# RAMBo.net
KiCad netlist of a schematic drawn in Altium Designer
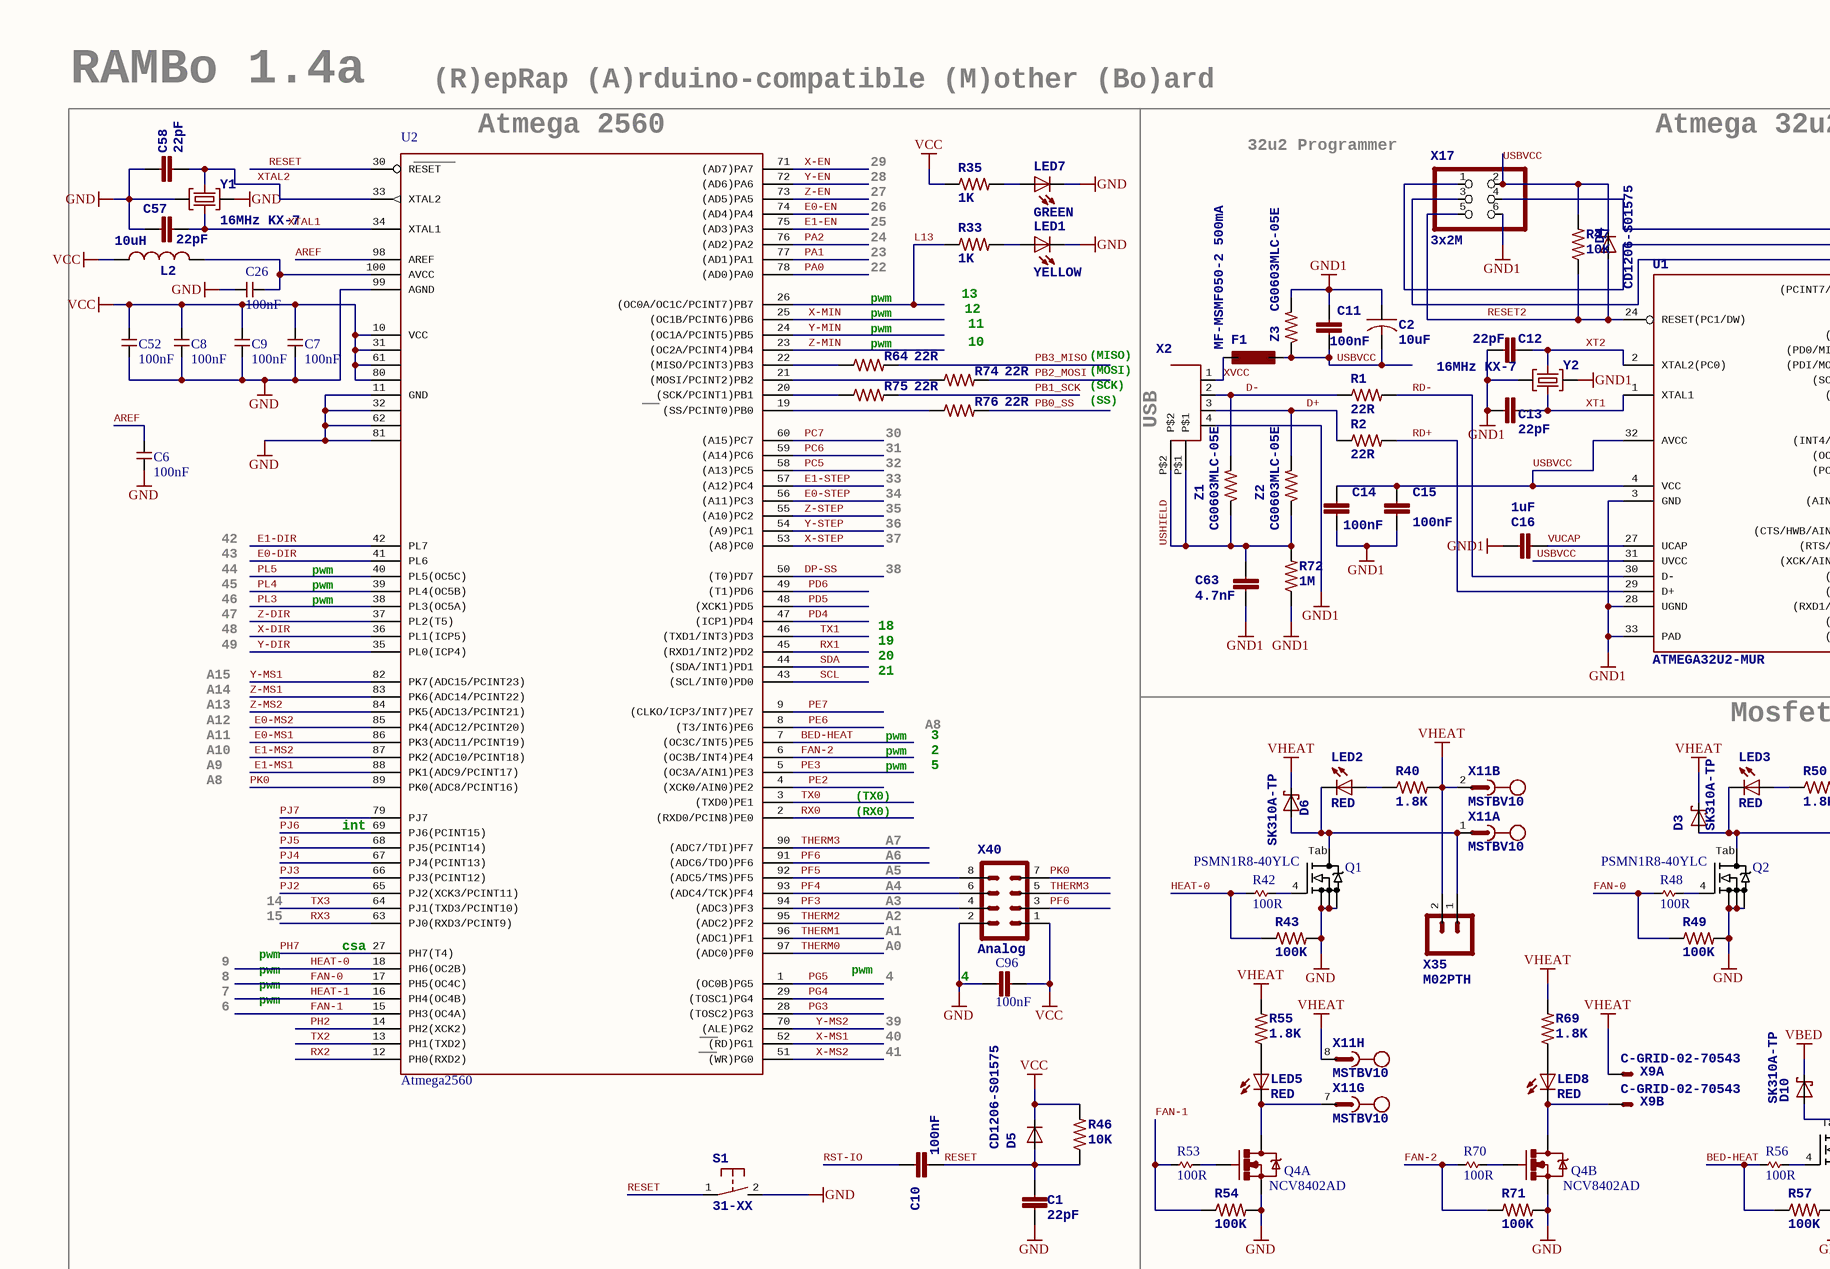
[diagram p0: RAMBo.SchDoc, top left]
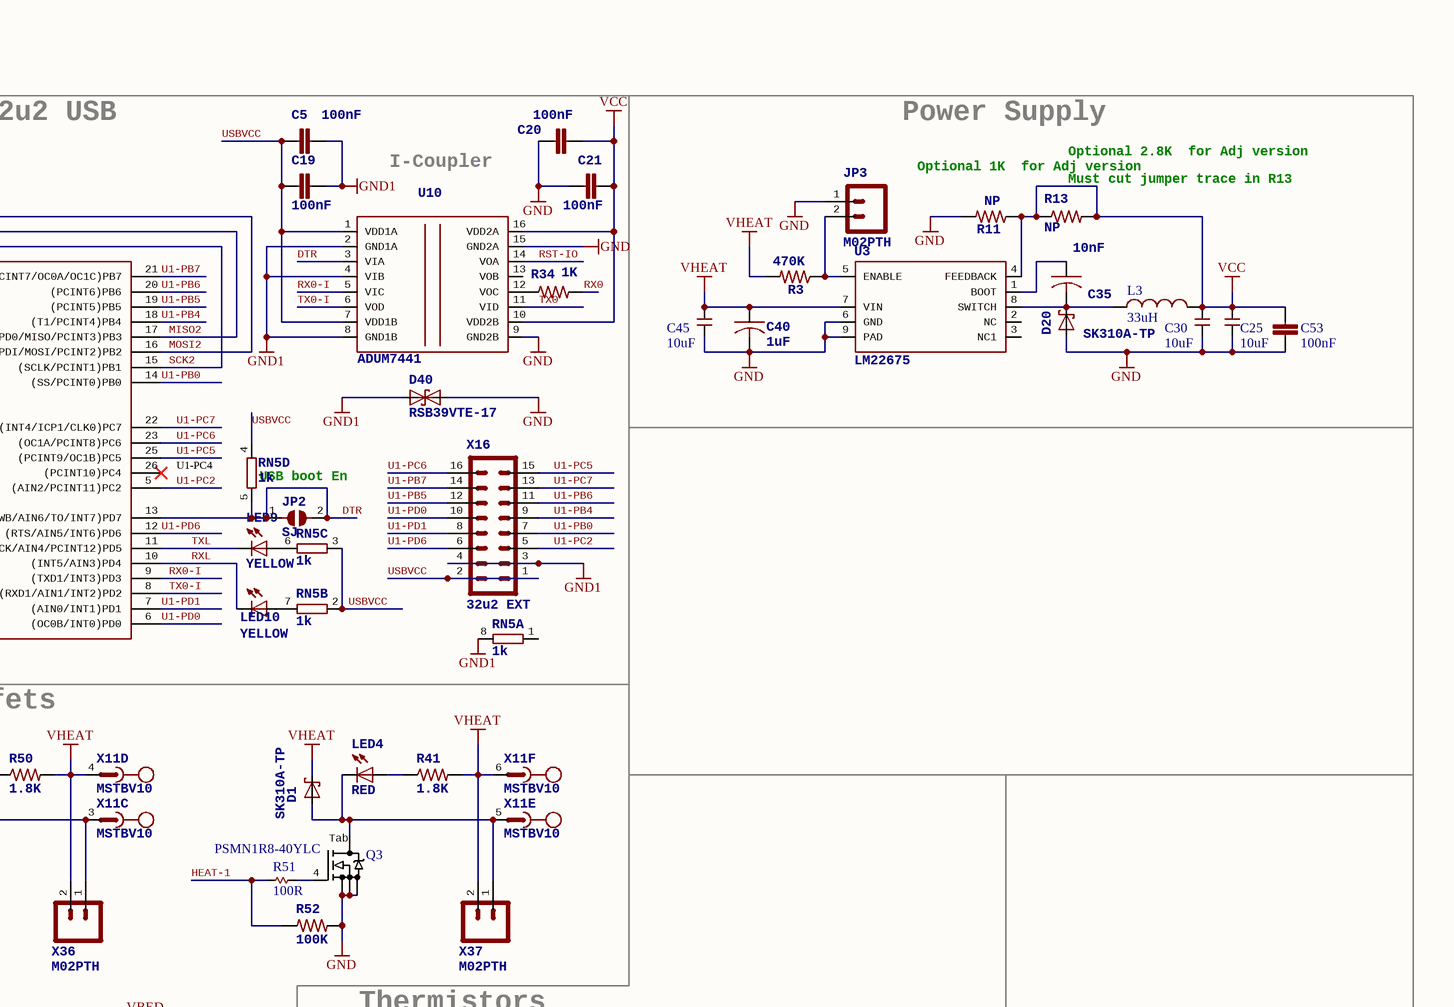
[diagram p1: RAMBo.SchDoc, top right]
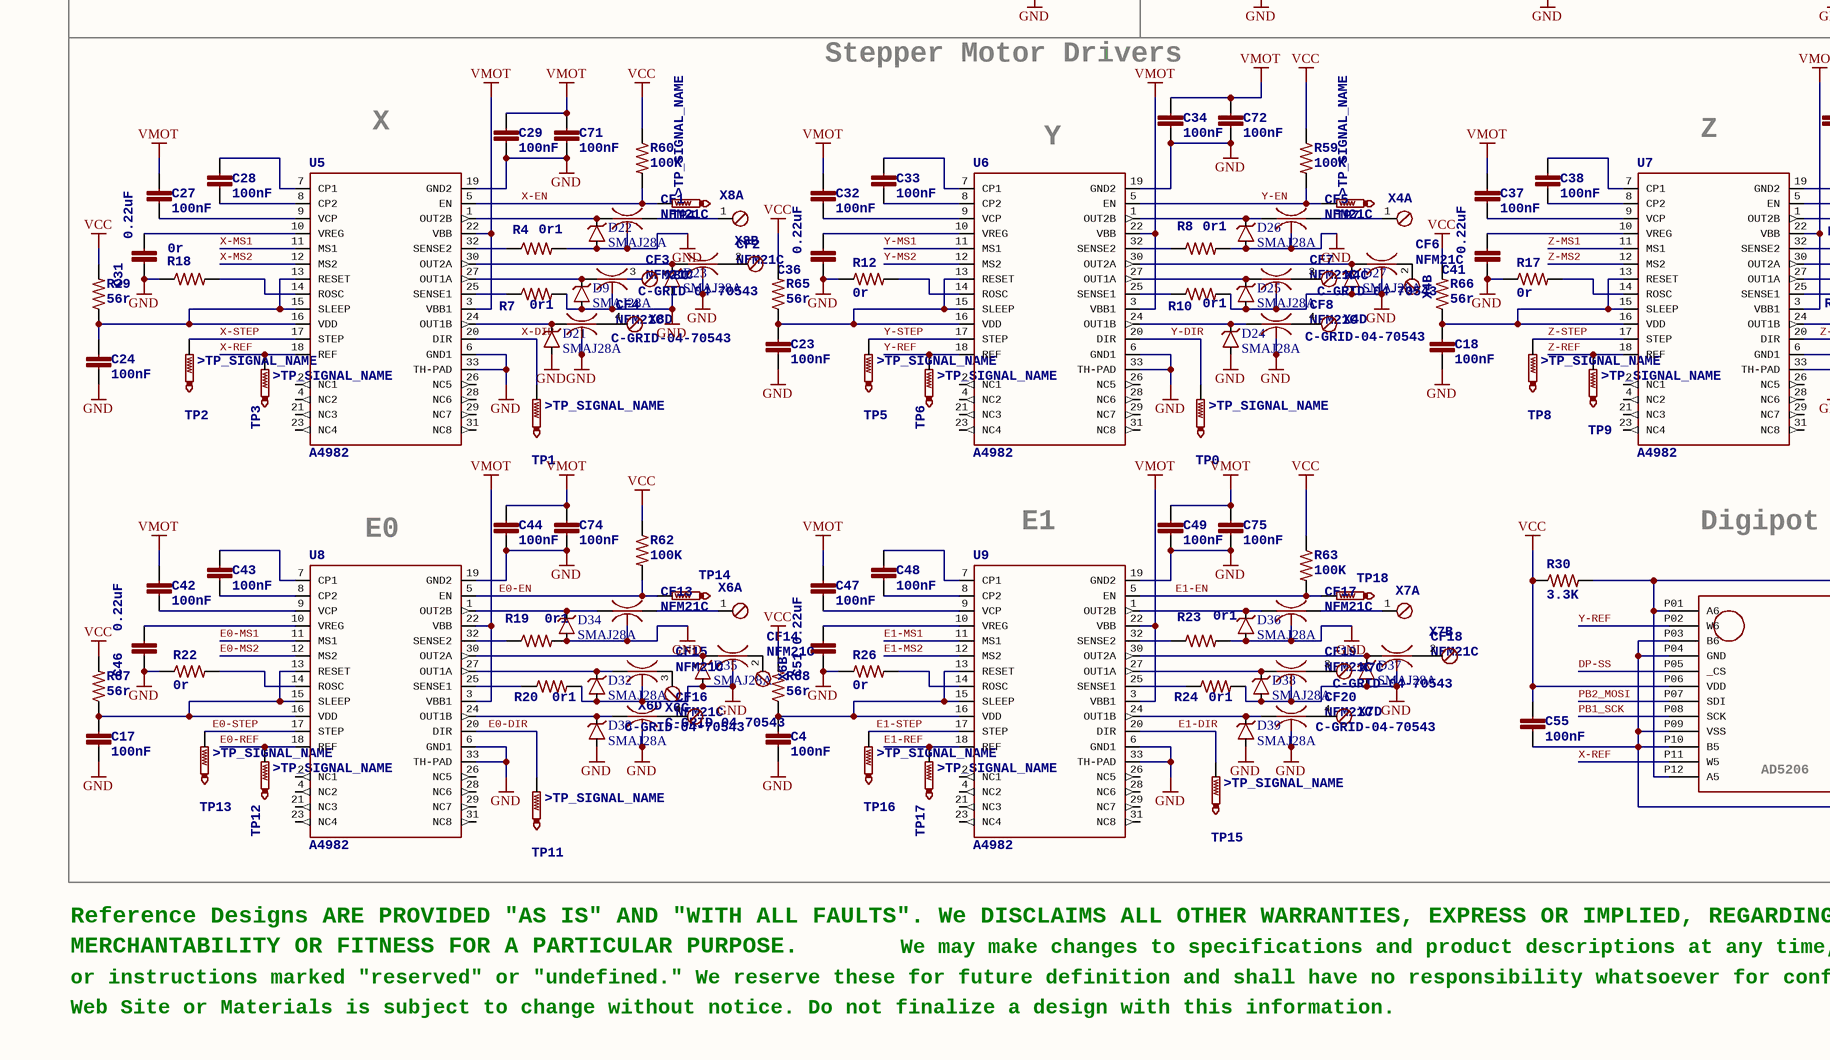
[diagram p2: RAMBo.SchDoc, bottom left]
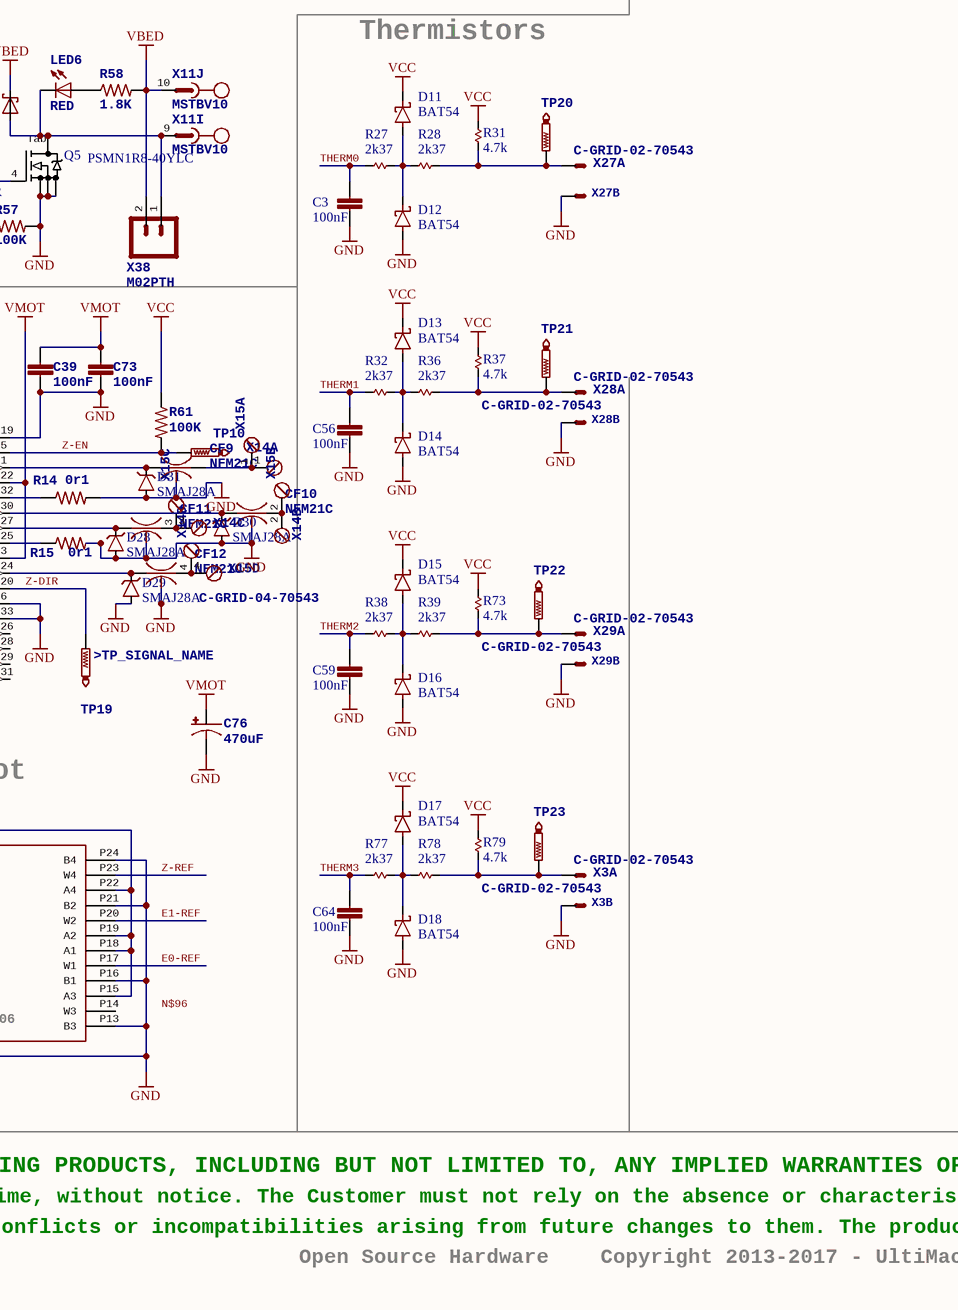
[diagram p3: RAMBo.SchDoc, bottom right]

(export (version "E")
  (design (tool "Eeschema 10.0.6"))
  (components
    (comp (ref "C1")
      (value "22pF")
      (footprint "C0603")
      (description "CAPACITOR, European symbol")
      (fields (field (name "MANUFACTURER") "TDK"))
      (libsource (lib "") (part "C-EUC0603_2"))
    )
    (comp (ref "C2")
      (value "10uF")
      (footprint "C0805")
      (description "CAPACITOR, American symbol")
      (fields (field (name "MANUFACTURER") "Kemet"))
      (libsource (lib "rcl") (part "C-USC0805"))
    )
    (comp (ref "C3")
      (value "100nF")
      (footprint "C0402")
      (description "CAP CER 0402 100nF 16V 10% X7R")
      (fields (field (name "MANUFACTURER") "Murata") (field (name "TOLERANCE") "+/- 10%"))
      (libsource (lib "") (part "GRM155R71C104KA88D_1"))
    )
    (comp (ref "C4")
      (value "100nF")
      (footprint "C0603")
      (description "CAPACITOR, European symbol")
      (fields (field (name "MANUFACTURER") "Kemet"))
      (libsource (lib "resistor") (part "C-EUC0603"))
    )
    (comp (ref "C5")
      (value "100nF")
      (footprint "C0402")
      (description "CAPACITOR, European symbol")
      (fields (field (name "MANUFACTURER") "Murata"))
      (libsource (lib "") (part "C-EUC0402_1"))
    )
    (comp (ref "C6")
      (value "100nF")
      (footprint "C0402")
      (description "CAP CER 0402 100nF 16V 10% X7R")
      (fields (field (name "MANUFACTURER") "Murata") (field (name "PART") "0.1uF 16V X7R 0402"))
      (libsource (lib "Capacitors") (part "100nF 0402 16V X7R"))
    )
    (comp (ref "C7")
      (value "100nF")
      (footprint "C0402")
      (description "CAP CER 0402 100nF 16V 10% X7R")
      (fields (field (name "MANUFACTURER") "Murata") (field (name "PART") "0.1uF 16V X7R 0402"))
      (libsource (lib "Capacitors") (part "100nF 0402 16V X7R"))
    )
    (comp (ref "C8")
      (value "100nF")
      (footprint "C0402")
      (description "CAP CER 0402 100nF 16V 10% X7R")
      (fields (field (name "MANUFACTURER") "Murata") (field (name "PART") "0.1uF 16V X7R 0402"))
      (libsource (lib "Capacitors") (part "100nF 0402 16V X7R"))
    )
    (comp (ref "C9")
      (value "100nF")
      (footprint "C0402")
      (description "CAP CER 0402 100nF 16V 10% X7R")
      (fields (field (name "MANUFACTURER") "Murata") (field (name "PART") "0.1uF 16V X7R 0402"))
      (libsource (lib "Capacitors") (part "100nF 0402 16V X7R"))
    )
    (comp (ref "C10")
      (value "100nF")
      (footprint "C0603")
      (description "CAPACITOR, European symbol")
      (fields (field (name "MANUFACTURER") "Kemet"))
      (libsource (lib "") (part "C-EUC0603_1"))
    )
    (comp (ref "C11")
      (value "100nF")
      (footprint "C0603")
      (description "CAPACITOR, European symbol")
      (fields (field (name "MANUFACTURER") "Kemet"))
      (libsource (lib "") (part "C-EUC0603_1"))
    )
    (comp (ref "C12")
      (value "22pF")
      (footprint "C0603")
      (description "CAPACITOR, European symbol")
      (fields (field (name "MANUFACTURER") "TDK"))
      (libsource (lib "resistor") (part "C-EUC0603"))
    )
    (comp (ref "C13")
      (value "22pF")
      (footprint "C0603")
      (description "CAPACITOR, European symbol")
      (fields (field (name "MANUFACTURER") "TDK"))
      (libsource (lib "resistor") (part "C-EUC0603"))
    )
    (comp (ref "C14")
      (value "100nF")
      (footprint "C0603")
      (description "CAPACITOR, European symbol")
      (fields (field (name "MANUFACTURER") "Kemet"))
      (libsource (lib "resistor") (part "C-EUC0603"))
    )
    (comp (ref "C15")
      (value "100nF")
      (footprint "C0603")
      (description "CAPACITOR, European symbol")
      (fields (field (name "MANUFACTURER") "Kemet"))
      (libsource (lib "resistor") (part "C-EUC0603"))
    )
    (comp (ref "C16")
      (value "1uF")
      (footprint "C0603")
      (description "CAPACITOR, European symbol")
      (fields (field (name "MANUFACTURER") "yageo"))
      (libsource (lib "resistor") (part "C-EUC0603"))
    )
    (comp (ref "C17")
      (value "100nF")
      (footprint "C0603")
      (description "CAPACITOR, European symbol")
      (fields (field (name "MANUFACTURER") "Kemet"))
      (libsource (lib "resistor") (part "C-EUC0603"))
    )
    (comp (ref "C18")
      (value "100nF")
      (footprint "C0603")
      (description "CAPACITOR, European symbol")
      (fields (field (name "MANUFACTURER") "Kemet"))
      (libsource (lib "resistor") (part "C-EUC0603"))
    )
    (comp (ref "C19")
      (value "100nF")
      (footprint "C0402")
      (description "CAPACITOR, European symbol")
      (fields (field (name "MANUFACTURER") "Murata"))
      (libsource (lib "") (part "C-EUC0402_1"))
    )
    (comp (ref "C20")
      (value "100nF")
      (footprint "C0402")
      (description "CAPACITOR, European symbol")
      (fields (field (name "MANUFACTURER") "Murata"))
      (libsource (lib "") (part "C-EUC0402_2"))
    )
    (comp (ref "C21")
      (value "100nF")
      (footprint "C0402")
      (description "CAPACITOR, European symbol")
      (fields (field (name "MANUFACTURER") "Murata"))
      (libsource (lib "") (part "C-EUC0402_1"))
    )
    (comp (ref "C23")
      (value "100nF")
      (footprint "C0603")
      (description "CAPACITOR, European symbol")
      (fields (field (name "MANUFACTURER") "Kemet"))
      (libsource (lib "resistor") (part "C-EUC0603"))
    )
    (comp (ref "C24")
      (value "100nF")
      (footprint "C0603")
      (description "CAPACITOR, European symbol")
      (fields (field (name "MANUFACTURER") "Kemet"))
      (libsource (lib "resistor") (part "C-EUC0603"))
    )
    (comp (ref "C25")
      (value "10uF")
      (footprint "C1206")
      (description "CAP CER 10UF 35V 10% X5R 1206")
      (fields (field (name "MANUFACTURER") "Murata") (field (name "PART") "10uF 35V X5R 1206"))
      (libsource (lib "Capacitors") (part "10uF 1206 35V X5R"))
    )
    (comp (ref "C26")
      (value "100nF")
      (footprint "C0402")
      (description "CAP CER 0402 100nF 16V 10% X7R")
      (fields (field (name "MANUFACTURER") "Murata") (field (name "PART") "0.1uF 16V X7R 0402"))
      (libsource (lib "Capacitors") (part "100nF 0402 16V X7R"))
    )
    (comp (ref "C27")
      (value "100nF")
      (footprint "C0603")
      (description "CAPACITOR, European symbol")
      (fields (field (name "MANUFACTURER") "Kemet"))
      (libsource (lib "resistor") (part "C-EUC0603"))
    )
    (comp (ref "C28")
      (value "100nF")
      (footprint "C0603")
      (description "CAPACITOR, European symbol")
      (fields (field (name "MANUFACTURER") "Kemet"))
      (libsource (lib "resistor") (part "C-EUC0603"))
    )
    (comp (ref "C29")
      (value "100nF")
      (footprint "C0603")
      (description "CAPACITOR, European symbol")
      (fields (field (name "MANUFACTURER") "Kemet"))
      (libsource (lib "resistor") (part "C-EUC0603"))
    )
    (comp (ref "C30")
      (value "10uF")
      (footprint "C1206")
      (description "CAP CER 10UF 35V 10% X5R 1206")
      (fields (field (name "MANUFACTURER") "Murata") (field (name "PART") "10uF 35V X5R 1206"))
      (libsource (lib "Capacitors") (part "10uF 1206 35V X5R"))
    )
    (comp (ref "C31")
      (value "0.22uF")
      (footprint "C0603")
      (description "CAPACITOR, European symbol")
      (fields (field (name "MANUFACTURER") "Yageo"))
      (libsource (lib "") (part "C-EUC0603_1"))
    )
    (comp (ref "C32")
      (value "100nF")
      (footprint "C0603")
      (description "CAPACITOR, European symbol")
      (fields (field (name "MANUFACTURER") "Kemet"))
      (libsource (lib "resistor") (part "C-EUC0603"))
    )
    (comp (ref "C33")
      (value "100nF")
      (footprint "C0603")
      (description "CAPACITOR, European symbol")
      (fields (field (name "MANUFACTURER") "Kemet"))
      (libsource (lib "resistor") (part "C-EUC0603"))
    )
    (comp (ref "C34")
      (value "100nF")
      (footprint "C0603")
      (description "CAPACITOR, European symbol")
      (fields (field (name "MANUFACTURER") "Kemet"))
      (libsource (lib "resistor") (part "C-EUC0603"))
    )
    (comp (ref "C35")
      (value "10nF")
      (footprint "C0603")
      (description "CAPACITOR, American symbol")
      (fields (field (name "MANUFACTURER") "TDK"))
      (libsource (lib "rcl") (part "C-USC0603"))
    )
    (comp (ref "C36")
      (value "0.22uF")
      (footprint "C0603")
      (description "CAPACITOR, European symbol")
      (fields (field (name "MANUFACTURER") "Yageo"))
      (libsource (lib "") (part "C-EUC0603_1"))
    )
    (comp (ref "C37")
      (value "100nF")
      (footprint "C0603")
      (description "CAPACITOR, European symbol")
      (fields (field (name "MANUFACTURER") "Kemet"))
      (libsource (lib "resistor") (part "C-EUC0603"))
    )
    (comp (ref "C38")
      (value "100nF")
      (footprint "C0603")
      (description "CAPACITOR, European symbol")
      (fields (field (name "MANUFACTURER") "Kemet"))
      (libsource (lib "resistor") (part "C-EUC0603"))
    )
    (comp (ref "C39")
      (value "100nF")
      (footprint "C0603")
      (description "CAPACITOR, European symbol")
      (fields (field (name "MANUFACTURER") "Kemet"))
      (libsource (lib "resistor") (part "C-EUC0603"))
    )
    (comp (ref "C40")
      (value "1uF")
      (footprint "C0805")
      (description "CAPACITOR, American symbol")
      (fields (field (name "MANUFACTURER") "Murata"))
      (libsource (lib "rcl") (part "C-USC0805"))
    )
    (comp (ref "C41")
      (value "0.22uF")
      (footprint "C0603")
      (description "CAPACITOR, European symbol")
      (fields (field (name "MANUFACTURER") "Yageo"))
      (libsource (lib "") (part "C-EUC0603_1"))
    )
    (comp (ref "C42")
      (value "100nF")
      (footprint "C0603")
      (description "CAPACITOR, European symbol")
      (fields (field (name "MANUFACTURER") "Kemet"))
      (libsource (lib "resistor") (part "C-EUC0603"))
    )
    (comp (ref "C43")
      (value "100nF")
      (footprint "C0603")
      (description "CAPACITOR, European symbol")
      (fields (field (name "MANUFACTURER") "Kemet"))
      (libsource (lib "resistor") (part "C-EUC0603"))
    )
    (comp (ref "C44")
      (value "100nF")
      (footprint "C0603")
      (description "CAPACITOR, European symbol")
      (fields (field (name "MANUFACTURER") "Kemet"))
      (libsource (lib "resistor") (part "C-EUC0603"))
    )
    (comp (ref "C45")
      (value "10uF")
      (footprint "C1206")
      (description "CAP CER 10UF 35V 10% X5R 1206")
      (fields (field (name "MANUFACTURER") "Murata") (field (name "PART") "10uF 35V X5R 1206"))
      (libsource (lib "Capacitors") (part "10uF 1206 35V X5R"))
    )
    (comp (ref "C46")
      (value "0.22uF")
      (footprint "C0603")
      (description "CAPACITOR, European symbol")
      (fields (field (name "MANUFACTURER") "Yageo"))
      (libsource (lib "") (part "C-EUC0603_1"))
    )
    (comp (ref "C47")
      (value "100nF")
      (footprint "C0603")
      (description "CAPACITOR, European symbol")
      (fields (field (name "MANUFACTURER") "Kemet"))
      (libsource (lib "resistor") (part "C-EUC0603"))
    )
    (comp (ref "C48")
      (value "100nF")
      (footprint "C0603")
      (description "CAPACITOR, European symbol")
      (fields (field (name "MANUFACTURER") "Kemet"))
      (libsource (lib "resistor") (part "C-EUC0603"))
    )
    (comp (ref "C49")
      (value "100nF")
      (footprint "C0603")
      (description "CAPACITOR, European symbol")
      (fields (field (name "MANUFACTURER") "Kemet"))
      (libsource (lib "resistor") (part "C-EUC0603"))
    )
    (comp (ref "C51")
      (value "0.22uF")
      (footprint "C0603")
      (description "CAPACITOR, European symbol")
      (fields (field (name "MANUFACTURER") "Yageo"))
      (libsource (lib "") (part "C-EUC0603_1"))
    )
    (comp (ref "C52")
      (value "100nF")
      (footprint "C0402")
      (description "CAP CER 0402 100nF 16V 10% X7R")
      (fields (field (name "MANUFACTURER") "Murata") (field (name "PART") "0.1uF 16V X7R 0402"))
      (libsource (lib "Capacitors") (part "100nF 0402 16V X7R"))
    )
    (comp (ref "C53")
      (value "100nF")
      (footprint "C0402")
      (description "CAP CER 0402 100nF 16V 10% X7R")
      (fields (field (name "MANUFACTURER") "Murata") (field (name "TOLERANCE") "+/- 10%"))
      (libsource (lib "") (part "GRM155R71C104KA88D_1"))
    )
    (comp (ref "C55")
      (value "100nF")
      (footprint "C0603")
      (description "CAPACITOR, European symbol")
      (fields (field (name "MANUFACTURER") "Kemet"))
      (libsource (lib "resistor") (part "C-EUC0603"))
    )
    (comp (ref "C56")
      (value "100nF")
      (footprint "C0402")
      (description "CAP CER 0402 100nF 16V 10% X7R")
      (fields (field (name "MANUFACTURER") "Murata") (field (name "TOLERANCE") "+/- 10%"))
      (libsource (lib "") (part "GRM155R71C104KA88D_1"))
    )
    (comp (ref "C57")
      (value "22pF")
      (footprint "C0603")
      (description "CAPACITOR, European symbol")
      (fields (field (name "MANUFACTURER") "TDK"))
      (libsource (lib "resistor") (part "C-EUC0603"))
    )
    (comp (ref "C58")
      (value "22pF")
      (footprint "C0603")
      (description "CAPACITOR, European symbol")
      (fields (field (name "MANUFACTURER") "TDK"))
      (libsource (lib "resistor") (part "C-EUC0603"))
    )
    (comp (ref "C59")
      (value "100nF")
      (footprint "C0402")
      (description "CAP CER 0402 100nF 16V 10% X7R")
      (fields (field (name "MANUFACTURER") "Murata") (field (name "TOLERANCE") "+/- 10%"))
      (libsource (lib "") (part "GRM155R71C104KA88D_1"))
    )
    (comp (ref "C63")
      (value "4.7nF")
      (footprint "C0402")
      (description "CAPACITOR, European symbol")
      (libsource (lib "rcl") (part "C-EUC0402"))
    )
    (comp (ref "C64")
      (value "100nF")
      (footprint "C0402")
      (description "CAP CER 0402 100nF 16V 10% X7R")
      (fields (field (name "MANUFACTURER") "Murata") (field (name "TOLERANCE") "+/- 10%"))
      (libsource (lib "") (part "GRM155R71C104KA88D_1"))
    )
    (comp (ref "C71")
      (value "100nF")
      (footprint "C0603")
      (description "CAPACITOR, European symbol")
      (fields (field (name "MANUFACTURER") "Kemet"))
      (libsource (lib "resistor") (part "C-EUC0603"))
    )
    (comp (ref "C72")
      (value "100nF")
      (footprint "C0603")
      (description "CAPACITOR, European symbol")
      (fields (field (name "MANUFACTURER") "Kemet"))
      (libsource (lib "resistor") (part "C-EUC0603"))
    )
    (comp (ref "C73")
      (value "100nF")
      (footprint "C0603")
      (description "CAPACITOR, European symbol")
      (fields (field (name "MANUFACTURER") "Kemet"))
      (libsource (lib "resistor") (part "C-EUC0603"))
    )
    (comp (ref "C74")
      (value "100nF")
      (footprint "C0603")
      (description "CAPACITOR, European symbol")
      (fields (field (name "MANUFACTURER") "Kemet"))
      (libsource (lib "resistor") (part "C-EUC0603"))
    )
    (comp (ref "C75")
      (value "100nF")
      (footprint "C0603")
      (description "CAPACITOR, European symbol")
      (fields (field (name "MANUFACTURER") "Kemet"))
      (libsource (lib "resistor") (part "C-EUC0603"))
    )
    (comp (ref "C76")
      (value "470uF")
      (footprint "C12,5-5")
      (description "POLARIZED CAPACITOR, American symbol")
      (fields (field (name "MANUFACTURER") "nichicon"))
      (libsource (lib "resistor") (part "CPOL-USC12,5-5"))
    )
    (comp (ref "C96")
      (value "100nF")
      (footprint "C0402")
      (description "CAP CER 0402 100nF 16V 10% X7R")
      (fields (field (name "MANUFACTURER") "Murata") (field (name "TOLERANCE") "+/- 10%"))
      (libsource (lib "3Delight") (part "GRM155R71C104KA88D"))
    )
    (comp (ref "CF1")
      (value "NFM21C")
      (footprint "NFM21C")
      (fields (field (name "MPN") "NFM21CC102R1H3D"))
      (libsource (lib "murata-filter") (part "NFM21C"))
    )
    (comp (ref "CF2")
      (value "NFM21C")
      (footprint "NFM21C")
      (fields (field (name "MPN") "NFM21CC102R1H3D"))
      (libsource (lib "murata-filter") (part "NFM21C"))
    )
    (comp (ref "CF3")
      (value "NFM21C")
      (footprint "NFM21C")
      (fields (field (name "MPN") "NFM21CC102R1H3D"))
      (libsource (lib "murata-filter") (part "NFM21C"))
    )
    (comp (ref "CF4")
      (value "NFM21C")
      (footprint "NFM21C")
      (fields (field (name "MPN") "NFM21CC102R1H3D"))
      (libsource (lib "murata-filter") (part "NFM21C"))
    )
    (comp (ref "CF5")
      (value "NFM21C")
      (footprint "NFM21C")
      (fields (field (name "MPN") "NFM21CC102R1H3D"))
      (libsource (lib "murata-filter") (part "NFM21C"))
    )
    (comp (ref "CF6")
      (value "NFM21C")
      (footprint "NFM21C")
      (fields (field (name "MPN") "NFM21CC102R1H3D"))
      (libsource (lib "murata-filter") (part "NFM21C"))
    )
    (comp (ref "CF7")
      (value "NFM21C")
      (footprint "NFM21C")
      (fields (field (name "MPN") "NFM21CC102R1H3D"))
      (libsource (lib "murata-filter") (part "NFM21C"))
    )
    (comp (ref "CF8")
      (value "NFM21C")
      (footprint "NFM21C")
      (fields (field (name "MPN") "NFM21CC102R1H3D"))
      (libsource (lib "murata-filter") (part "NFM21C"))
    )
    (comp (ref "CF9")
      (value "NFM21C")
      (footprint "NFM21C")
      (fields (field (name "MPN") "NFM21CC102R1H3D"))
      (libsource (lib "murata-filter") (part "NFM21C"))
    )
    (comp (ref "CF10")
      (value "NFM21C")
      (footprint "NFM21C")
      (fields (field (name "MPN") "NFM21CC102R1H3D"))
      (libsource (lib "murata-filter") (part "NFM21C"))
    )
    (comp (ref "CF11")
      (value "NFM21C")
      (footprint "NFM21C")
      (fields (field (name "MPN") "NFM21CC102R1H3D"))
      (libsource (lib "murata-filter") (part "NFM21C"))
    )
    (comp (ref "CF12")
      (value "NFM21C")
      (footprint "NFM21C")
      (fields (field (name "MPN") "NFM21CC102R1H3D"))
      (libsource (lib "murata-filter") (part "NFM21C"))
    )
    (comp (ref "CF13")
      (value "NFM21C")
      (footprint "NFM21C")
      (fields (field (name "MPN") "NFM21CC102R1H3D"))
      (libsource (lib "murata-filter") (part "NFM21C"))
    )
    (comp (ref "CF14")
      (value "NFM21C")
      (footprint "NFM21C")
      (fields (field (name "MPN") "NFM21CC102R1H3D"))
      (libsource (lib "murata-filter") (part "NFM21C"))
    )
    (comp (ref "CF15")
      (value "NFM21C")
      (footprint "NFM21C")
      (fields (field (name "MPN") "NFM21CC102R1H3D"))
      (libsource (lib "murata-filter") (part "NFM21C"))
    )
    (comp (ref "CF16")
      (value "NFM21C")
      (footprint "NFM21C")
      (fields (field (name "MPN") "NFM21CC102R1H3D"))
      (libsource (lib "murata-filter") (part "NFM21C"))
    )
    (comp (ref "CF17")
      (value "NFM21C")
      (footprint "NFM21C")
      (fields (field (name "MPN") "NFM21CC102R1H3D"))
      (libsource (lib "murata-filter") (part "NFM21C"))
    )
    (comp (ref "CF18")
      (value "NFM21C")
      (footprint "NFM21C")
      (fields (field (name "MPN") "NFM21CC102R1H3D"))
      (libsource (lib "murata-filter") (part "NFM21C"))
    )
    (comp (ref "CF19")
      (value "NFM21C")
      (footprint "NFM21C")
      (fields (field (name "MPN") "NFM21CC102R1H3D"))
      (libsource (lib "murata-filter") (part "NFM21C"))
    )
    (comp (ref "CF20")
      (value "NFM21C")
      (footprint "NFM21C")
      (fields (field (name "MPN") "NFM21CC102R1H3D"))
      (libsource (lib "murata-filter") (part "NFM21C"))
    )
    (comp (ref "D1")
      (value "SK310A-TP")
      (footprint "SMA-SM")
      (description "Schottky Diode")
      (fields (field (name "MANUFACTURER") "Diodes Inc."))
      (libsource (lib "ultimachine1") (part "SCHOTTKY-DIODE"))
    )
    (comp (ref "D3")
      (value "SK310A-TP")
      (footprint "SMA-SM")
      (description "Schottky Diode")
      (fields (field (name "MANUFACTURER") "Diodes Inc."))
      (libsource (lib "ultimachine1") (part "SCHOTTKY-DIODE"))
    )
    (comp (ref "D4")
      (value "CD1206-S01575")
      (footprint "MINIMELF")
      (description "DIODE")
      (fields (field (name "MANUFACTURER") "Bourns"))
      (libsource (lib "diode") (part "DIODE-MINIMELF"))
    )
    (comp (ref "D5")
      (value "CD1206-S01575")
      (footprint "MINIMELF")
      (description "DIODE")
      (fields (field (name "MANUFACTURER") "Bourns"))
      (libsource (lib "diode") (part "DIODE-MINIMELF"))
    )
    (comp (ref "D6")
      (value "SK310A-TP")
      (footprint "SMA-SM")
      (description "Schottky Diode")
      (fields (field (name "MANUFACTURER") "Diodes Inc."))
      (libsource (lib "ultimachine1") (part "SCHOTTKY-DIODE"))
    )
    (comp (ref "D9")
      (value "SMAJ28A")
      (footprint "Passives:SMA-SM")
      (description "TVS DIODE 28VWM 45.4VC SMA")
      (fields (field (name "MANUFACTURER") "Diodes Inc") (field (name "TOLERANCE") "NA"))
      (libsource (lib "Diodes") (part "SMAJ28A"))
    )
    (comp (ref "D10")
      (value "SK310A-TP")
      (footprint "SMA-SM")
      (description "Schottky Diode")
      (fields (field (name "MANUFACTURER") "Diodes Inc."))
      (libsource (lib "ultimachine1") (part "SCHOTTKY-DIODE"))
    )
    (comp (ref "D11")
      (value "BAT54")
      (footprint "SOD523_IPC")
      (description "Diode Schottky 30V 100mA Surface Mount SOD-523")
      (fields (field (name "MANUFACTURER") "Diodes Incorporated") (field (name "TOLERANCE") "NA"))
      (libsource (lib "3Delight") (part "BAT54WT-7"))
    )
    (comp (ref "D12")
      (value "BAT54")
      (footprint "SOD523_IPC")
      (description "Diode Schottky 30V 100mA Surface Mount SOD-523")
      (fields (field (name "MANUFACTURER") "Diodes Incorporated") (field (name "TOLERANCE") "NA"))
      (libsource (lib "3Delight") (part "BAT54WT-7"))
    )
    (comp (ref "D13")
      (value "BAT54")
      (footprint "SOD523_IPC")
      (description "Diode Schottky 30V 100mA Surface Mount SOD-523")
      (fields (field (name "MANUFACTURER") "Diodes Incorporated") (field (name "TOLERANCE") "NA"))
      (libsource (lib "3Delight") (part "BAT54WT-7"))
    )
    (comp (ref "D14")
      (value "BAT54")
      (footprint "SOD523_IPC")
      (description "Diode Schottky 30V 100mA Surface Mount SOD-523")
      (fields (field (name "MANUFACTURER") "Diodes Incorporated") (field (name "TOLERANCE") "NA"))
      (libsource (lib "3Delight") (part "BAT54WT-7"))
    )
    (comp (ref "D15")
      (value "BAT54")
      (footprint "SOD523_IPC")
      (description "Diode Schottky 30V 100mA Surface Mount SOD-523")
      (fields (field (name "MANUFACTURER") "Diodes Incorporated") (field (name "TOLERANCE") "NA"))
      (libsource (lib "3Delight") (part "BAT54WT-7"))
    )
    (comp (ref "D16")
      (value "BAT54")
      (footprint "SOD523_IPC")
      (description "Diode Schottky 30V 100mA Surface Mount SOD-523")
      (fields (field (name "MANUFACTURER") "Diodes Incorporated") (field (name "TOLERANCE") "NA"))
      (libsource (lib "3Delight") (part "BAT54WT-7"))
    )
    (comp (ref "D17")
      (value "BAT54")
      (footprint "SOD523_IPC")
      (description "Diode Schottky 30V 100mA Surface Mount SOD-523")
      (fields (field (name "MANUFACTURER") "Diodes Incorporated") (field (name "TOLERANCE") "NA"))
      (libsource (lib "3Delight") (part "BAT54WT-7"))
    )
    (comp (ref "D18")
      (value "BAT54")
      (footprint "SOD523_IPC")
      (description "Diode Schottky 30V 100mA Surface Mount SOD-523")
      (fields (field (name "MANUFACTURER") "Diodes Incorporated") (field (name "TOLERANCE") "NA"))
      (libsource (lib "3Delight") (part "BAT54WT-7"))
    )
    (comp (ref "D20")
      (value "SK310A-TP")
      (footprint "SMA-SM")
      (description "Schottky Diode")
      (fields (field (name "MANUFACTURER") "Diodes Inc."))
      (libsource (lib "ultimachine1") (part "SCHOTTKY-DIODE"))
    )
    (comp (ref "D21")
      (value "SMAJ28A")
      (footprint "Passives:SMA-SM")
      (description "TVS DIODE 28VWM 45.4VC SMA")
      (fields (field (name "MANUFACTURER") "Diodes Inc") (field (name "TOLERANCE") "NA"))
      (libsource (lib "Diodes") (part "SMAJ28A"))
    )
    (comp (ref "D22")
      (value "SMAJ28A")
      (footprint "Passives:SMA-SM")
      (description "TVS DIODE 28VWM 45.4VC SMA")
      (fields (field (name "MANUFACTURER") "Diodes Inc") (field (name "TOLERANCE") "NA"))
      (libsource (lib "Diodes") (part "SMAJ28A"))
    )
    (comp (ref "D23")
      (value "SMAJ28A")
      (footprint "Passives:SMA-SM")
      (description "TVS DIODE 28VWM 45.4VC SMA")
      (fields (field (name "MANUFACTURER") "Diodes Inc") (field (name "TOLERANCE") "NA"))
      (libsource (lib "Diodes") (part "SMAJ28A"))
    )
    (comp (ref "D24")
      (value "SMAJ28A")
      (footprint "Passives:SMA-SM")
      (description "TVS DIODE 28VWM 45.4VC SMA")
      (fields (field (name "MANUFACTURER") "Diodes Inc") (field (name "TOLERANCE") "NA"))
      (libsource (lib "Diodes") (part "SMAJ28A"))
    )
    (comp (ref "D25")
      (value "SMAJ28A")
      (footprint "Passives:SMA-SM")
      (description "TVS DIODE 28VWM 45.4VC SMA")
      (fields (field (name "MANUFACTURER") "Diodes Inc") (field (name "TOLERANCE") "NA"))
      (libsource (lib "Diodes") (part "SMAJ28A"))
    )
    (comp (ref "D26")
      (value "SMAJ28A")
      (footprint "Passives:SMA-SM")
      (description "TVS DIODE 28VWM 45.4VC SMA")
      (fields (field (name "MANUFACTURER") "Diodes Inc") (field (name "TOLERANCE") "NA"))
      (libsource (lib "Diodes") (part "SMAJ28A"))
    )
    (comp (ref "D27")
      (value "SMAJ28A")
      (footprint "Passives:SMA-SM")
      (description "TVS DIODE 28VWM 45.4VC SMA")
      (fields (field (name "MANUFACTURER") "Diodes Inc") (field (name "TOLERANCE") "NA"))
      (libsource (lib "Diodes") (part "SMAJ28A"))
    )
    (comp (ref "D28")
      (value "SMAJ28A")
      (footprint "Passives:SMA-SM")
      (description "TVS DIODE 28VWM 45.4VC SMA")
      (fields (field (name "MANUFACTURER") "Diodes Inc") (field (name "TOLERANCE") "NA"))
      (libsource (lib "Diodes") (part "SMAJ28A"))
    )
    (comp (ref "D29")
      (value "SMAJ28A")
      (footprint "Passives:SMA-SM")
      (description "TVS DIODE 28VWM 45.4VC SMA")
      (fields (field (name "MANUFACTURER") "Diodes Inc") (field (name "TOLERANCE") "NA"))
      (libsource (lib "Diodes") (part "SMAJ28A"))
    )
    (comp (ref "D30")
      (value "SMAJ28A")
      (footprint "Passives:SMA-SM")
      (description "TVS DIODE 28VWM 45.4VC SMA")
      (fields (field (name "MANUFACTURER") "Diodes Inc") (field (name "TOLERANCE") "NA"))
      (libsource (lib "Diodes") (part "SMAJ28A"))
    )
    (comp (ref "D31")
      (value "SMAJ28A")
      (footprint "Passives:SMA-SM")
      (description "TVS DIODE 28VWM 45.4VC SMA")
      (fields (field (name "MANUFACTURER") "Diodes Inc") (field (name "TOLERANCE") "NA"))
      (libsource (lib "Diodes") (part "SMAJ28A"))
    )
    (comp (ref "D32")
      (value "SMAJ28A")
      (footprint "Passives:SMA-SM")
      (description "TVS DIODE 28VWM 45.4VC SMA")
      (fields (field (name "MANUFACTURER") "Diodes Inc") (field (name "TOLERANCE") "NA"))
      (libsource (lib "Diodes") (part "SMAJ28A"))
    )
    (comp (ref "D33")
      (value "SMAJ28A")
      (footprint "Passives:SMA-SM")
      (description "TVS DIODE 28VWM 45.4VC SMA")
      (fields (field (name "MANUFACTURER") "Diodes Inc") (field (name "TOLERANCE") "NA"))
      (libsource (lib "Diodes") (part "SMAJ28A"))
    )
    (comp (ref "D34")
      (value "SMAJ28A")
      (footprint "Passives:SMA-SM")
      (description "TVS DIODE 28VWM 45.4VC SMA")
      (fields (field (name "MANUFACTURER") "Diodes Inc") (field (name "TOLERANCE") "NA"))
      (libsource (lib "Diodes") (part "SMAJ28A"))
    )
    (comp (ref "D35")
      (value "SMAJ28A")
      (footprint "Passives:SMA-SM")
      (description "TVS DIODE 28VWM 45.4VC SMA")
      (fields (field (name "MANUFACTURER") "Diodes Inc") (field (name "TOLERANCE") "NA"))
      (libsource (lib "Diodes") (part "SMAJ28A"))
    )
    (comp (ref "D36")
      (value "SMAJ28A")
      (footprint "Passives:SMA-SM")
      (description "TVS DIODE 28VWM 45.4VC SMA")
      (fields (field (name "MANUFACTURER") "Diodes Inc") (field (name "TOLERANCE") "NA"))
      (libsource (lib "Diodes") (part "SMAJ28A"))
    )
    (comp (ref "D37")
      (value "SMAJ28A")
      (footprint "Passives:SMA-SM")
      (description "TVS DIODE 28VWM 45.4VC SMA")
      (fields (field (name "MANUFACTURER") "Diodes Inc") (field (name "TOLERANCE") "NA"))
      (libsource (lib "Diodes") (part "SMAJ28A"))
    )
    (comp (ref "D38")
      (value "SMAJ28A")
      (footprint "Passives:SMA-SM")
      (description "TVS DIODE 28VWM 45.4VC SMA")
      (fields (field (name "MANUFACTURER") "Diodes Inc") (field (name "TOLERANCE") "NA"))
      (libsource (lib "Diodes") (part "SMAJ28A"))
    )
    (comp (ref "D39")
      (value "SMAJ28A")
      (footprint "Passives:SMA-SM")
      (description "TVS DIODE 28VWM 45.4VC SMA")
      (fields (field (name "MANUFACTURER") "Diodes Inc") (field (name "TOLERANCE") "NA"))
      (libsource (lib "Diodes") (part "SMAJ28A"))
    )
    (comp (ref "D40")
      (value "RSB39VTE-17")
      (footprint "SOD323-R")
      (description "DIODE   uni and bidirectional supressor diode")
      (libsource (lib "diode") (part "TVS-BISOD323"))
    )
    (comp (ref "F1")
      (value "MF-MSMF050-2 500mA")
      (footprint "L1812")
      (description "INDUCTOR, European symbol")
      (fields (field (name "MANUFACTURER") "Bourns"))
      (libsource (lib "rcl") (part "L-EUL1812"))
    )
    (comp (ref "JP2")
      (value "SJ")
      (footprint "SJ")
      (description "SMD solder JUMPER")
      (libsource (lib "jumper") (part "SJ"))
    )
    (comp (ref "JP3") (value "M02PTH") (footprint "1X02") (libsource (lib "SparkFun") (part "M02PTH")))
    (comp (ref "L2")
      (value "10uH")
      (footprint "C0805")
      (description "INDUCTOR, American symbol")
      (fields (field (name "MANUFACTURER") "Taiyo Yuden"))
      (libsource (lib "resistor") (part "L-US"))
    )
    (comp (ref "L3")
      (value "33uH")
      (footprint "INDP8080X40L")
      (description "FIXED IND 33UH 1.7A 145 MOHM SMD")
      (fields (field (name "MANUFACTURER") "Bourns") (field (name "TOLERANCE") "+/- 20%"))
      (libsource (lib "Inductors") (part "10uH 1.7A"))
    )
    (comp (ref "LED1")
      (value "YELLOW")
      (footprint "CHIP-LED0805")
      (fields (field (name "MANUFACTURER") "Dialight"))
      (libsource (lib "led") (part "LEDCHIP-LED0805"))
    )
    (comp (ref "LED2")
      (value "RED")
      (footprint "CHIP-LED0805")
      (fields (field (name "MANUFACTURER") "Dialight"))
      (libsource (lib "led") (part "LEDCHIP-LED0805"))
    )
    (comp (ref "LED3")
      (value "RED")
      (footprint "CHIP-LED0805")
      (fields (field (name "MANUFACTURER") "Dialight"))
      (libsource (lib "led") (part "LEDCHIP-LED0805"))
    )
    (comp (ref "LED4")
      (value "RED")
      (footprint "CHIP-LED0805")
      (fields (field (name "MANUFACTURER") "Dialight"))
      (libsource (lib "led") (part "LEDCHIP-LED0805"))
    )
    (comp (ref "LED5")
      (value "RED")
      (footprint "CHIP-LED0805")
      (fields (field (name "MANUFACTURER") "Dialight"))
      (libsource (lib "led") (part "LEDCHIP-LED0805"))
    )
    (comp (ref "LED6")
      (value "RED")
      (footprint "CHIP-LED0805")
      (fields (field (name "MANUFACTURER") "Dialight"))
      (libsource (lib "led") (part "LEDCHIP-LED0805"))
    )
    (comp (ref "LED7")
      (value "GREEN")
      (footprint "CHIP-LED0805")
      (libsource (lib "led") (part "LEDCHIP-LED0805"))
    )
    (comp (ref "LED8")
      (value "RED")
      (footprint "CHIP-LED0805")
      (fields (field (name "MANUFACTURER") "Dialight"))
      (libsource (lib "led") (part "LEDCHIP-LED0805"))
    )
    (comp (ref "LED9")
      (value "YELLOW")
      (footprint "CHIP-LED0805")
      (fields (field (name "MANUFACTURER") "Dialight"))
      (libsource (lib "led") (part "LEDCHIP-LED0805"))
    )
    (comp (ref "LED10")
      (value "YELLOW")
      (footprint "CHIP-LED0805")
      (fields (field (name "MANUFACTURER") "Dialight"))
      (libsource (lib "led") (part "LEDCHIP-LED0805"))
    )
    (comp (ref "Q1")
      (value "PSMN1R8-40YLC")
      (footprint "Passives:SOT669")
      (description "MOSFET N-CH 40V 100A LFPAK")
      (fields (field (name "MANUFACTURER") "Nexperia") (field (name "TOLERANCE") "-NA-"))
      (libsource (lib "Transistors") (part "PSMN1R8-40YLC"))
    )
    (comp (ref "Q2")
      (value "PSMN1R8-40YLC")
      (footprint "SOT669")
      (description "MOSFET N-CH 40V 100A LFPAK")
      (fields (field (name "MANUFACTURER") "Nexperia") (field (name "TOLERANCE") "-NA-"))
      (libsource (lib "Transistors") (part "PSMN1R8-40YLC"))
    )
    (comp (ref "Q3")
      (value "PSMN1R8-40YLC")
      (footprint "SOT669")
      (description "MOSFET N-CH 40V 100A LFPAK")
      (fields (field (name "MANUFACTURER") "Nexperia") (field (name "TOLERANCE") "-NA-"))
      (libsource (lib "Transistors") (part "PSMN1R8-40YLC"))
    )
    (comp (ref "Q4")
      (value "NCV8402AD")
      (footprint "NCV8402AD-SOIC8")
      (description "IC DVR LOW SIDE 8-SOIC")
      (fields (field (name "MANUFACTURER") "On Semi") (field (name "PART") "NCV8402"))
      (libsource (lib "3Delight") (part "NCV8402AD"))
    )
    (comp (ref "Q5")
      (value "PSMN1R8-40YLC")
      (footprint "SOT669")
      (description "MOSFET N-CH 40V 100A LFPAK")
      (fields (field (name "MANUFACTURER") "Nexperia") (field (name "TOLERANCE") "-NA-"))
      (libsource (lib "Transistors") (part "PSMN1R8-40YLC"))
    )
    (comp (ref "R1")
      (value "22R")
      (footprint "R0402")
      (description "RESISTOR, American symbol")
      (fields (field (name "MANUFACTURER") "Yageo"))
      (libsource (lib "rcl") (part "R-US_R0402"))
    )
    (comp (ref "R2")
      (value "22R")
      (footprint "R0402")
      (description "RESISTOR, American symbol")
      (fields (field (name "MANUFACTURER") "Yageo"))
      (libsource (lib "rcl") (part "R-US_R0402"))
    )
    (comp (ref "R3")
      (value "470K")
      (footprint "R0603")
      (description "RESISTOR, American symbol")
      (fields (field (name "MANUFACTURER") "Vishay"))
      (libsource (lib "resistor") (part "R-US_R0603"))
    )
    (comp (ref "R4")
      (value "0r1")
      (footprint "R1206")
      (description "RESISTOR, American symbol")
      (fields (field (name "MANUFACTURER") "Bourns"))
      (libsource (lib "resistor") (part "R-US_R1206"))
    )
    (comp (ref "R7")
      (value "0r1")
      (footprint "R1206")
      (description "RESISTOR, American symbol")
      (fields (field (name "MANUFACTURER") "Bourns"))
      (libsource (lib "resistor") (part "R-US_R1206"))
    )
    (comp (ref "R8")
      (value "0r1")
      (footprint "R1206")
      (description "RESISTOR, American symbol")
      (fields (field (name "MANUFACTURER") "Bourns"))
      (libsource (lib "resistor") (part "R-US_R1206"))
    )
    (comp (ref "R10")
      (value "0r1")
      (footprint "R1206")
      (description "RESISTOR, American symbol")
      (fields (field (name "MANUFACTURER") "Bourns"))
      (libsource (lib "resistor") (part "R-US_R1206"))
    )
    (comp (ref "R11")
      (value "NP")
      (footprint "R0603")
      (description "RESISTOR, American symbol")
      (libsource (lib "resistor") (part "R-US_R0603"))
    )
    (comp (ref "R12")
      (value "0r")
      (footprint "R0603")
      (description "RESISTOR, American symbol")
      (fields (field (name "MANUFACTURER") "Bourns"))
      (libsource (lib "resistor") (part "R-US_R0603"))
    )
    (comp (ref "R13")
      (value "NP")
      (footprint "R0603")
      (description "RESISTOR, American symbol")
      (libsource (lib "resistor") (part "R-US_R0603"))
    )
    (comp (ref "R14")
      (value "0r1")
      (footprint "R1206")
      (description "RESISTOR, American symbol")
      (fields (field (name "MANUFACTURER") "Bourns"))
      (libsource (lib "resistor") (part "R-US_R1206"))
    )
    (comp (ref "R15")
      (value "0r1")
      (footprint "R1206")
      (description "RESISTOR, American symbol")
      (fields (field (name "MANUFACTURER") "Bourns"))
      (libsource (lib "resistor") (part "R-US_R1206"))
    )
    (comp (ref "R17")
      (value "0r")
      (footprint "R0603")
      (description "RESISTOR, American symbol")
      (fields (field (name "MANUFACTURER") "Bourns"))
      (libsource (lib "resistor") (part "R-US_R0603"))
    )
    (comp (ref "R18")
      (value "0r")
      (footprint "R0603")
      (description "RESISTOR, American symbol")
      (fields (field (name "MANUFACTURER") "Bourns"))
      (libsource (lib "resistor") (part "R-US_R0603"))
    )
    (comp (ref "R19")
      (value "0r1")
      (footprint "R1206")
      (description "RESISTOR, American symbol")
      (fields (field (name "MANUFACTURER") "Bourns"))
      (libsource (lib "resistor") (part "R-US_R1206"))
    )
    (comp (ref "R20")
      (value "0r1")
      (footprint "R1206")
      (description "RESISTOR, American symbol")
      (fields (field (name "MANUFACTURER") "Bourns"))
      (libsource (lib "resistor") (part "R-US_R1206"))
    )
    (comp (ref "R22")
      (value "0r")
      (footprint "R0603")
      (description "RESISTOR, American symbol")
      (fields (field (name "MANUFACTURER") "Bourns"))
      (libsource (lib "resistor") (part "R-US_R0603"))
    )
    (comp (ref "R23")
      (value "0r1")
      (footprint "R1206")
      (description "RESISTOR, American symbol")
      (fields (field (name "MANUFACTURER") "Bourns"))
      (libsource (lib "resistor") (part "R-US_R1206"))
    )
    (comp (ref "R24")
      (value "0r1")
      (footprint "R1206")
      (description "RESISTOR, American symbol")
      (fields (field (name "MANUFACTURER") "Bourns"))
      (libsource (lib "resistor") (part "R-US_R1206"))
    )
    (comp (ref "R26")
      (value "0r")
      (footprint "R0603")
      (description "RESISTOR, American symbol")
      (fields (field (name "MANUFACTURER") "Bourns"))
      (libsource (lib "resistor") (part "R-US_R0603"))
    )
    (comp (ref "R27")
      (value "2k37")
      (footprint "R0402")
      (description "RES SMD 2.37K OHM 1% 1/16W 0402")
      (fields (field (name "MANUFACTURER") "Yageo") (field (name "PART") "2.37k"))
      (libsource (lib "3Delight") (part "RC0402FR-072K37L"))
    )
    (comp (ref "R28")
      (value "2k37")
      (footprint "R0402")
      (description "RES SMD 2.37K OHM 1% 1/16W 0402")
      (fields (field (name "MANUFACTURER") "Yageo") (field (name "PART") "2.37k"))
      (libsource (lib "3Delight") (part "RC0402FR-072K37L"))
    )
    (comp (ref "R29")
      (value "56r")
      (footprint "R0603")
      (description "RESISTOR, American symbol")
      (fields (field (name "MANUFACTURER") "Vishay"))
      (libsource (lib "resistor") (part "R-US_R0603"))
    )
    (comp (ref "R30")
      (value "3.3K")
      (footprint "R0603")
      (description "RESISTOR, American symbol")
      (fields (field (name "MANUFACTURER") "panasonic"))
      (libsource (lib "resistor") (part "R-US_R0603"))
    )
    (comp (ref "R31")
      (value "4.7k")
      (footprint "R0402")
      (description "RES SMD 4.7K OHM 1% 1/16W 0402")
      (fields (field (name "MANUFACTURER") "Yageo") (field (name "TOLERANCE") "+/- 1%"))
      (libsource (lib "3Delight") (part "RC0402FR-074K7L"))
    )
    (comp (ref "R32")
      (value "2k37")
      (footprint "R0402")
      (description "RES SMD 2.37K OHM 1% 1/16W 0402")
      (fields (field (name "MANUFACTURER") "Yageo") (field (name "PART") "2.37k"))
      (libsource (lib "3Delight") (part "RC0402FR-072K37L"))
    )
    (comp (ref "R33")
      (value "1K")
      (footprint "R0603")
      (description "RESISTOR, American symbol")
      (fields (field (name "MANUFACTURER") "Panasonic"))
      (libsource (lib "resistor") (part "R-US_R0603"))
    )
    (comp (ref "R34")
      (value "1K")
      (footprint "R0603")
      (description "RESISTOR, American symbol")
      (fields (field (name "MANUFACTURER") "Panasonic"))
      (libsource (lib "resistor") (part "R-US_R0603"))
    )
    (comp (ref "R35")
      (value "1K")
      (footprint "R0603")
      (description "RESISTOR, American symbol")
      (fields (field (name "MANUFACTURER") "Panasonic"))
      (libsource (lib "resistor") (part "R-US_R0603"))
    )
    (comp (ref "R36")
      (value "2k37")
      (footprint "R0402")
      (description "RES SMD 2.37K OHM 1% 1/16W 0402")
      (fields (field (name "MANUFACTURER") "Yageo") (field (name "PART") "2.37k"))
      (libsource (lib "3Delight") (part "RC0402FR-072K37L"))
    )
    (comp (ref "R37")
      (value "4.7k")
      (footprint "R0402")
      (description "RES SMD 4.7K OHM 1% 1/16W 0402")
      (fields (field (name "MANUFACTURER") "Yageo") (field (name "TOLERANCE") "+/- 1%"))
      (libsource (lib "3Delight") (part "RC0402FR-074K7L"))
    )
    (comp (ref "R38")
      (value "2k37")
      (footprint "R0402")
      (description "RES SMD 2.37K OHM 1% 1/16W 0402")
      (fields (field (name "MANUFACTURER") "Yageo") (field (name "PART") "2.37k"))
      (libsource (lib "3Delight") (part "RC0402FR-072K37L"))
    )
    (comp (ref "R39")
      (value "2k37")
      (footprint "R0402")
      (description "RES SMD 2.37K OHM 1% 1/16W 0402")
      (fields (field (name "MANUFACTURER") "Yageo") (field (name "PART") "2.37k"))
      (libsource (lib "3Delight") (part "RC0402FR-072K37L"))
    )
    (comp (ref "R40")
      (value "1.8K")
      (footprint "R0603")
      (description "RESISTOR, American symbol")
      (libsource (lib "resistor") (part "R-US_R0603"))
    )
    (comp (ref "R41")
      (value "1.8K")
      (footprint "R0603")
      (description "RESISTOR, American symbol")
      (libsource (lib "resistor") (part "R-US_R0603"))
    )
    (comp (ref "R42")
      (value "100R")
      (footprint "R0402")
      (description "RES SMD 100 OHM 1% 1/16W 0402")
      (fields (field (name "MANUFACTURER") "Yageo") (field (name "PART") "100R 1% 0402"))
      (libsource (lib "Resistors") (part "100R 1% 0402"))
    )
    (comp (ref "R43")
      (value "100K")
      (footprint "R0603")
      (description "RESISTOR, American symbol")
      (fields (field (name "MANUFACTURER") "Yageo"))
      (libsource (lib "resistor") (part "R-US_R0603"))
    )
    (comp (ref "R46")
      (value "10K")
      (footprint "R0603")
      (description "RESISTOR, American symbol")
      (fields (field (name "MANUFACTURER") "Panasonic"))
      (libsource (lib "resistor") (part "R-US_R0603"))
    )
    (comp (ref "R47")
      (value "10K")
      (footprint "R0603")
      (description "RESISTOR, American symbol")
      (fields (field (name "MANUFACTURER") "Panasonic"))
      (libsource (lib "resistor") (part "R-US_R0603"))
    )
    (comp (ref "R48")
      (value "100R")
      (footprint "R0402")
      (description "RES SMD 100 OHM 1% 1/16W 0402")
      (fields (field (name "MANUFACTURER") "Yageo") (field (name "PART") "100R 1% 0402"))
      (libsource (lib "Resistors") (part "100R 1% 0402"))
    )
    (comp (ref "R49")
      (value "100K")
      (footprint "R0603")
      (description "RESISTOR, American symbol")
      (fields (field (name "MANUFACTURER") "Yageo"))
      (libsource (lib "resistor") (part "R-US_R0603"))
    )
    (comp (ref "R50")
      (value "1.8K")
      (footprint "R0603")
      (description "RESISTOR, American symbol")
      (libsource (lib "resistor") (part "R-US_R0603"))
    )
    (comp (ref "R51")
      (value "100R")
      (footprint "R0402")
      (description "RES SMD 100 OHM 1% 1/16W 0402")
      (fields (field (name "MANUFACTURER") "Yageo") (field (name "PART") "100R 1% 0402"))
      (libsource (lib "Resistors") (part "100R 1% 0402"))
    )
    (comp (ref "R52")
      (value "100K")
      (footprint "R0603")
      (description "RESISTOR, American symbol")
      (fields (field (name "MANUFACTURER") "Yageo"))
      (libsource (lib "resistor") (part "R-US_R0603"))
    )
    (comp (ref "R53")
      (value "100R")
      (footprint "R0402")
      (description "RES SMD 100 OHM 1% 1/16W 0402")
      (fields (field (name "MANUFACTURER") "Yageo") (field (name "PART") "100R 1% 0402"))
      (libsource (lib "Resistors") (part "100R 1% 0402"))
    )
    (comp (ref "R54")
      (value "100K")
      (footprint "R0603")
      (description "RESISTOR, American symbol")
      (fields (field (name "MANUFACTURER") "Yageo"))
      (libsource (lib "resistor") (part "R-US_R0603"))
    )
    (comp (ref "R55")
      (value "1.8K")
      (footprint "R0603")
      (description "RESISTOR, American symbol")
      (libsource (lib "resistor") (part "R-US_R0603"))
    )
    (comp (ref "R56")
      (value "100R")
      (footprint "R0402")
      (description "RES SMD 100 OHM 1% 1/16W 0402")
      (fields (field (name "MANUFACTURER") "Yageo") (field (name "PART") "100R 1% 0402"))
      (libsource (lib "Resistors") (part "100R 1% 0402"))
    )
    (comp (ref "R57")
      (value "100K")
      (footprint "R0603")
      (description "RESISTOR, American symbol")
      (fields (field (name "MANUFACTURER") "Yageo"))
      (libsource (lib "resistor") (part "R-US_R0603"))
    )
    (comp (ref "R58")
      (value "1.8K")
      (footprint "R0603")
      (description "RESISTOR, American symbol")
      (libsource (lib "resistor") (part "R-US_R0603"))
    )
    (comp (ref "R59")
      (value "100K")
      (footprint "R0603")
      (description "RESISTOR, American symbol")
      (fields (field (name "MANUFACTURER") "Yageo"))
      (libsource (lib "resistor") (part "R-US_R0603"))
    )
    (comp (ref "R60")
      (value "100K")
      (footprint "R0603")
      (description "RESISTOR, American symbol")
      (fields (field (name "MANUFACTURER") "Yageo"))
      (libsource (lib "resistor") (part "R-US_R0603"))
    )
    (comp (ref "R61")
      (value "100K")
      (footprint "R0603")
      (description "RESISTOR, American symbol")
      (fields (field (name "MANUFACTURER") "Yageo"))
      (libsource (lib "resistor") (part "R-US_R0603"))
    )
    (comp (ref "R62")
      (value "100K")
      (footprint "R0603")
      (description "RESISTOR, American symbol")
      (fields (field (name "MANUFACTURER") "Yageo"))
      (libsource (lib "resistor") (part "R-US_R0603"))
    )
    (comp (ref "R63")
      (value "100K")
      (footprint "R0603")
      (description "RESISTOR, American symbol")
      (fields (field (name "MANUFACTURER") "Yageo"))
      (libsource (lib "resistor") (part "R-US_R0603"))
    )
    (comp (ref "R64")
      (value "22R")
      (footprint "R0402")
      (description "RESISTOR, American symbol")
      (fields (field (name "MANUFACTURER") "Yageo"))
      (libsource (lib "rcl") (part "R-US_R0402"))
    )
    (comp (ref "R65")
      (value "56r")
      (footprint "R0603")
      (description "RESISTOR, American symbol")
      (fields (field (name "MANUFACTURER") "Vishay"))
      (libsource (lib "resistor") (part "R-US_R0603"))
    )
    (comp (ref "R66")
      (value "56r")
      (footprint "R0603")
      (description "RESISTOR, American symbol")
      (fields (field (name "MANUFACTURER") "Vishay"))
      (libsource (lib "resistor") (part "R-US_R0603"))
    )
    (comp (ref "R67")
      (value "56r")
      (footprint "R0603")
      (description "RESISTOR, American symbol")
      (fields (field (name "MANUFACTURER") "Vishay"))
      (libsource (lib "resistor") (part "R-US_R0603"))
    )
    (comp (ref "R68")
      (value "56r")
      (footprint "R0603")
      (description "RESISTOR, American symbol")
      (fields (field (name "MANUFACTURER") "Vishay"))
      (libsource (lib "resistor") (part "R-US_R0603"))
    )
    (comp (ref "R69")
      (value "1.8K")
      (footprint "R0603")
      (description "RESISTOR, American symbol")
      (libsource (lib "resistor") (part "R-US_R0603"))
    )
    (comp (ref "R70")
      (value "100R")
      (footprint "R0402")
      (description "RES SMD 100 OHM 1% 1/16W 0402")
      (fields (field (name "MANUFACTURER") "Yageo") (field (name "PART") "100R 1% 0402"))
      (libsource (lib "Resistors") (part "100R 1% 0402"))
    )
    (comp (ref "R71")
      (value "100K")
      (footprint "R0603")
      (description "RESISTOR, American symbol")
      (fields (field (name "MANUFACTURER") "Yageo"))
      (libsource (lib "resistor") (part "R-US_R0603"))
    )
    (comp (ref "R72")
      (value "1M")
      (footprint "R0402")
      (description "RESISTOR, American symbol")
      (fields (field (name "MANUFACTURER") "Panasonic"))
      (libsource (lib "rcl") (part "R-US_R0402"))
    )
    (comp (ref "R73")
      (value "4.7k")
      (footprint "R0402")
      (description "RES SMD 4.7K OHM 1% 1/16W 0402")
      (fields (field (name "MANUFACTURER") "Yageo") (field (name "TOLERANCE") "+/- 1%"))
      (libsource (lib "3Delight") (part "RC0402FR-074K7L"))
    )
    (comp (ref "R74")
      (value "22R")
      (footprint "R0402")
      (description "RESISTOR, American symbol")
      (fields (field (name "MANUFACTURER") "Yageo"))
      (libsource (lib "rcl") (part "R-US_R0402"))
    )
    (comp (ref "R75")
      (value "22R")
      (footprint "R0402")
      (description "RESISTOR, American symbol")
      (fields (field (name "MANUFACTURER") "Yageo"))
      (libsource (lib "rcl") (part "R-US_R0402"))
    )
    (comp (ref "R76")
      (value "22R")
      (footprint "R0402")
      (description "RESISTOR, American symbol")
      (fields (field (name "MANUFACTURER") "Yageo"))
      (libsource (lib "rcl") (part "R-US_R0402"))
    )
    (comp (ref "R77")
      (value "2k37")
      (footprint "R0402")
      (description "RES SMD 2.37K OHM 1% 1/16W 0402")
      (fields (field (name "MANUFACTURER") "Yageo") (field (name "PART") "2.37k"))
      (libsource (lib "3Delight") (part "RC0402FR-072K37L"))
    )
    (comp (ref "R78")
      (value "2k37")
      (footprint "R0402")
      (description "RES SMD 2.37K OHM 1% 1/16W 0402")
      (fields (field (name "MANUFACTURER") "Yageo") (field (name "PART") "2.37k"))
      (libsource (lib "3Delight") (part "RC0402FR-072K37L"))
    )
    (comp (ref "R79")
      (value "4.7k")
      (footprint "R0402")
      (description "RES SMD 4.7K OHM 1% 1/16W 0402")
      (fields (field (name "MANUFACTURER") "Yageo") (field (name "TOLERANCE") "+/- 1%"))
      (libsource (lib "3Delight") (part "RC0402FR-074K7L"))
    )
    (comp (ref "RN5")
      (value "1k")
      (footprint "CAY16")
      (description "RES ARRAY 4 RES 1K OHM 1206")
      (fields (field (name "MANUFACTURER") "Bourns"))
      (libsource (lib "resistor-dil") (part "4R-NCAY16"))
    )
    (comp (ref "S1")
      (value "31-XX")
      (footprint "B3F-31XX")
      (description "OMRON SWITCHNow with beefier pads!")
      (fields (field (name "MANUFACTURER") "Omron"))
      (libsource (lib "adafruit") (part "31-XX"))
    )
    (comp (ref "TP0")
      (value "PTR1B1,27TH")
      (footprint "B1,27TH")
      (description "TEST PIN")
      (fields (field (name "TP_SIGNAL_NAME") ">TP_SIGNAL_NAME"))
      (libsource (lib "testpad") (part "PTR1B1,27TH"))
    )
    (comp (ref "TP1")
      (value "PTR1B1,27TH")
      (footprint "B1,27TH")
      (description "TEST PIN")
      (fields (field (name "TP_SIGNAL_NAME") ">TP_SIGNAL_NAME"))
      (libsource (lib "testpad") (part "PTR1B1,27TH"))
    )
    (comp (ref "TP2")
      (value "PTR1B1,27TH")
      (footprint "B1,27TH")
      (description "TEST PIN")
      (fields (field (name "TP_SIGNAL_NAME") ">TP_SIGNAL_NAME"))
      (libsource (lib "testpad") (part "PTR1B1,27TH"))
    )
    (comp (ref "TP3")
      (value "PTR1B1,27TH")
      (footprint "B1,27TH")
      (description "TEST PIN")
      (fields (field (name "TP_SIGNAL_NAME") ">TP_SIGNAL_NAME"))
      (libsource (lib "testpad") (part "PTR1B1,27TH"))
    )
    (comp (ref "TP4")
      (value "PTR1B1,27TH")
      (footprint "B1,27TH")
      (description "TEST PIN")
      (fields (field (name "TP_SIGNAL_NAME") ">TP_SIGNAL_NAME"))
      (libsource (lib "") (part "PTR1B1,27TH_1"))
    )
    (comp (ref "TP5")
      (value "PTR1B1,27TH")
      (footprint "B1,27TH")
      (description "TEST PIN")
      (fields (field (name "TP_SIGNAL_NAME") ">TP_SIGNAL_NAME"))
      (libsource (lib "testpad") (part "PTR1B1,27TH"))
    )
    (comp (ref "TP6")
      (value "PTR1B1,27TH")
      (footprint "B1,27TH")
      (description "TEST PIN")
      (fields (field (name "TP_SIGNAL_NAME") ">TP_SIGNAL_NAME"))
      (libsource (lib "testpad") (part "PTR1B1,27TH"))
    )
    (comp (ref "TP7")
      (value "PTR1B1,27TH")
      (footprint "B1,27TH")
      (description "TEST PIN")
      (fields (field (name "TP_SIGNAL_NAME") ">TP_SIGNAL_NAME"))
      (libsource (lib "") (part "PTR1B1,27TH_1"))
    )
    (comp (ref "TP8")
      (value "PTR1B1,27TH")
      (footprint "B1,27TH")
      (description "TEST PIN")
      (fields (field (name "TP_SIGNAL_NAME") ">TP_SIGNAL_NAME"))
      (libsource (lib "testpad") (part "PTR1B1,27TH"))
    )
    (comp (ref "TP9")
      (value "PTR1B1,27TH")
      (footprint "B1,27TH")
      (description "TEST PIN")
      (fields (field (name "TP_SIGNAL_NAME") ">TP_SIGNAL_NAME"))
      (libsource (lib "testpad") (part "PTR1B1,27TH"))
    )
    (comp (ref "TP10")
      (value "PTR1B1,27TH")
      (footprint "B1,27TH")
      (description "TEST PIN")
      (libsource (lib "") (part "PTR1B1,27TH_1"))
    )
    (comp (ref "TP11")
      (value "PTR1B1,27TH")
      (footprint "B1,27TH")
      (description "TEST PIN")
      (fields (field (name "TP_SIGNAL_NAME") ">TP_SIGNAL_NAME"))
      (libsource (lib "testpad") (part "PTR1B1,27TH"))
    )
    (comp (ref "TP12")
      (value "PTR1B1,27TH")
      (footprint "B1,27TH")
      (description "TEST PIN")
      (fields (field (name "TP_SIGNAL_NAME") ">TP_SIGNAL_NAME"))
      (libsource (lib "testpad") (part "PTR1B1,27TH"))
    )
    (comp (ref "TP13")
      (value "PTR1B1,27TH")
      (footprint "B1,27TH")
      (description "TEST PIN")
      (fields (field (name "TP_SIGNAL_NAME") ">TP_SIGNAL_NAME"))
      (libsource (lib "testpad") (part "PTR1B1,27TH"))
    )
    (comp (ref "TP14")
      (value "PTR1B1,27TH")
      (footprint "B1,27TH")
      (description "TEST PIN")
      (libsource (lib "") (part "PTR1B1,27TH_1"))
    )
    (comp (ref "TP15")
      (value "PTR1B1,27TH")
      (footprint "B1,27TH")
      (description "TEST PIN")
      (fields (field (name "TP_SIGNAL_NAME") ">TP_SIGNAL_NAME"))
      (libsource (lib "testpad") (part "PTR1B1,27TH"))
    )
    (comp (ref "TP16")
      (value "PTR1B1,27TH")
      (footprint "B1,27TH")
      (description "TEST PIN")
      (fields (field (name "TP_SIGNAL_NAME") ">TP_SIGNAL_NAME"))
      (libsource (lib "testpad") (part "PTR1B1,27TH"))
    )
    (comp (ref "TP17")
      (value "PTR1B1,27TH")
      (footprint "B1,27TH")
      (description "TEST PIN")
      (fields (field (name "TP_SIGNAL_NAME") ">TP_SIGNAL_NAME"))
      (libsource (lib "testpad") (part "PTR1B1,27TH"))
    )
    (comp (ref "TP18")
      (value "PTR1B1,27TH")
      (footprint "B1,27TH")
      (description "TEST PIN")
      (libsource (lib "") (part "PTR1B1,27TH_1"))
    )
    (comp (ref "TP19")
      (value "PTR1B1,27TH")
      (footprint "B1,27TH")
      (description "TEST PIN")
      (fields (field (name "TP_SIGNAL_NAME") ">TP_SIGNAL_NAME"))
      (libsource (lib "testpad") (part "PTR1B1,27TH"))
    )
    (comp (ref "TP20")
      (value "PTR1B1,27")
      (footprint "B1,27")
      (description "TEST PIN")
      (libsource (lib "testpad") (part "PTR1B1,27"))
    )
    (comp (ref "TP21")
      (value "PTR1B1,27")
      (footprint "B1,27")
      (description "TEST PIN")
      (libsource (lib "testpad") (part "PTR1B1,27"))
    )
    (comp (ref "TP22")
      (value "PTR1B1,27")
      (footprint "B1,27")
      (description "TEST PIN")
      (libsource (lib "testpad") (part "PTR1B1,27"))
    )
    (comp (ref "TP23")
      (value "PTR1B1,27")
      (footprint "B1,27")
      (description "TEST PIN")
      (libsource (lib "testpad") (part "PTR1B1,27"))
    )
    (comp (ref "U1")
      (value "ATMEGA32U2-MUR")
      (footprint "QFN32TROUND")
      (fields (field (name "MANUFACTURER") "Atmel"))
      (libsource (lib "ultimachine") (part "ATMEGA16U2-MU2"))
    )
    (comp (ref "U2")
      (value "Atmega2560")
      (footprint "TSQFP50P1600X1600X120-100L")
      (fields
        (field (name "MANUFACTURER") "Microchip")
        (field (name "PART") "ATMEGA2560")
        (field (name "TOLERANCE") "NA")
      )
      (libsource (lib "ICs-uC") (part "ATMEGA2560AU"))
    )
    (comp (ref "U3")
      (value "LM22675")
      (footprint "SOIC127P600X170-9N")
      (libsource (lib "ultimachine") (part "LM22675"))
    )
    (comp (ref "U4")
      (value "AD5206")
      (footprint "TSSOP24")
      (fields (field (name "MANUFACTURER") "Analog Devices"))
      (libsource (lib "untitled") (part "AD5206"))
    )
    (comp (ref "U5")
      (value "A4982")
      (footprint "QFN50P500X500X100_HS-33L")
      (fields (field (name "MANUFACTURER") "Allegro"))
      (libsource (lib "ultimachine") (part "A4982QFN32ROUNDPADS"))
    )
    (comp (ref "U6")
      (value "A4982")
      (footprint "QFN50P500X500X100_HS-33L")
      (fields (field (name "MANUFACTURER") "Allegro"))
      (libsource (lib "ultimachine") (part "A4982QFN32ROUNDPADS"))
    )
    (comp (ref "U7")
      (value "A4982")
      (footprint "QFN50P500X500X100_HS-33L")
      (fields (field (name "MANUFACTURER") "Allegro"))
      (libsource (lib "ultimachine") (part "A4982QFN32ROUNDPADS"))
    )
    (comp (ref "U8")
      (value "A4982")
      (footprint "QFN50P500X500X100_HS-33L")
      (fields (field (name "MANUFACTURER") "Allegro"))
      (libsource (lib "ultimachine") (part "A4982QFN32ROUNDPADS"))
    )
    (comp (ref "U9")
      (value "A4982")
      (footprint "QFN50P500X500X100_HS-33L")
      (fields (field (name "MANUFACTURER") "Allegro"))
      (libsource (lib "ultimachine") (part "A4982QFN32ROUNDPADS"))
    )
    (comp (ref "U10")
      (value "ADUM7441")
      (footprint "QSOP16")
      (fields (field (name "MANUFACTURER") "Analog Devices"))
      (libsource (lib "ultimachine") (part "ADUM7441"))
    )
    (comp (ref "X2")
      (value "USB B-TH")
      (footprint "PN61729")
      (description "BERG USB connector")
      (fields (field (name "MANUFACTURER") "FCI"))
      (libsource (lib "SmartPrj") (part "PN61729"))
    )
    (comp (ref "X3")
      (value "C-GRID-02-70543")
      (footprint "70543-02")
      (description "CONNECTOR   wire to board 2.54 mm (0.100\") pitch header")
      (fields (field (name "MANUFACTURER") "Molex"))
      (libsource (lib "con-molex") (part "C-GRID-02-70543"))
    )
    (comp (ref "X4")
      (value "C-GRID-04-70543")
      (footprint "4POL254")
      (description "PHOENIX CONNECTOR")
      (fields (field (name "MANUFACTURER") "Molex"))
      (libsource (lib "") (part "MPT4_2"))
    )
    (comp (ref "X6")
      (value "C-GRID-04-70543")
      (footprint "4POL254")
      (description "PHOENIX CONNECTOR")
      (fields (field (name "MANUFACTURER") "Molex"))
      (libsource (lib "con-phoenix-254") (part "MPT4"))
    )
    (comp (ref "X7")
      (value "C-GRID-04-70543")
      (footprint "4POL254")
      (description "PHOENIX CONNECTOR")
      (fields (field (name "MANUFACTURER") "Molex"))
      (libsource (lib "") (part "MPT4_2"))
    )
    (comp (ref "X8")
      (value "C-GRID-04-70543")
      (footprint "4POL254")
      (description "PHOENIX CONNECTOR")
      (fields (field (name "MANUFACTURER") "Molex"))
      (libsource (lib "") (part "MPT4_2"))
    )
    (comp (ref "X9")
      (value "C-GRID-02-70543")
      (footprint "70543-02")
      (description "CONNECTOR   wire to board 2.54 mm (0.100\") pitch header")
      (fields (field (name "MANUFACTURER") "Molex"))
      (libsource (lib "con-molex") (part "C-GRID-02-70543"))
    )
    (comp (ref "X11")
      (value "MSTBV10")
      (footprint "MSTBV10")
      (description "PHOENIX")
      (fields (field (name "MPN") "MSTBV 2,5/10-GF-5.08") (field (name "MANUFACTURER") "Molex"))
      (libsource (lib "") (part "MSTBV10_3"))
    )
    (comp (ref "X14")
      (value "C-GRID-04-70543")
      (footprint "4POL254")
      (description "PHOENIX CONNECTOR")
      (fields (field (name "MANUFACTURER") "Molex"))
      (libsource (lib "con-phoenix-254") (part "MPT4"))
    )
    (comp (ref "X15")
      (value "C-GRID-04-70543")
      (footprint "4POL254")
      (description "PHOENIX CONNECTOR")
      (fields (field (name "MANUFACTURER") "Molex"))
      (libsource (lib "") (part "MPT4_3"))
    )
    (comp (ref "X16") (value "32u2 EXT") (footprint "2X8") (libsource (lib "SparkFun") (part "M08X2")))
    (comp (ref "X17")
      (value "3x2M")
      (footprint "2X03")
      (description "PIN HEADER")
      (libsource (lib "SmartPrj") (part "PINHD-2X3"))
    )
    (comp (ref "X27")
      (value "C-GRID-02-70543")
      (footprint "70543-02")
      (description "CONNECTOR   wire to board 2.54 mm (0.100\") pitch header")
      (fields (field (name "MANUFACTURER") "Molex"))
      (libsource (lib "con-molex") (part "C-GRID-02-70543"))
    )
    (comp (ref "X28")
      (value "C-GRID-02-70543")
      (footprint "70543-02")
      (description "CONNECTOR   wire to board 2.54 mm (0.100\") pitch header")
      (fields (field (name "MANUFACTURER") "Molex"))
      (libsource (lib "con-molex") (part "C-GRID-02-70543"))
    )
    (comp (ref "X29")
      (value "C-GRID-02-70543")
      (footprint "70543-02")
      (description "CONNECTOR   wire to board 2.54 mm (0.100\") pitch header")
      (fields (field (name "MANUFACTURER") "Molex"))
      (libsource (lib "con-molex") (part "C-GRID-02-70543"))
    )
    (comp (ref "X35") (value "M02PTH") (footprint "1X02") (libsource (lib "SparkFun") (part "M02PTH")))
    (comp (ref "X36") (value "M02PTH") (footprint "1X02") (libsource (lib "SparkFun") (part "M02PTH")))
    (comp (ref "X37") (value "M02PTH") (footprint "1X02") (libsource (lib "SparkFun") (part "M02PTH")))
    (comp (ref "X38") (value "M02PTH") (footprint "1X02") (libsource (lib "SparkFun") (part "M02PTH")))
    (comp (ref "X40") (value "Analog") (footprint "2X4") (libsource (lib "SparkFun") (part "M04X2")))
    (comp (ref "Y1")
      (value "16MHz KX-7")
      (footprint "CRYSTAL-3.2-2.5")
      (fields (field (name "MANUFACTURER") "TXC"))
      (libsource (lib "SmartPrj") (part "CRYSTAL-3.2-2.5"))
    )
    (comp (ref "Y2")
      (value "16MHz KX-7")
      (footprint "CRYSTAL-3.2-2.5")
      (fields (field (name "MANUFACTURER") "TXC"))
      (libsource (lib "SmartPrj") (part "CRYSTAL-3.2-2.5"))
    )
    (comp (ref "Z1")
      (value "CG0603MLC-05E")
      (footprint "R0603")
      (description "RESISTOR, American symbol")
      (fields (field (name "MANUFACTURER") "Bourns"))
      (libsource (lib "resistor") (part "R-US_R0603"))
    )
    (comp (ref "Z2")
      (value "CG0603MLC-05E")
      (footprint "R0603")
      (description "RESISTOR, American symbol")
      (fields (field (name "MANUFACTURER") "Bourns"))
      (libsource (lib "resistor") (part "R-US_R0603"))
    )
    (comp (ref "Z3")
      (value "CG0603MLC-05E")
      (footprint "R0603")
      (description "RESISTOR, American symbol")
      (fields (field (name "MANUFACTURER") "Bourns"))
      (libsource (lib "resistor") (part "R-US_R0603"))
    )
  )
  (nets
    (net (code "1") (name "/AREF") (class "Default")
      (node (ref "C6") (pin "1") (pinfunction "1_1") (pintype "passive"))
      (node (ref "U2") (pin "98") (pinfunction "AREF_98") (pintype "passive"))
    )
    (net (code "2") (name "/BED-HEAT") (class "Default")
      (node (ref "R56") (pin "1") (pinfunction "1_1") (pintype "passive"))
      (node (ref "R57") (pin "1") (pinfunction "1_1") (pintype "passive"))
      (node (ref "U2") (pin "7") (pinfunction "(OC3C/INT5)PE5_7") (pintype "passive"))
    )
    (net (code "3") (name "/D+") (class "Default")
      (node (ref "R2") (pin "1") (pinfunction "1_1") (pintype "passive"))
      (node (ref "X2") (pin "3") (pinfunction "3_3") (pintype "passive"))
      (node (ref "Z2") (pin "2") (pinfunction "2_2") (pintype "passive"))
    )
    (net (code "4") (name "/D-") (class "Default")
      (node (ref "R1") (pin "1") (pinfunction "1_1") (pintype "passive"))
      (node (ref "X2") (pin "2") (pinfunction "2_2") (pintype "passive"))
      (node (ref "Z1") (pin "2") (pinfunction "2_2") (pintype "passive"))
    )
    (net (code "5") (name "/DP-SS") (class "Default")
      (node (ref "U2") (pin "50") (pinfunction "(T0)PD7_50") (pintype "passive"))
      (node (ref "U4") (pin "P05") (pinfunction "_CS_P05") (pintype "passive"))
    )
    (net (code "6") (name "/DTR") (class "Default")
      (node (ref "JP2") (pin "1") (pinfunction "1_1") (pintype "passive"))
      (node (ref "JP2") (pin "2") (pinfunction "2_2") (pintype "passive"))
      (node (ref "RN5") (pin "5") (pinfunction "2_5") (pintype "passive"))
      (node (ref "U1") (pin "13") (pinfunction "(CTS/HWB/AIN6/TO/INT7)PD7_13") (pintype "passive"))
      (node (ref "U10") (pin "3") (pinfunction "VIA_3") (pintype "passive"))
    )
    (net (code "7") (name "/E0-DIR") (class "Default")
      (node (ref "TP11") (pin "TP") (pinfunction "TP_TP") (pintype "passive"))
      (node (ref "U2") (pin "41") (pinfunction "PL6_41") (pintype "passive"))
      (node (ref "U8") (pin "20") (pinfunction "DIR_20") (pintype "passive"))
    )
    (net (code "8") (name "/E0-EN") (class "Default")
      (node (ref "R62") (pin "2") (pinfunction "2_2") (pintype "passive"))
      (node (ref "TP14") (pin "TP") (pinfunction "TP_TP") (pintype "passive"))
      (node (ref "U2") (pin "74") (pinfunction "(AD4)PA4_74") (pintype "passive"))
      (node (ref "U8") (pin "5") (pinfunction "EN_5") (pintype "passive"))
    )
    (net (code "9") (name "/E0-MS1") (class "Default")
      (node (ref "U2") (pin "86") (pinfunction "PK3(ADC11/PCINT19)_86") (pintype "passive"))
      (node (ref "U8") (pin "11") (pinfunction "MS1_11") (pintype "passive"))
    )
    (net (code "10") (name "/E0-MS2") (class "Default")
      (node (ref "U2") (pin "85") (pinfunction "PK4(ADC12/PCINT20)_85") (pintype "passive"))
      (node (ref "U8") (pin "12") (pinfunction "MS2_12") (pintype "passive"))
    )
    (net (code "11") (name "/E0-REF") (class "Default")
      (node (ref "TP12") (pin "TP") (pinfunction "TP_TP") (pintype "passive"))
      (node (ref "U4") (pin "P17") (pinfunction "W1_P17") (pintype "passive"))
      (node (ref "U8") (pin "18") (pinfunction "REF_18") (pintype "passive"))
    )
    (net (code "12") (name "/E0-STEP") (class "Default")
      (node (ref "TP13") (pin "TP") (pinfunction "TP_TP") (pintype "passive"))
      (node (ref "U2") (pin "56") (pinfunction "(A11)PC3_56") (pintype "passive"))
      (node (ref "U8") (pin "17") (pinfunction "STEP_17") (pintype "passive"))
    )
    (net (code "13") (name "/E1-DIR") (class "Default")
      (node (ref "TP15") (pin "TP") (pinfunction "TP_TP") (pintype "passive"))
      (node (ref "U2") (pin "42") (pinfunction "PL7_42") (pintype "passive"))
      (node (ref "U9") (pin "20") (pinfunction "DIR_20") (pintype "passive"))
    )
    (net (code "14") (name "/E1-EN") (class "Default")
      (node (ref "R63") (pin "2") (pinfunction "2_2") (pintype "passive"))
      (node (ref "TP18") (pin "TP") (pinfunction "TP_TP") (pintype "passive"))
      (node (ref "U2") (pin "75") (pinfunction "(AD3)PA3_75") (pintype "passive"))
      (node (ref "U9") (pin "5") (pinfunction "EN_5") (pintype "passive"))
    )
    (net (code "15") (name "/E1-MS1") (class "Default")
      (node (ref "U2") (pin "88") (pinfunction "PK1(ADC9/PCINT17)_88") (pintype "passive"))
      (node (ref "U9") (pin "11") (pinfunction "MS1_11") (pintype "passive"))
    )
    (net (code "16") (name "/E1-MS2") (class "Default")
      (node (ref "U2") (pin "87") (pinfunction "PK2(ADC10/PCINT18)_87") (pintype "passive"))
      (node (ref "U9") (pin "12") (pinfunction "MS2_12") (pintype "passive"))
    )
    (net (code "17") (name "/E1-REF") (class "Default")
      (node (ref "TP17") (pin "TP") (pinfunction "TP_TP") (pintype "passive"))
      (node (ref "U4") (pin "P20") (pinfunction "W2_P20") (pintype "passive"))
      (node (ref "U9") (pin "18") (pinfunction "REF_18") (pintype "passive"))
    )
    (net (code "18") (name "/E1-STEP") (class "Default")
      (node (ref "TP16") (pin "TP") (pinfunction "TP_TP") (pintype "passive"))
      (node (ref "U2") (pin "57") (pinfunction "(A12)PC4_57") (pintype "passive"))
      (node (ref "U9") (pin "17") (pinfunction "STEP_17") (pintype "passive"))
    )
    (net (code "19") (name "/FAN-0") (class "Default")
      (node (ref "R48") (pin "1") (pinfunction "1_1") (pintype "passive"))
      (node (ref "R49") (pin "1") (pinfunction "1_1") (pintype "passive"))
      (node (ref "U2") (pin "17") (pinfunction "PH5(OC4C)_17") (pintype "passive"))
    )
    (net (code "20") (name "/FAN-1") (class "Default")
      (node (ref "R53") (pin "1") (pinfunction "1_1") (pintype "passive"))
      (node (ref "R54") (pin "1") (pinfunction "1_1") (pintype "passive"))
      (node (ref "U2") (pin "15") (pinfunction "PH3(OC4A)_15") (pintype "passive"))
    )
    (net (code "21") (name "/FAN-2") (class "Default")
      (node (ref "R70") (pin "1") (pinfunction "1_1") (pintype "passive"))
      (node (ref "R71") (pin "1") (pinfunction "1_1") (pintype "passive"))
      (node (ref "U2") (pin "6") (pinfunction "(OC3B/INT4)PE4_6") (pintype "passive"))
    )
    (net (code "22") (name "/HEAT-0") (class "Default")
      (node (ref "R42") (pin "1") (pinfunction "1_1") (pintype "passive"))
      (node (ref "R43") (pin "1") (pinfunction "1_1") (pintype "passive"))
      (node (ref "U2") (pin "18") (pinfunction "PH6(OC2B)_18") (pintype "passive"))
    )
    (net (code "23") (name "/HEAT-1") (class "Default")
      (node (ref "R51") (pin "1") (pinfunction "1_1") (pintype "passive"))
      (node (ref "R52") (pin "1") (pinfunction "1_1") (pintype "passive"))
      (node (ref "U2") (pin "16") (pinfunction "PH4(OC4B)_16") (pintype "passive"))
    )
    (net (code "24") (name "/L13") (class "Default")
      (node (ref "R33") (pin "1") (pinfunction "1_1") (pintype "passive"))
      (node (ref "U2") (pin "26") (pinfunction "(OC0A/OC1C/PCINT7)PB7_26") (pintype "passive"))
    )
    (net (code "25") (name "/MISO2") (class "Default")
      (node (ref "U1") (pin "17") (pinfunction "(PD0/MISO/PCINT3)PB3_17") (pintype "passive"))
      (node (ref "X17") (pin "1") (pinfunction "1_1") (pintype "passive"))
    )
    (net (code "26") (name "/MOSI2") (class "Default")
      (node (ref "U1") (pin "16") (pinfunction "(PDI/MOSI/PCINT2)PB2_16") (pintype "passive"))
      (node (ref "X17") (pin "4") (pinfunction "4_4") (pintype "passive"))
    )
    (net (code "28") (name "/PA0") (class "Default")
      (node (ref "U2") (pin "78") (pinfunction "(AD0)PA0_78") (pintype "passive"))
    )
    (net (code "29") (name "/PA1") (class "Default")
      (node (ref "U2") (pin "77") (pinfunction "(AD1)PA1_77") (pintype "passive"))
    )
    (net (code "30") (name "/PA2") (class "Default")
      (node (ref "U2") (pin "76") (pinfunction "(AD2)PA2_76") (pintype "passive"))
    )
    (net (code "31") (name "/PB0_SS") (class "Default")
      (node (ref "R76") (pin "2") (pinfunction "2_2") (pintype "passive"))
    )
    (net (code "32") (name "/PB1_SCK") (class "Default")
      (node (ref "R75") (pin "2") (pinfunction "2_2") (pintype "passive"))
      (node (ref "U4") (pin "P08") (pinfunction "SCK_P08") (pintype "passive"))
    )
    (net (code "33") (name "/PB2_MOSI") (class "Default")
      (node (ref "R74") (pin "2") (pinfunction "2_2") (pintype "passive"))
      (node (ref "U4") (pin "P07") (pinfunction "SDI_P07") (pintype "passive"))
    )
    (net (code "34") (name "/PB3_MISO") (class "Default")
      (node (ref "R64") (pin "2") (pinfunction "2_2") (pintype "passive"))
    )
    (net (code "35") (name "/PC5") (class "Default")
      (node (ref "U2") (pin "58") (pinfunction "(A13)PC5_58") (pintype "passive"))
    )
    (net (code "36") (name "/PC6") (class "Default")
      (node (ref "U2") (pin "59") (pinfunction "(A14)PC6_59") (pintype "passive"))
    )
    (net (code "37") (name "/PC7") (class "Default")
      (node (ref "U2") (pin "60") (pinfunction "(A15)PC7_60") (pintype "passive"))
    )
    (net (code "38") (name "/PD4") (class "Default")
      (node (ref "U2") (pin "47") (pinfunction "(ICP1)PD4_47") (pintype "passive"))
    )
    (net (code "39") (name "/PD5") (class "Default")
      (node (ref "U2") (pin "48") (pinfunction "(XCK1)PD5_48") (pintype "passive"))
    )
    (net (code "40") (name "/PD6") (class "Default")
      (node (ref "U2") (pin "49") (pinfunction "(T1)PD6_49") (pintype "passive"))
    )
    (net (code "41") (name "/PE2") (class "Default")
      (node (ref "U2") (pin "4") (pinfunction "(XCK0/AIN0)PE2_4") (pintype "passive"))
    )
    (net (code "42") (name "/PE3") (class "Default")
      (node (ref "U2") (pin "5") (pinfunction "(OC3A/AIN1)PE3_5") (pintype "passive"))
    )
    (net (code "43") (name "/PE6") (class "Default")
      (node (ref "U2") (pin "8") (pinfunction "(T3/INT6)PE6_8") (pintype "passive"))
    )
    (net (code "44") (name "/PE7") (class "Default")
      (node (ref "U2") (pin "9") (pinfunction "(CLKO/ICP3/INT7)PE7_9") (pintype "passive"))
    )
    (net (code "45") (name "/PF3") (class "Default")
      (node (ref "U2") (pin "94") (pinfunction "(ADC3)PF3_94") (pintype "passive"))
      (node (ref "X40") (pin "4") (pinfunction "4_4") (pintype "passive"))
    )
    (net (code "46") (name "/PF4") (class "Default")
      (node (ref "U2") (pin "93") (pinfunction "(ADC4/TCK)PF4_93") (pintype "passive"))
      (node (ref "X40") (pin "6") (pinfunction "6_6") (pintype "passive"))
    )
    (net (code "47") (name "/PF5") (class "Default")
      (node (ref "U2") (pin "92") (pinfunction "(ADC5/TMS)PF5_92") (pintype "passive"))
      (node (ref "X40") (pin "8") (pinfunction "8_8") (pintype "passive"))
    )
    (net (code "48") (name "/PF6") (class "Default")
      (node (ref "U2") (pin "91") (pinfunction "(ADC6/TDO)PF6_91") (pintype "passive"))
      (node (ref "X40") (pin "3") (pinfunction "3_3") (pintype "passive"))
    )
    (net (code "49") (name "/PG3") (class "Default")
      (node (ref "U2") (pin "28") (pinfunction "(TOSC2)PG3_28") (pintype "passive"))
    )
    (net (code "50") (name "/PG4") (class "Default")
      (node (ref "U2") (pin "29") (pinfunction "(TOSC1)PG4_29") (pintype "passive"))
    )
    (net (code "51") (name "/PG5") (class "Default")
      (node (ref "U2") (pin "1") (pinfunction "(OC0B)PG5_1") (pintype "passive"))
    )
    (net (code "52") (name "/PH2") (class "Default")
      (node (ref "U2") (pin "14") (pinfunction "PH2(XCK2)_14") (pintype "passive"))
    )
    (net (code "53") (name "/PH7") (class "Default")
      (node (ref "U2") (pin "27") (pinfunction "PH7(T4)_27") (pintype "passive"))
    )
    (net (code "54") (name "/PJ2") (class "Default")
      (node (ref "U2") (pin "65") (pinfunction "PJ2(XCK3/PCINT11)_65") (pintype "passive"))
    )
    (net (code "55") (name "/PJ3") (class "Default")
      (node (ref "U2") (pin "66") (pinfunction "PJ3(PCINT12)_66") (pintype "passive"))
    )
    (net (code "56") (name "/PJ4") (class "Default")
      (node (ref "U2") (pin "67") (pinfunction "PJ4(PCINT13)_67") (pintype "passive"))
    )
    (net (code "57") (name "/PJ5") (class "Default")
      (node (ref "U2") (pin "68") (pinfunction "PJ5(PCINT14)_68") (pintype "passive"))
    )
    (net (code "58") (name "/PJ6") (class "Default")
      (node (ref "U2") (pin "69") (pinfunction "PJ6(PCINT15)_69") (pintype "passive"))
    )
    (net (code "59") (name "/PJ7") (class "Default")
      (node (ref "U2") (pin "79") (pinfunction "PJ7_79") (pintype "passive"))
    )
    (net (code "60") (name "/PK0") (class "Default")
      (node (ref "U2") (pin "89") (pinfunction "PK0(ADC8/PCINT16)_89") (pintype "passive"))
      (node (ref "X40") (pin "7") (pinfunction "7_7") (pintype "passive"))
    )
    (net (code "61") (name "/PL3") (class "Default")
      (node (ref "U2") (pin "38") (pinfunction "PL3(OC5A)_38") (pintype "passive"))
    )
    (net (code "62") (name "/PL4") (class "Default")
      (node (ref "U2") (pin "39") (pinfunction "PL4(OC5B)_39") (pintype "passive"))
    )
    (net (code "63") (name "/PL5") (class "Default")
      (node (ref "U2") (pin "40") (pinfunction "PL5(OC5C)_40") (pintype "passive"))
    )
    (net (code "64") (name "/RD+") (class "Default")
      (node (ref "R2") (pin "2") (pinfunction "2_2") (pintype "passive"))
      (node (ref "U1") (pin "29") (pinfunction "D+_29") (pintype "passive"))
    )
    (net (code "65") (name "/RD-") (class "Default")
      (node (ref "R1") (pin "2") (pinfunction "2_2") (pintype "passive"))
      (node (ref "U1") (pin "30") (pinfunction "D-_30") (pintype "passive"))
    )
    (net (code "66") (name "/RESET") (class "Default")
      (node (ref "C1") (pin "1") (pinfunction "1_1") (pintype "passive"))
      (node (ref "C10") (pin "2") (pinfunction "2_2") (pintype "passive"))
      (node (ref "D5") (pin "A") (pinfunction "A_A") (pintype "passive"))
      (node (ref "R46") (pin "1") (pinfunction "1_1") (pintype "passive"))
      (node (ref "S1") (pin "1") (pinfunction "P_1") (pintype "passive"))
      (node (ref "U2") (pin "30") (pinfunction "RESET_30") (pintype "passive"))
    )
    (net (code "67") (name "/RESET2") (class "Default")
      (node (ref "D4") (pin "A") (pinfunction "A_A") (pintype "passive"))
      (node (ref "R47") (pin "1") (pinfunction "1_1") (pintype "passive"))
      (node (ref "U1") (pin "24") (pinfunction "RESET(PC1/DW)_24") (pintype "passive"))
      (node (ref "X17") (pin "5") (pinfunction "5_5") (pintype "passive"))
    )
    (net (code "68") (name "/RST-IO") (class "Default")
      (node (ref "C10") (pin "1") (pinfunction "1_1") (pintype "passive"))
      (node (ref "U10") (pin "14") (pinfunction "VOA_14") (pintype "passive"))
    )
    (net (code "69") (name "/RX0") (class "Default")
      (node (ref "R34") (pin "2") (pinfunction "2_2") (pintype "passive"))
      (node (ref "U2") (pin "2") (pinfunction "(RXD0/PCIN8)PE0_2") (pintype "passive"))
    )
    (net (code "70") (name "/RX0-I") (class "Default")
      (node (ref "U1") (pin "9") (pinfunction "(TXD1/INT3)PD3_9") (pintype "passive"))
      (node (ref "U10") (pin "5") (pinfunction "VIC_5") (pintype "passive"))
    )
    (net (code "71") (name "/RX1") (class "Default")
      (node (ref "U2") (pin "45") (pinfunction "(RXD1/INT2)PD2_45") (pintype "passive"))
    )
    (net (code "72") (name "/RX2") (class "Default")
      (node (ref "U2") (pin "12") (pinfunction "PH0(RXD2)_12") (pintype "passive"))
    )
    (net (code "73") (name "/RX3") (class "Default")
      (node (ref "U2") (pin "63") (pinfunction "PJ0(RXD3/PCINT9)_63") (pintype "passive"))
    )
    (net (code "74") (name "/RXL") (class "Default")
      (node (ref "LED10") (pin "C") (pinfunction "C_C") (pintype "passive"))
      (node (ref "U1") (pin "10") (pinfunction "(INT5/AIN3)PD4_10") (pintype "passive"))
    )
    (net (code "75") (name "/SCK2") (class "Default")
      (node (ref "U1") (pin "15") (pinfunction "(SCLK/PCINT1)PB1_15") (pintype "passive"))
      (node (ref "X17") (pin "3") (pinfunction "3_3") (pintype "passive"))
    )
    (net (code "76") (name "/SCL") (class "Default")
      (node (ref "U2") (pin "43") (pinfunction "(SCL/INT0)PD0_43") (pintype "passive"))
    )
    (net (code "77") (name "/SDA") (class "Default")
      (node (ref "U2") (pin "44") (pinfunction "(SDA/INT1)PD1_44") (pintype "passive"))
    )
    (net (code "78") (name "/THERM0") (class "Default")
      (node (ref "C3") (pin "1") (pinfunction "1_1") (pintype "passive"))
      (node (ref "R27") (pin "2") (pinfunction "2_2") (pintype "passive"))
      (node (ref "U2") (pin "97") (pinfunction "(ADC0)PF0_97") (pintype "passive"))
    )
    (net (code "79") (name "/THERM1") (class "Default")
      (node (ref "C56") (pin "1") (pinfunction "1_1") (pintype "passive"))
      (node (ref "R32") (pin "2") (pinfunction "2_2") (pintype "passive"))
      (node (ref "U2") (pin "96") (pinfunction "(ADC1)PF1_96") (pintype "passive"))
    )
    (net (code "80") (name "/THERM2") (class "Default")
      (node (ref "C59") (pin "1") (pinfunction "1_1") (pintype "passive"))
      (node (ref "R38") (pin "2") (pinfunction "2_2") (pintype "passive"))
      (node (ref "U2") (pin "95") (pinfunction "(ADC2)PF2_95") (pintype "passive"))
    )
    (net (code "81") (name "/THERM3") (class "Default")
      (node (ref "C64") (pin "1") (pinfunction "1_1") (pintype "passive"))
      (node (ref "R77") (pin "2") (pinfunction "2_2") (pintype "passive"))
      (node (ref "U2") (pin "90") (pinfunction "(ADC7/TDI)PF7_90") (pintype "passive"))
      (node (ref "X40") (pin "5") (pinfunction "5_5") (pintype "passive"))
    )
    (net (code "82") (name "/TX0") (class "Default")
      (node (ref "U10") (pin "11") (pinfunction "VID_11") (pintype "passive"))
      (node (ref "U2") (pin "3") (pinfunction "(TXD0)PE1_3") (pintype "passive"))
    )
    (net (code "83") (name "/TX0-I") (class "Default")
      (node (ref "U1") (pin "8") (pinfunction "(RXD1/AIN1/INT2)PD2_8") (pintype "passive"))
      (node (ref "U10") (pin "6") (pinfunction "VOD_6") (pintype "passive"))
    )
    (net (code "84") (name "/TX1") (class "Default")
      (node (ref "U2") (pin "46") (pinfunction "(TXD1/INT3)PD3_46") (pintype "passive"))
    )
    (net (code "85") (name "/TX2") (class "Default")
      (node (ref "U2") (pin "13") (pinfunction "PH1(TXD2)_13") (pintype "passive"))
    )
    (net (code "86") (name "/TX3") (class "Default")
      (node (ref "U2") (pin "64") (pinfunction "PJ1(TXD3/PCINT10)_64") (pintype "passive"))
    )
    (net (code "87") (name "/TXL") (class "Default")
      (node (ref "LED9") (pin "C") (pinfunction "C_C") (pintype "passive"))
      (node (ref "U1") (pin "11") (pinfunction "(XCK/AIN4/PCINT12)PD5_11") (pintype "passive"))
    )
    (net (code "88") (name "/U1-PB0") (class "Default")
      (node (ref "U1") (pin "14") (pinfunction "(SS/PCINT0)PB0_14") (pintype "passive"))
      (node (ref "X16") (pin "7") (pinfunction "7_7") (pintype "passive"))
    )
    (net (code "89") (name "/U1-PB4") (class "Default")
      (node (ref "U1") (pin "18") (pinfunction "(T1/PCINT4)PB4_18") (pintype "passive"))
      (node (ref "X16") (pin "9") (pinfunction "9_9") (pintype "passive"))
    )
    (net (code "90") (name "/U1-PB5") (class "Default")
      (node (ref "U1") (pin "19") (pinfunction "(PCINT5)PB5_19") (pintype "passive"))
      (node (ref "X16") (pin "12") (pinfunction "12_12") (pintype "passive"))
    )
    (net (code "91") (name "/U1-PB6") (class "Default")
      (node (ref "U1") (pin "20") (pinfunction "(PCINT6)PB6_20") (pintype "passive"))
      (node (ref "X16") (pin "11") (pinfunction "11_11") (pintype "passive"))
    )
    (net (code "92") (name "/U1-PB7") (class "Default")
      (node (ref "U1") (pin "21") (pinfunction "(PCINT7/OC0A/OC1C)PB7_21") (pintype "passive"))
      (node (ref "X16") (pin "14") (pinfunction "14_14") (pintype "passive"))
    )
    (net (code "93") (name "/U1-PC2") (class "Default")
      (node (ref "U1") (pin "5") (pinfunction "(AIN2/PCINT11)PC2_5") (pintype "passive"))
      (node (ref "X16") (pin "5") (pinfunction "5_5") (pintype "passive"))
    )
    (net (code "94") (name "/U1-PC5") (class "Default")
      (node (ref "U1") (pin "25") (pinfunction "(PCINT9/OC1B)PC5_25") (pintype "passive"))
      (node (ref "X16") (pin "15") (pinfunction "15_15") (pintype "passive"))
    )
    (net (code "95") (name "/U1-PC6") (class "Default")
      (node (ref "U1") (pin "23") (pinfunction "(OC1A/PCINT8)PC6_23") (pintype "passive"))
      (node (ref "X16") (pin "16") (pinfunction "16_16") (pintype "passive"))
    )
    (net (code "96") (name "/U1-PC7") (class "Default")
      (node (ref "U1") (pin "22") (pinfunction "(INT4/ICP1/CLK0)PC7_22") (pintype "passive"))
      (node (ref "X16") (pin "13") (pinfunction "13_13") (pintype "passive"))
    )
    (net (code "97") (name "/U1-PD0") (class "Default")
      (node (ref "U1") (pin "6") (pinfunction "(OC0B/INT0)PD0_6") (pintype "passive"))
      (node (ref "X16") (pin "10") (pinfunction "10_10") (pintype "passive"))
    )
    (net (code "98") (name "/U1-PD1") (class "Default")
      (node (ref "U1") (pin "7") (pinfunction "(AIN0/INT1)PD1_7") (pintype "passive"))
      (node (ref "X16") (pin "8") (pinfunction "8_8") (pintype "passive"))
    )
    (net (code "99") (name "/U1-PD6") (class "Default")
      (node (ref "U1") (pin "12") (pinfunction "(RTS/AIN5/INT6)PD6_12") (pintype "passive"))
      (node (ref "X16") (pin "6") (pinfunction "6_6") (pintype "passive"))
    )
    (net (code "100") (name "/USBVCC") (class "Default")
      (node (ref "C11") (pin "1") (pinfunction "1_1") (pintype "passive"))
      (node (ref "C14") (pin "1") (pinfunction "1_1") (pintype "passive"))
      (node (ref "C15") (pin "1") (pinfunction "1_1") (pintype "passive"))
      (node (ref "C19") (pin "1") (pinfunction "1_1") (pintype "passive"))
      (node (ref "C2") (pin "2") (pinfunction "2_2") (pintype "passive"))
      (node (ref "C5") (pin "1") (pinfunction "1_1") (pintype "passive"))
      (node (ref "D4") (pin "C") (pinfunction "C_C") (pintype "passive"))
      (node (ref "F1") (pin "1") (pinfunction "1_1") (pintype "passive"))
      (node (ref "R47") (pin "2") (pinfunction "2_2") (pintype "passive"))
      (node (ref "RN5") (pin "2") (pinfunction "1_2") (pintype "passive"))
      (node (ref "RN5") (pin "3") (pinfunction "1_3") (pintype "passive"))
      (node (ref "RN5") (pin "4") (pinfunction "1_4") (pintype "passive"))
      (node (ref "U1") (pin "31") (pinfunction "UVCC_31") (pintype "power_in"))
      (node (ref "U1") (pin "32") (pinfunction "AVCC_32") (pintype "power_in"))
      (node (ref "U1") (pin "4") (pinfunction "VCC_4") (pintype "power_in"))
      (node (ref "U10") (pin "1") (pinfunction "VDD1A_1") (pintype "passive"))
      (node (ref "U10") (pin "7") (pinfunction "VDD1B_7") (pintype "passive"))
      (node (ref "X16") (pin "1") (pinfunction "1_1") (pintype "passive"))
      (node (ref "X16") (pin "2") (pinfunction "2_2") (pintype "passive"))
      (node (ref "X17") (pin "2") (pinfunction "2_2") (pintype "passive"))
      (node (ref "Z3") (pin "1") (pinfunction "1_1") (pintype "passive"))
    )
    (net (code "101") (name "/USHIELD") (class "Default")
      (node (ref "C63") (pin "1") (pinfunction "1_1") (pintype "passive"))
      (node (ref "R72") (pin "2") (pinfunction "2_2") (pintype "passive"))
      (node (ref "X2") (pin "P$1") (pinfunction "P$1_P$1") (pintype "passive"))
      (node (ref "X2") (pin "P$2") (pinfunction "P$2_P$2") (pintype "passive"))
      (node (ref "Z1") (pin "1") (pinfunction "1_1") (pintype "passive"))
      (node (ref "Z2") (pin "1") (pinfunction "1_1") (pintype "passive"))
    )
    (net (code "102") (name "/VUCAP") (class "Default")
      (node (ref "C16") (pin "1") (pinfunction "1_1") (pintype "passive"))
      (node (ref "U1") (pin "27") (pinfunction "UCAP_27") (pintype "passive"))
    )
    (net (code "103") (name "/X-DIR") (class "Default")
      (node (ref "TP1") (pin "TP") (pinfunction "TP_TP") (pintype "passive"))
      (node (ref "U2") (pin "36") (pinfunction "PL1(ICP5)_36") (pintype "passive"))
      (node (ref "U5") (pin "20") (pinfunction "DIR_20") (pintype "passive"))
    )
    (net (code "104") (name "/X-EN") (class "Default")
      (node (ref "R60") (pin "2") (pinfunction "2_2") (pintype "passive"))
      (node (ref "TP4") (pin "TP") (pinfunction "TP_TP") (pintype "passive"))
      (node (ref "U2") (pin "71") (pinfunction "(AD7)PA7_71") (pintype "passive"))
      (node (ref "U5") (pin "5") (pinfunction "EN_5") (pintype "passive"))
    )
    (net (code "105") (name "/X-MIN") (class "Default")
      (node (ref "U2") (pin "25") (pinfunction "(OC1B/PCINT6)PB6_25") (pintype "passive"))
    )
    (net (code "106") (name "/X-MS1") (class "Default")
      (node (ref "U2") (pin "52") (pinfunction "(RD)PG1_52") (pintype "passive"))
      (node (ref "U5") (pin "11") (pinfunction "MS1_11") (pintype "passive"))
    )
    (net (code "107") (name "/X-MS2") (class "Default")
      (node (ref "U2") (pin "51") (pinfunction "(WR)PG0_51") (pintype "passive"))
      (node (ref "U5") (pin "12") (pinfunction "MS2_12") (pintype "passive"))
    )
    (net (code "108") (name "/X-REF") (class "Default")
      (node (ref "TP3") (pin "TP") (pinfunction "TP_TP") (pintype "passive"))
      (node (ref "U4") (pin "P11") (pinfunction "W5_P11") (pintype "passive"))
      (node (ref "U5") (pin "18") (pinfunction "REF_18") (pintype "passive"))
    )
    (net (code "109") (name "/X-STEP") (class "Default")
      (node (ref "TP2") (pin "TP") (pinfunction "TP_TP") (pintype "passive"))
      (node (ref "U2") (pin "53") (pinfunction "(A8)PC0_53") (pintype "passive"))
      (node (ref "U5") (pin "17") (pinfunction "STEP_17") (pintype "passive"))
    )
    (net (code "110") (name "/XT1") (class "Default")
      (node (ref "C13") (pin "1") (pinfunction "1_1") (pintype "passive"))
      (node (ref "U1") (pin "1") (pinfunction "XTAL1_1") (pintype "passive"))
      (node (ref "Y2") (pin "1") (pinfunction "C1_1") (pintype "passive"))
    )
    (net (code "111") (name "/XT2") (class "Default")
      (node (ref "C12") (pin "1") (pinfunction "1_1") (pintype "passive"))
      (node (ref "U1") (pin "2") (pinfunction "XTAL2(PC0)_2") (pintype "passive"))
      (node (ref "Y2") (pin "3") (pinfunction "C2_3") (pintype "passive"))
    )
    (net (code "112") (name "/XTAL1") (class "Default")
      (node (ref "C57") (pin "1") (pinfunction "1_1") (pintype "passive"))
      (node (ref "U2") (pin "34") (pinfunction "XTAL1_34") (pintype "passive"))
      (node (ref "Y1") (pin "1") (pinfunction "C1_1") (pintype "passive"))
    )
    (net (code "113") (name "/XTAL2") (class "Default")
      (node (ref "C58") (pin "1") (pinfunction "1_1") (pintype "passive"))
      (node (ref "U2") (pin "33") (pinfunction "XTAL2_33") (pintype "output"))
      (node (ref "Y1") (pin "3") (pinfunction "C2_3") (pintype "passive"))
    )
    (net (code "114") (name "/XVCC") (class "Default")
      (node (ref "F1") (pin "2") (pinfunction "2_2") (pintype "passive"))
      (node (ref "X2") (pin "1") (pinfunction "1_1") (pintype "passive"))
    )
    (net (code "115") (name "/Y-DIR") (class "Default")
      (node (ref "TP0") (pin "TP") (pinfunction "TP_TP") (pintype "passive"))
      (node (ref "U2") (pin "35") (pinfunction "PL0(ICP4)_35") (pintype "passive"))
      (node (ref "U6") (pin "20") (pinfunction "DIR_20") (pintype "passive"))
    )
    (net (code "116") (name "/Y-EN") (class "Default")
      (node (ref "R59") (pin "2") (pinfunction "2_2") (pintype "passive"))
      (node (ref "TP7") (pin "TP") (pinfunction "TP_TP") (pintype "passive"))
      (node (ref "U2") (pin "72") (pinfunction "(AD6)PA6_72") (pintype "passive"))
      (node (ref "U6") (pin "5") (pinfunction "EN_5") (pintype "passive"))
    )
    (net (code "117") (name "/Y-MIN") (class "Default")
      (node (ref "U2") (pin "24") (pinfunction "(OC1A/PCINT5)PB5_24") (pintype "passive"))
    )
    (net (code "118") (name "/Y-MS1") (class "Default")
      (node (ref "U2") (pin "82") (pinfunction "PK7(ADC15/PCINT23)_82") (pintype "passive"))
      (node (ref "U6") (pin "11") (pinfunction "MS1_11") (pintype "passive"))
    )
    (net (code "119") (name "/Y-MS2") (class "Default")
      (node (ref "U2") (pin "70") (pinfunction "(ALE)PG2_70") (pintype "passive"))
      (node (ref "U6") (pin "12") (pinfunction "MS2_12") (pintype "passive"))
    )
    (net (code "120") (name "/Y-REF") (class "Default")
      (node (ref "TP6") (pin "TP") (pinfunction "TP_TP") (pintype "passive"))
      (node (ref "U4") (pin "P02") (pinfunction "W6_P02") (pintype "passive"))
      (node (ref "U6") (pin "18") (pinfunction "REF_18") (pintype "passive"))
    )
    (net (code "121") (name "/Y-STEP") (class "Default")
      (node (ref "TP5") (pin "TP") (pinfunction "TP_TP") (pintype "passive"))
      (node (ref "U2") (pin "54") (pinfunction "(A9)PC1_54") (pintype "passive"))
      (node (ref "U6") (pin "17") (pinfunction "STEP_17") (pintype "passive"))
    )
    (net (code "122") (name "/Z-DIR") (class "Default")
      (node (ref "TP19") (pin "TP") (pinfunction "TP_TP") (pintype "passive"))
      (node (ref "U2") (pin "37") (pinfunction "PL2(T5)_37") (pintype "passive"))
      (node (ref "U7") (pin "20") (pinfunction "DIR_20") (pintype "passive"))
    )
    (net (code "123") (name "/Z-EN") (class "Default")
      (node (ref "R61") (pin "2") (pinfunction "2_2") (pintype "passive"))
      (node (ref "TP10") (pin "TP") (pinfunction "TP_TP") (pintype "passive"))
      (node (ref "U2") (pin "73") (pinfunction "(AD5)PA5_73") (pintype "passive"))
      (node (ref "U7") (pin "5") (pinfunction "EN_5") (pintype "passive"))
    )
    (net (code "124") (name "/Z-MIN") (class "Default")
      (node (ref "U2") (pin "23") (pinfunction "(OC2A/PCINT4)PB4_23") (pintype "passive"))
    )
    (net (code "125") (name "/Z-MS1") (class "Default")
      (node (ref "U2") (pin "83") (pinfunction "PK6(ADC14/PCINT22)_83") (pintype "passive"))
      (node (ref "U7") (pin "11") (pinfunction "MS1_11") (pintype "passive"))
    )
    (net (code "126") (name "/Z-MS2") (class "Default")
      (node (ref "U2") (pin "84") (pinfunction "PK5(ADC13/PCINT21)_84") (pintype "passive"))
      (node (ref "U7") (pin "12") (pinfunction "MS2_12") (pintype "passive"))
    )
    (net (code "127") (name "/Z-REF") (class "Default")
      (node (ref "TP9") (pin "TP") (pinfunction "TP_TP") (pintype "passive"))
      (node (ref "U4") (pin "P23") (pinfunction "W4_P23") (pintype "passive"))
      (node (ref "U7") (pin "18") (pinfunction "REF_18") (pintype "passive"))
    )
    (net (code "128") (name "/Z-STEP") (class "Default")
      (node (ref "TP8") (pin "TP") (pinfunction "TP_TP") (pintype "passive"))
      (node (ref "U2") (pin "55") (pinfunction "(A10)PC2_55") (pintype "passive"))
      (node (ref "U7") (pin "17") (pinfunction "STEP_17") (pintype "passive"))
    )
    (net (code "129") (name "GND") (class "Default")
      (node (ref "C1") (pin "2") (pinfunction "2_2") (pintype "passive"))
      (node (ref "C17") (pin "2") (pinfunction "2_2") (pintype "passive"))
      (node (ref "C18") (pin "2") (pinfunction "2_2") (pintype "passive"))
      (node (ref "C20") (pin "2") (pinfunction "2_2") (pintype "passive"))
      (node (ref "C21") (pin "1") (pinfunction "1_1") (pintype "passive"))
      (node (ref "C23") (pin "2") (pinfunction "2_2") (pintype "passive"))
      (node (ref "C24") (pin "2") (pinfunction "2_2") (pintype "passive"))
      (node (ref "C25") (pin "1") (pinfunction "1_1") (pintype "passive"))
      (node (ref "C26") (pin "2") (pinfunction "2_2") (pintype "passive"))
      (node (ref "C29") (pin "2") (pinfunction "2_2") (pintype "passive"))
      (node (ref "C3") (pin "2") (pinfunction "2_2") (pintype "passive"))
      (node (ref "C30") (pin "1") (pinfunction "1_1") (pintype "passive"))
      (node (ref "C31") (pin "1") (pinfunction "1_1") (pintype "passive"))
      (node (ref "C34") (pin "2") (pinfunction "2_2") (pintype "passive"))
      (node (ref "C36") (pin "1") (pinfunction "1_1") (pintype "passive"))
      (node (ref "C39") (pin "2") (pinfunction "2_2") (pintype "passive"))
      (node (ref "C4") (pin "2") (pinfunction "2_2") (pintype "passive"))
      (node (ref "C40") (pin "2") (pinfunction "2_2") (pintype "passive"))
      (node (ref "C41") (pin "1") (pinfunction "1_1") (pintype "passive"))
      (node (ref "C44") (pin "2") (pinfunction "2_2") (pintype "passive"))
      (node (ref "C45") (pin "1") (pinfunction "1_1") (pintype "passive"))
      (node (ref "C46") (pin "1") (pinfunction "1_1") (pintype "passive"))
      (node (ref "C49") (pin "2") (pinfunction "2_2") (pintype "passive"))
      (node (ref "C51") (pin "1") (pinfunction "1_1") (pintype "passive"))
      (node (ref "C52") (pin "2") (pinfunction "2_2") (pintype "passive"))
      (node (ref "C53") (pin "2") (pinfunction "2_2") (pintype "passive"))
      (node (ref "C55") (pin "2") (pinfunction "2_2") (pintype "passive"))
      (node (ref "C56") (pin "2") (pinfunction "2_2") (pintype "passive"))
      (node (ref "C57") (pin "2") (pinfunction "2_2") (pintype "passive"))
      (node (ref "C58") (pin "2") (pinfunction "2_2") (pintype "passive"))
      (node (ref "C59") (pin "2") (pinfunction "2_2") (pintype "passive"))
      (node (ref "C6") (pin "2") (pinfunction "2_2") (pintype "passive"))
      (node (ref "C64") (pin "2") (pinfunction "2_2") (pintype "passive"))
      (node (ref "C7") (pin "2") (pinfunction "2_2") (pintype "passive"))
      (node (ref "C71") (pin "2") (pinfunction "2_2") (pintype "passive"))
      (node (ref "C72") (pin "2") (pinfunction "2_2") (pintype "passive"))
      (node (ref "C73") (pin "2") (pinfunction "2_2") (pintype "passive"))
      (node (ref "C74") (pin "2") (pinfunction "2_2") (pintype "passive"))
      (node (ref "C75") (pin "2") (pinfunction "2_2") (pintype "passive"))
      (node (ref "C76") (pin "-") (pinfunction "-_-") (pintype "passive"))
      (node (ref "C8") (pin "2") (pinfunction "2_2") (pintype "passive"))
      (node (ref "C9") (pin "2") (pinfunction "2_2") (pintype "passive"))
      (node (ref "C96") (pin "1") (pinfunction "1_1") (pintype "passive"))
      (node (ref "CF1") (pin "2@1") (pinfunction "2_2@1") (pintype "passive"))
      (node (ref "CF1") (pin "2@2") (pinfunction "2_2@2") (pintype "passive"))
      (node (ref "CF10") (pin "2@1") (pinfunction "2_2@1") (pintype "passive"))
      (node (ref "CF10") (pin "2@2") (pinfunction "2_2@2") (pintype "passive"))
      (node (ref "CF11") (pin "2@1") (pinfunction "2_2@1") (pintype "passive"))
      (node (ref "CF11") (pin "2@2") (pinfunction "2_2@2") (pintype "passive"))
      (node (ref "CF12") (pin "2@1") (pinfunction "2_2@1") (pintype "passive"))
      (node (ref "CF12") (pin "2@2") (pinfunction "2_2@2") (pintype "passive"))
      (node (ref "CF13") (pin "2@1") (pinfunction "2_2@1") (pintype "passive"))
      (node (ref "CF13") (pin "2@2") (pinfunction "2_2@2") (pintype "passive"))
      (node (ref "CF14") (pin "2@1") (pinfunction "2_2@1") (pintype "passive"))
      (node (ref "CF14") (pin "2@2") (pinfunction "2_2@2") (pintype "passive"))
      (node (ref "CF15") (pin "2@1") (pinfunction "2_2@1") (pintype "passive"))
      (node (ref "CF15") (pin "2@2") (pinfunction "2_2@2") (pintype "passive"))
      (node (ref "CF16") (pin "2@1") (pinfunction "2_2@1") (pintype "passive"))
      (node (ref "CF16") (pin "2@2") (pinfunction "2_2@2") (pintype "passive"))
      (node (ref "CF17") (pin "2@1") (pinfunction "2_2@1") (pintype "passive"))
      (node (ref "CF17") (pin "2@2") (pinfunction "2_2@2") (pintype "passive"))
      (node (ref "CF18") (pin "2@1") (pinfunction "2_2@1") (pintype "passive"))
      (node (ref "CF18") (pin "2@2") (pinfunction "2_2@2") (pintype "passive"))
      (node (ref "CF19") (pin "2@1") (pinfunction "2_2@1") (pintype "passive"))
      (node (ref "CF19") (pin "2@2") (pinfunction "2_2@2") (pintype "passive"))
      (node (ref "CF2") (pin "2@1") (pinfunction "2_2@1") (pintype "passive"))
      (node (ref "CF2") (pin "2@2") (pinfunction "2_2@2") (pintype "passive"))
      (node (ref "CF20") (pin "2@1") (pinfunction "2_2@1") (pintype "passive"))
      (node (ref "CF20") (pin "2@2") (pinfunction "2_2@2") (pintype "passive"))
      (node (ref "CF3") (pin "2@1") (pinfunction "2_2@1") (pintype "passive"))
      (node (ref "CF3") (pin "2@2") (pinfunction "2_2@2") (pintype "passive"))
      (node (ref "CF4") (pin "2@1") (pinfunction "2_2@1") (pintype "passive"))
      (node (ref "CF4") (pin "2@2") (pinfunction "2_2@2") (pintype "passive"))
      (node (ref "CF5") (pin "2@1") (pinfunction "2_2@1") (pintype "passive"))
      (node (ref "CF5") (pin "2@2") (pinfunction "2_2@2") (pintype "passive"))
      (node (ref "CF6") (pin "2@1") (pinfunction "2_2@1") (pintype "passive"))
      (node (ref "CF6") (pin "2@2") (pinfunction "2_2@2") (pintype "passive"))
      (node (ref "CF7") (pin "2@1") (pinfunction "2_2@1") (pintype "passive"))
      (node (ref "CF7") (pin "2@2") (pinfunction "2_2@2") (pintype "passive"))
      (node (ref "CF8") (pin "2@1") (pinfunction "2_2@1") (pintype "passive"))
      (node (ref "CF8") (pin "2@2") (pinfunction "2_2@2") (pintype "passive"))
      (node (ref "CF9") (pin "2@1") (pinfunction "2_2@1") (pintype "passive"))
      (node (ref "CF9") (pin "2@2") (pinfunction "2_2@2") (pintype "passive"))
      (node (ref "D12") (pin "A") (pinfunction "A_A") (pintype "passive"))
      (node (ref "D14") (pin "A") (pinfunction "A_A") (pintype "passive"))
      (node (ref "D16") (pin "A") (pinfunction "A_A") (pintype "passive"))
      (node (ref "D18") (pin "A") (pinfunction "A_A") (pintype "passive"))
      (node (ref "D20") (pin "A") (pinfunction "A_A") (pintype "passive"))
      (node (ref "D21") (pin "A") (pinfunction "A_A") (pintype "passive"))
      (node (ref "D22") (pin "A") (pinfunction "A_A") (pintype "passive"))
      (node (ref "D23") (pin "A") (pinfunction "A_A") (pintype "passive"))
      (node (ref "D24") (pin "A") (pinfunction "A_A") (pintype "passive"))
      (node (ref "D25") (pin "A") (pinfunction "A_A") (pintype "passive"))
      (node (ref "D26") (pin "A") (pinfunction "A_A") (pintype "passive"))
      (node (ref "D27") (pin "A") (pinfunction "A_A") (pintype "passive"))
      (node (ref "D28") (pin "A") (pinfunction "A_A") (pintype "passive"))
      (node (ref "D29") (pin "A") (pinfunction "A_A") (pintype "passive"))
      (node (ref "D30") (pin "A") (pinfunction "A_A") (pintype "passive"))
      (node (ref "D31") (pin "A") (pinfunction "A_A") (pintype "passive"))
      (node (ref "D32") (pin "A") (pinfunction "A_A") (pintype "passive"))
      (node (ref "D33") (pin "A") (pinfunction "A_A") (pintype "passive"))
      (node (ref "D34") (pin "A") (pinfunction "A_A") (pintype "passive"))
      (node (ref "D35") (pin "A") (pinfunction "A_A") (pintype "passive"))
      (node (ref "D36") (pin "A") (pinfunction "A_A") (pintype "passive"))
      (node (ref "D37") (pin "A") (pinfunction "A_A") (pintype "passive"))
      (node (ref "D38") (pin "A") (pinfunction "A_A") (pintype "passive"))
      (node (ref "D39") (pin "A") (pinfunction "A_A") (pintype "passive"))
      (node (ref "D40") (pin "C") (pinfunction "2_C") (pintype "passive"))
      (node (ref "D9") (pin "A") (pinfunction "A_A") (pintype "passive"))
      (node (ref "JP3") (pin "1") (pinfunction "1_1") (pintype "passive"))
      (node (ref "LED1") (pin "C") (pinfunction "C_C") (pintype "passive"))
      (node (ref "LED7") (pin "C") (pinfunction "C_C") (pintype "passive"))
      (node (ref "Q1") (pin "1") (pinfunction "S_1") (pintype "passive"))
      (node (ref "Q1") (pin "2") (pinfunction "S_2") (pintype "passive"))
      (node (ref "Q1") (pin "3") (pinfunction "S_3") (pintype "passive"))
      (node (ref "Q2") (pin "1") (pinfunction "S_1") (pintype "passive"))
      (node (ref "Q2") (pin "2") (pinfunction "S_2") (pintype "passive"))
      (node (ref "Q2") (pin "3") (pinfunction "S_3") (pintype "passive"))
      (node (ref "Q3") (pin "1") (pinfunction "S_1") (pintype "passive"))
      (node (ref "Q3") (pin "2") (pinfunction "S_2") (pintype "passive"))
      (node (ref "Q3") (pin "3") (pinfunction "S_3") (pintype "passive"))
      (node (ref "Q4") (pin "1") (pinfunction "S_1") (pintype "passive"))
      (node (ref "Q4") (pin "3") (pinfunction "S_3") (pintype "passive"))
      (node (ref "Q5") (pin "1") (pinfunction "S_1") (pintype "passive"))
      (node (ref "Q5") (pin "2") (pinfunction "S_2") (pintype "passive"))
      (node (ref "Q5") (pin "3") (pinfunction "S_3") (pintype "passive"))
      (node (ref "R10") (pin "2") (pinfunction "2_2") (pintype "passive"))
      (node (ref "R11") (pin "2") (pinfunction "2_2") (pintype "passive"))
      (node (ref "R12") (pin "1") (pinfunction "1_1") (pintype "passive"))
      (node (ref "R14") (pin "2") (pinfunction "2_2") (pintype "passive"))
      (node (ref "R15") (pin "2") (pinfunction "2_2") (pintype "passive"))
      (node (ref "R17") (pin "1") (pinfunction "1_1") (pintype "passive"))
      (node (ref "R18") (pin "1") (pinfunction "1_1") (pintype "passive"))
      (node (ref "R19") (pin "2") (pinfunction "2_2") (pintype "passive"))
      (node (ref "R20") (pin "2") (pinfunction "2_2") (pintype "passive"))
      (node (ref "R22") (pin "1") (pinfunction "1_1") (pintype "passive"))
      (node (ref "R23") (pin "2") (pinfunction "2_2") (pintype "passive"))
      (node (ref "R24") (pin "2") (pinfunction "2_2") (pintype "passive"))
      (node (ref "R26") (pin "1") (pinfunction "1_1") (pintype "passive"))
      (node (ref "R4") (pin "2") (pinfunction "2_2") (pintype "passive"))
      (node (ref "R43") (pin "2") (pinfunction "2_2") (pintype "passive"))
      (node (ref "R49") (pin "2") (pinfunction "2_2") (pintype "passive"))
      (node (ref "R52") (pin "2") (pinfunction "2_2") (pintype "passive"))
      (node (ref "R54") (pin "2") (pinfunction "2_2") (pintype "passive"))
      (node (ref "R57") (pin "2") (pinfunction "2_2") (pintype "passive"))
      (node (ref "R7") (pin "2") (pinfunction "2_2") (pintype "passive"))
      (node (ref "R71") (pin "2") (pinfunction "2_2") (pintype "passive"))
      (node (ref "R8") (pin "2") (pinfunction "2_2") (pintype "passive"))
      (node (ref "S1") (pin "2") (pinfunction "S_2") (pintype "passive"))
      (node (ref "U10") (pin "15") (pinfunction "GND2A_15") (pintype "passive"))
      (node (ref "U10") (pin "9") (pinfunction "GND2B_9") (pintype "passive"))
      (node (ref "U2") (pin "11") (pinfunction "GND_11") (pintype "power_in"))
      (node (ref "U2") (pin "32") (pinfunction "GND1_32") (pintype "power_in"))
      (node (ref "U2") (pin "62") (pinfunction "GND2_62") (pintype "power_in"))
      (node (ref "U2") (pin "81") (pinfunction "GND3_81") (pintype "power_in"))
      (node (ref "U2") (pin "99") (pinfunction "AGND_99") (pintype "power_in"))
      (node (ref "U3") (pin "6") (pinfunction "GND_6") (pintype "passive"))
      (node (ref "U3") (pin "9") (pinfunction "PAD_9") (pintype "passive"))
      (node (ref "U4") (pin "P03") (pinfunction "B6_P03") (pintype "passive"))
      (node (ref "U4") (pin "P04") (pinfunction "GND_P04") (pintype "passive"))
      (node (ref "U4") (pin "P09") (pinfunction "VSS_P09") (pintype "passive"))
      (node (ref "U4") (pin "P10") (pinfunction "B5_P10") (pintype "passive"))
      (node (ref "U4") (pin "P13") (pinfunction "B3_P13") (pintype "passive"))
      (node (ref "U4") (pin "P16") (pinfunction "B1_P16") (pintype "passive"))
      (node (ref "U4") (pin "P21") (pinfunction "B2_P21") (pintype "passive"))
      (node (ref "U4") (pin "P24") (pinfunction "B4_P24") (pintype "passive"))
      (node (ref "U5") (pin "19") (pinfunction "GND2_19") (pintype "power_in"))
      (node (ref "U5") (pin "33") (pinfunction "TH-PAD_33") (pintype "power_in"))
      (node (ref "U5") (pin "6") (pinfunction "GND1_6") (pintype "power_in"))
      (node (ref "U6") (pin "19") (pinfunction "GND2_19") (pintype "power_in"))
      (node (ref "U6") (pin "33") (pinfunction "TH-PAD_33") (pintype "power_in"))
      (node (ref "U6") (pin "6") (pinfunction "GND1_6") (pintype "power_in"))
      (node (ref "U7") (pin "19") (pinfunction "GND2_19") (pintype "power_in"))
      (node (ref "U7") (pin "33") (pinfunction "TH-PAD_33") (pintype "power_in"))
      (node (ref "U7") (pin "6") (pinfunction "GND1_6") (pintype "power_in"))
      (node (ref "U8") (pin "19") (pinfunction "GND2_19") (pintype "power_in"))
      (node (ref "U8") (pin "33") (pinfunction "TH-PAD_33") (pintype "power_in"))
      (node (ref "U8") (pin "6") (pinfunction "GND1_6") (pintype "power_in"))
      (node (ref "U9") (pin "19") (pinfunction "GND2_19") (pintype "power_in"))
      (node (ref "U9") (pin "33") (pinfunction "TH-PAD_33") (pintype "power_in"))
      (node (ref "U9") (pin "6") (pinfunction "GND1_6") (pintype "power_in"))
      (node (ref "X27") (pin "1") (pinfunction "S_1") (pintype "passive"))
      (node (ref "X28") (pin "1") (pinfunction "S_1") (pintype "passive"))
      (node (ref "X29") (pin "1") (pinfunction "S_1") (pintype "passive"))
      (node (ref "X3") (pin "1") (pinfunction "S_1") (pintype "passive"))
      (node (ref "X40") (pin "2") (pinfunction "2_2") (pintype "passive"))
      (node (ref "Y1") (pin "2") (pinfunction "GND_2") (pintype "passive"))
      (node (ref "Y1") (pin "4") (pinfunction "GND_4") (pintype "passive"))
    )
    (net (code "130") (name "GND1") (class "Default")
      (node (ref "C11") (pin "2") (pinfunction "2_2") (pintype "passive"))
      (node (ref "C12") (pin "2") (pinfunction "2_2") (pintype "passive"))
      (node (ref "C13") (pin "2") (pinfunction "2_2") (pintype "passive"))
      (node (ref "C14") (pin "2") (pinfunction "2_2") (pintype "passive"))
      (node (ref "C15") (pin "2") (pinfunction "2_2") (pintype "passive"))
      (node (ref "C16") (pin "2") (pinfunction "2_2") (pintype "passive"))
      (node (ref "C19") (pin "2") (pinfunction "2_2") (pintype "passive"))
      (node (ref "C2") (pin "1") (pinfunction "1_1") (pintype "passive"))
      (node (ref "C5") (pin "2") (pinfunction "2_2") (pintype "passive"))
      (node (ref "C63") (pin "2") (pinfunction "2_2") (pintype "passive"))
      (node (ref "D40") (pin "A") (pinfunction "1_A") (pintype "passive"))
      (node (ref "R72") (pin "1") (pinfunction "1_1") (pintype "passive"))
      (node (ref "RN5") (pin "8") (pinfunction "2_8") (pintype "passive"))
      (node (ref "U1") (pin "28") (pinfunction "UGND_28") (pintype "power_in"))
      (node (ref "U1") (pin "3") (pinfunction "GND_3") (pintype "power_in"))
      (node (ref "U1") (pin "33") (pinfunction "PAD_33") (pintype "power_in"))
      (node (ref "U10") (pin "2") (pinfunction "GND1A_2") (pintype "passive"))
      (node (ref "U10") (pin "4") (pinfunction "VIB_4") (pintype "passive"))
      (node (ref "U10") (pin "8") (pinfunction "GND1B_8") (pintype "passive"))
      (node (ref "X16") (pin "3") (pinfunction "3_3") (pintype "passive"))
      (node (ref "X16") (pin "4") (pinfunction "4_4") (pintype "passive"))
      (node (ref "X17") (pin "6") (pinfunction "6_6") (pintype "passive"))
      (node (ref "X2") (pin "4") (pinfunction "4_4") (pintype "passive"))
      (node (ref "Y2") (pin "2") (pinfunction "GND_2") (pintype "passive"))
      (node (ref "Y2") (pin "4") (pinfunction "GND_4") (pintype "passive"))
      (node (ref "Z3") (pin "2") (pinfunction "2_2") (pintype "passive"))
    )
    (net (code "131") (name "Net-(CF1-Pad3)") (class "Default")
      (node (ref "CF1") (pin "3") (pinfunction "3_3") (pintype "passive"))
      (node (ref "X8") (pin "1") (pinfunction "1_1") (pintype "passive"))
    )
    (net (code "132") (name "Net-(CF5-Pad3)") (class "Default")
      (node (ref "CF5") (pin "3") (pinfunction "3_3") (pintype "passive"))
      (node (ref "X4") (pin "1") (pinfunction "1_1") (pintype "passive"))
    )
    (net (code "133") (name "Net-(CF9-Pad3)") (class "Default")
      (node (ref "CF9") (pin "3") (pinfunction "3_3") (pintype "passive"))
      (node (ref "X14") (pin "1") (pinfunction "1_1") (pintype "passive"))
      (node (ref "X15") (pin "1") (pinfunction "1_1") (pintype "passive"))
    )
    (net (code "134") (name "Net-(CF13-Pad3)") (class "Default")
      (node (ref "CF13") (pin "3") (pinfunction "3_3") (pintype "passive"))
      (node (ref "X6") (pin "1") (pinfunction "1_1") (pintype "passive"))
    )
    (net (code "135") (name "Net-(CF17-Pad3)") (class "Default")
      (node (ref "CF17") (pin "3") (pinfunction "3_3") (pintype "passive"))
      (node (ref "X7") (pin "1") (pinfunction "1_1") (pintype "passive"))
    )
    (net (code "136") (name "Net-(D11-PadA)") (class "Default")
      (node (ref "D11") (pin "A") (pinfunction "A_A") (pintype "passive"))
      (node (ref "D12") (pin "K") (pinfunction "K_K") (pintype "passive"))
      (node (ref "R27") (pin "1") (pinfunction "1_1") (pintype "passive"))
      (node (ref "R28") (pin "2") (pinfunction "2_2") (pintype "passive"))
    )
    (net (code "137") (name "Net-(D13-PadA)") (class "Default")
      (node (ref "D13") (pin "A") (pinfunction "A_A") (pintype "passive"))
      (node (ref "D14") (pin "K") (pinfunction "K_K") (pintype "passive"))
      (node (ref "R32") (pin "1") (pinfunction "1_1") (pintype "passive"))
      (node (ref "R36") (pin "2") (pinfunction "2_2") (pintype "passive"))
    )
    (net (code "138") (name "Net-(D15-PadA)") (class "Default")
      (node (ref "D15") (pin "A") (pinfunction "A_A") (pintype "passive"))
      (node (ref "D16") (pin "K") (pinfunction "K_K") (pintype "passive"))
      (node (ref "R38") (pin "1") (pinfunction "1_1") (pintype "passive"))
      (node (ref "R39") (pin "2") (pinfunction "2_2") (pintype "passive"))
    )
    (net (code "139") (name "Net-(D17-PadA)") (class "Default")
      (node (ref "D17") (pin "A") (pinfunction "A_A") (pintype "passive"))
      (node (ref "D18") (pin "K") (pinfunction "K_K") (pintype "passive"))
      (node (ref "R77") (pin "1") (pinfunction "1_1") (pintype "passive"))
      (node (ref "R78") (pin "2") (pinfunction "2_2") (pintype "passive"))
    )
    (net (code "140") (name "Net-(LED1-PadA)") (class "Default")
      (node (ref "LED1") (pin "A") (pinfunction "A_A") (pintype "passive"))
      (node (ref "R33") (pin "2") (pinfunction "2_2") (pintype "passive"))
    )
    (net (code "141") (name "Net-(LED2-PadA)") (class "Default")
      (node (ref "LED2") (pin "A") (pinfunction "A_A") (pintype "passive"))
      (node (ref "R40") (pin "1") (pinfunction "1_1") (pintype "passive"))
    )
    (net (code "142") (name "Net-(LED3-PadA)") (class "Default")
      (node (ref "LED3") (pin "A") (pinfunction "A_A") (pintype "passive"))
      (node (ref "R50") (pin "1") (pinfunction "1_1") (pintype "passive"))
    )
    (net (code "143") (name "Net-(LED4-PadA)") (class "Default")
      (node (ref "LED4") (pin "A") (pinfunction "A_A") (pintype "passive"))
      (node (ref "R41") (pin "1") (pinfunction "1_1") (pintype "passive"))
    )
    (net (code "144") (name "Net-(LED5-PadA)") (class "Default")
      (node (ref "LED5") (pin "A") (pinfunction "A_A") (pintype "passive"))
      (node (ref "R55") (pin "1") (pinfunction "1_1") (pintype "passive"))
    )
    (net (code "145") (name "Net-(LED6-PadA)") (class "Default")
      (node (ref "LED6") (pin "A") (pinfunction "A_A") (pintype "passive"))
      (node (ref "R58") (pin "1") (pinfunction "1_1") (pintype "passive"))
    )
    (net (code "146") (name "Net-(LED7-PadA)") (class "Default")
      (node (ref "LED7") (pin "A") (pinfunction "A_A") (pintype "passive"))
      (node (ref "R35") (pin "2") (pinfunction "2_2") (pintype "passive"))
    )
    (net (code "147") (name "Net-(LED8-PadA)") (class "Default")
      (node (ref "LED8") (pin "A") (pinfunction "A_A") (pintype "passive"))
      (node (ref "R69") (pin "1") (pinfunction "1_1") (pintype "passive"))
    )
    (net (code "148") (name "Net-(Q1-D)") (class "Default")
      (node (ref "D6") (pin "A") (pinfunction "A_A") (pintype "passive"))
      (node (ref "LED2") (pin "C") (pinfunction "C_C") (pintype "passive"))
      (node (ref "Q1") (pin "MB") (pinfunction "D_MB") (pintype "passive"))
      (node (ref "X11") (pin "1") (pinfunction "1_1") (pintype "passive"))
      (node (ref "X35") (pin "1") (pinfunction "1_1") (pintype "passive"))
    )
    (net (code "149") (name "Net-(Q1-G)") (class "Default")
      (node (ref "Q1") (pin "4") (pinfunction "G_4") (pintype "passive"))
      (node (ref "R42") (pin "2") (pinfunction "2_2") (pintype "passive"))
    )
    (net (code "150") (name "Net-(Q2-D)") (class "Default")
      (node (ref "D3") (pin "A") (pinfunction "A_A") (pintype "passive"))
      (node (ref "LED3") (pin "C") (pinfunction "C_C") (pintype "passive"))
      (node (ref "Q2") (pin "MB") (pinfunction "D_MB") (pintype "passive"))
      (node (ref "X11") (pin "3") (pinfunction "1_3") (pintype "passive"))
      (node (ref "X36") (pin "1") (pinfunction "1_1") (pintype "passive"))
    )
    (net (code "151") (name "Net-(Q2-G)") (class "Default")
      (node (ref "Q2") (pin "4") (pinfunction "G_4") (pintype "passive"))
      (node (ref "R48") (pin "2") (pinfunction "2_2") (pintype "passive"))
    )
    (net (code "152") (name "Net-(Q3-D)") (class "Default")
      (node (ref "D1") (pin "A") (pinfunction "A_A") (pintype "passive"))
      (node (ref "LED4") (pin "C") (pinfunction "C_C") (pintype "passive"))
      (node (ref "Q3") (pin "MB") (pinfunction "D_MB") (pintype "passive"))
      (node (ref "X11") (pin "5") (pinfunction "1_5") (pintype "passive"))
      (node (ref "X37") (pin "1") (pinfunction "1_1") (pintype "passive"))
    )
    (net (code "153") (name "Net-(Q3-G)") (class "Default")
      (node (ref "Q3") (pin "4") (pinfunction "G_4") (pintype "passive"))
      (node (ref "R51") (pin "2") (pinfunction "2_2") (pintype "passive"))
    )
    (net (code "154") (name "Net-(Q4A-D)") (class "Default")
      (node (ref "LED5") (pin "C") (pinfunction "C_C") (pintype "passive"))
      (node (ref "Q4") (pin "7") (pinfunction "D_7") (pintype "passive"))
      (node (ref "X11") (pin "7") (pinfunction "1_7") (pintype "passive"))
    )
    (net (code "155") (name "Net-(Q4A-G)") (class "Default")
      (node (ref "Q4") (pin "2") (pinfunction "G_2") (pintype "passive"))
      (node (ref "R53") (pin "2") (pinfunction "2_2") (pintype "passive"))
    )
    (net (code "156") (name "Net-(Q4B-D)") (class "Default")
      (node (ref "LED8") (pin "C") (pinfunction "C_C") (pintype "passive"))
      (node (ref "Q4") (pin "5") (pinfunction "D_5") (pintype "passive"))
      (node (ref "X9") (pin "1") (pinfunction "S_1") (pintype "passive"))
    )
    (net (code "157") (name "Net-(Q4B-G)") (class "Default")
      (node (ref "Q4") (pin "4") (pinfunction "G_4") (pintype "passive"))
      (node (ref "R70") (pin "2") (pinfunction "2_2") (pintype "passive"))
    )
    (net (code "158") (name "Net-(Q5-D)") (class "Default")
      (node (ref "D10") (pin "A") (pinfunction "A_A") (pintype "passive"))
      (node (ref "LED6") (pin "C") (pinfunction "C_C") (pintype "passive"))
      (node (ref "Q5") (pin "MB") (pinfunction "D_MB") (pintype "passive"))
      (node (ref "X11") (pin "9") (pinfunction "1_9") (pintype "passive"))
      (node (ref "X38") (pin "1") (pinfunction "1_1") (pintype "passive"))
    )
    (net (code "159") (name "Net-(Q5-G)") (class "Default")
      (node (ref "Q5") (pin "4") (pinfunction "G_4") (pintype "passive"))
      (node (ref "R56") (pin "2") (pinfunction "2_2") (pintype "passive"))
    )
    (net (code "160") (name "Net-(RN5B-2)") (class "Default")
      (node (ref "LED10") (pin "A") (pinfunction "A_A") (pintype "passive"))
      (node (ref "RN5") (pin "7") (pinfunction "2_7") (pintype "passive"))
    )
    (net (code "161") (name "Net-(RN5C-2)") (class "Default")
      (node (ref "LED9") (pin "A") (pinfunction "A_A") (pintype "passive"))
      (node (ref "RN5") (pin "6") (pinfunction "2_6") (pintype "passive"))
    )
    (net (code "162") (name "Net-(U2-(MISO{slash}PCINT3)PB3)") (class "Default")
      (node (ref "R64") (pin "1") (pinfunction "1_1") (pintype "passive"))
      (node (ref "U2") (pin "22") (pinfunction "(MISO/PCINT3)PB3_22") (pintype "passive"))
    )
    (net (code "163") (name "Net-(U2-(MOSI{slash}PCINT2)PB2)") (class "Default")
      (node (ref "R74") (pin "1") (pinfunction "1_1") (pintype "passive"))
      (node (ref "U2") (pin "21") (pinfunction "(MOSI/PCINT2)PB2_21") (pintype "passive"))
    )
    (net (code "164") (name "Net-(U2-(SCK{slash}PCINT1)PB1)") (class "Default")
      (node (ref "R75") (pin "1") (pinfunction "1_1") (pintype "passive"))
      (node (ref "U2") (pin "20") (pinfunction "(SCK/PCINT1)PB1_20") (pintype "passive"))
    )
    (net (code "165") (name "Net-(U2-(SS{slash}PCINT0)PB0)") (class "Default")
      (node (ref "R76") (pin "1") (pinfunction "1_1") (pintype "passive"))
      (node (ref "U2") (pin "19") (pinfunction "(SS/PCINT0)PB0_19") (pintype "passive"))
    )
    (net (code "166") (name "Net-(U2-AVCC)") (class "Default")
      (node (ref "C26") (pin "1") (pinfunction "1_1") (pintype "passive"))
      (node (ref "L2") (pin "2") (pinfunction "2_2") (pintype "passive"))
      (node (ref "U2") (pin "100") (pinfunction "AVCC_100") (pintype "power_in"))
    )
    (net (code "167") (name "Net-(U3-BOOT)") (class "Default")
      (node (ref "C35") (pin "1") (pinfunction "1_1") (pintype "passive"))
      (node (ref "U3") (pin "1") (pinfunction "BOOT_1") (pintype "passive"))
    )
    (net (code "168") (name "Net-(U3-ENABLE)") (class "Default")
      (node (ref "JP3") (pin "2") (pinfunction "2_2") (pintype "passive"))
      (node (ref "R3") (pin "1") (pinfunction "1_1") (pintype "passive"))
      (node (ref "U3") (pin "5") (pinfunction "ENABLE_5") (pintype "passive"))
    )
    (net (code "169") (name "Net-(U3-SWITCH)") (class "Default")
      (node (ref "C35") (pin "2") (pinfunction "2_2") (pintype "passive"))
      (node (ref "D20") (pin "C") (pinfunction "C_C") (pintype "passive"))
      (node (ref "L3") (pin "1") (pinfunction "1_1") (pintype "passive"))
      (node (ref "U3") (pin "8") (pinfunction "SWITCH_8") (pintype "passive"))
    )
    (net (code "170") (name "Net-(U4-A1)") (class "Default")
      (node (ref "R30") (pin "2") (pinfunction "2_2") (pintype "passive"))
      (node (ref "U4") (pin "P01") (pinfunction "A6_P01") (pintype "passive"))
      (node (ref "U4") (pin "P12") (pinfunction "A5_P12") (pintype "passive"))
      (node (ref "U4") (pin "P15") (pinfunction "A3_P15") (pintype "passive"))
      (node (ref "U4") (pin "P18") (pinfunction "A1_P18") (pintype "passive"))
      (node (ref "U4") (pin "P19") (pinfunction "A2_P19") (pintype "passive"))
      (node (ref "U4") (pin "P22") (pinfunction "A4_P22") (pintype "passive"))
    )
    (net (code "171") (name "Net-(U5-CP1)") (class "Default")
      (node (ref "C28") (pin "1") (pinfunction "1_1") (pintype "passive"))
      (node (ref "U5") (pin "7") (pinfunction "CP1_7") (pintype "passive"))
    )
    (net (code "172") (name "Net-(U5-CP2)") (class "Default")
      (node (ref "C28") (pin "2") (pinfunction "2_2") (pintype "passive"))
      (node (ref "U5") (pin "8") (pinfunction "CP2_8") (pintype "passive"))
    )
    (net (code "173") (name "Net-(U5-OUT1A)") (class "Default")
      (node (ref "CF3") (pin "1") (pinfunction "1_1") (pintype "passive"))
      (node (ref "D9") (pin "K") (pinfunction "K_K") (pintype "passive"))
      (node (ref "U5") (pin "27") (pinfunction "OUT1A_27") (pintype "output"))
    )
    (net (code "174") (name "Net-(U5-OUT1B)") (class "Default")
      (node (ref "CF4") (pin "1") (pinfunction "1_1") (pintype "passive"))
      (node (ref "D21") (pin "K") (pinfunction "K_K") (pintype "passive"))
      (node (ref "U5") (pin "24") (pinfunction "OUT1B_24") (pintype "output"))
    )
    (net (code "175") (name "Net-(U5-OUT2A)") (class "Default")
      (node (ref "CF2") (pin "1") (pinfunction "1_1") (pintype "passive"))
      (node (ref "D23") (pin "K") (pinfunction "K_K") (pintype "passive"))
      (node (ref "U5") (pin "30") (pinfunction "OUT2A_30") (pintype "output"))
    )
    (net (code "176") (name "Net-(U5-OUT2B)") (class "Default")
      (node (ref "CF1") (pin "1") (pinfunction "1_1") (pintype "passive"))
      (node (ref "D22") (pin "K") (pinfunction "K_K") (pintype "passive"))
      (node (ref "U5") (pin "1") (pinfunction "OUT2B_1") (pintype "output"))
    )
    (net (code "177") (name "Net-(U5-RESET)") (class "Default")
      (node (ref "C24") (pin "1") (pinfunction "1_1") (pintype "passive"))
      (node (ref "R29") (pin "1") (pinfunction "1_1") (pintype "passive"))
      (node (ref "U5") (pin "13") (pinfunction "RESET_13") (pintype "passive"))
      (node (ref "U5") (pin "15") (pinfunction "SLEEP_15") (pintype "passive"))
      (node (ref "U5") (pin "16") (pinfunction "VDD_16") (pintype "power_in"))
    )
    (net (code "178") (name "Net-(U5-ROSC)") (class "Default")
      (node (ref "R18") (pin "2") (pinfunction "2_2") (pintype "passive"))
      (node (ref "U5") (pin "14") (pinfunction "ROSC_14") (pintype "passive"))
    )
    (net (code "179") (name "Net-(U5-SENSE1)") (class "Default")
      (node (ref "R7") (pin "1") (pinfunction "1_1") (pintype "passive"))
      (node (ref "U5") (pin "25") (pinfunction "SENSE1_25") (pintype "passive"))
    )
    (net (code "180") (name "Net-(U5-SENSE2)") (class "Default")
      (node (ref "R4") (pin "1") (pinfunction "1_1") (pintype "passive"))
      (node (ref "U5") (pin "32") (pinfunction "SENSE2_32") (pintype "passive"))
    )
    (net (code "181") (name "Net-(U5-VCP)") (class "Default")
      (node (ref "C27") (pin "2") (pinfunction "2_2") (pintype "passive"))
      (node (ref "U5") (pin "9") (pinfunction "VCP_9") (pintype "passive"))
    )
    (net (code "182") (name "Net-(U5-VREG)") (class "Default")
      (node (ref "C31") (pin "2") (pinfunction "2_2") (pintype "passive"))
      (node (ref "U5") (pin "10") (pinfunction "VREG_10") (pintype "passive"))
    )
    (net (code "183") (name "Net-(U6-CP1)") (class "Default")
      (node (ref "C33") (pin "1") (pinfunction "1_1") (pintype "passive"))
      (node (ref "U6") (pin "7") (pinfunction "CP1_7") (pintype "passive"))
    )
    (net (code "184") (name "Net-(U6-CP2)") (class "Default")
      (node (ref "C33") (pin "2") (pinfunction "2_2") (pintype "passive"))
      (node (ref "U6") (pin "8") (pinfunction "CP2_8") (pintype "passive"))
    )
    (net (code "185") (name "Net-(U6-OUT1A)") (class "Default")
      (node (ref "CF7") (pin "1") (pinfunction "1_1") (pintype "passive"))
      (node (ref "D25") (pin "K") (pinfunction "K_K") (pintype "passive"))
      (node (ref "U6") (pin "27") (pinfunction "OUT1A_27") (pintype "output"))
    )
    (net (code "186") (name "Net-(U6-OUT1B)") (class "Default")
      (node (ref "CF8") (pin "1") (pinfunction "1_1") (pintype "passive"))
      (node (ref "D24") (pin "K") (pinfunction "K_K") (pintype "passive"))
      (node (ref "U6") (pin "24") (pinfunction "OUT1B_24") (pintype "output"))
    )
    (net (code "187") (name "Net-(U6-OUT2A)") (class "Default")
      (node (ref "CF6") (pin "1") (pinfunction "1_1") (pintype "passive"))
      (node (ref "D27") (pin "K") (pinfunction "K_K") (pintype "passive"))
      (node (ref "U6") (pin "30") (pinfunction "OUT2A_30") (pintype "output"))
    )
    (net (code "188") (name "Net-(U6-OUT2B)") (class "Default")
      (node (ref "CF5") (pin "1") (pinfunction "1_1") (pintype "passive"))
      (node (ref "D26") (pin "K") (pinfunction "K_K") (pintype "passive"))
      (node (ref "U6") (pin "1") (pinfunction "OUT2B_1") (pintype "output"))
    )
    (net (code "189") (name "Net-(U6-RESET)") (class "Default")
      (node (ref "C23") (pin "1") (pinfunction "1_1") (pintype "passive"))
      (node (ref "R65") (pin "1") (pinfunction "1_1") (pintype "passive"))
      (node (ref "U6") (pin "13") (pinfunction "RESET_13") (pintype "passive"))
      (node (ref "U6") (pin "15") (pinfunction "SLEEP_15") (pintype "passive"))
      (node (ref "U6") (pin "16") (pinfunction "VDD_16") (pintype "power_in"))
    )
    (net (code "190") (name "Net-(U6-ROSC)") (class "Default")
      (node (ref "R12") (pin "2") (pinfunction "2_2") (pintype "passive"))
      (node (ref "U6") (pin "14") (pinfunction "ROSC_14") (pintype "passive"))
    )
    (net (code "191") (name "Net-(U6-SENSE1)") (class "Default")
      (node (ref "R10") (pin "1") (pinfunction "1_1") (pintype "passive"))
      (node (ref "U6") (pin "25") (pinfunction "SENSE1_25") (pintype "passive"))
    )
    (net (code "192") (name "Net-(U6-SENSE2)") (class "Default")
      (node (ref "R8") (pin "1") (pinfunction "1_1") (pintype "passive"))
      (node (ref "U6") (pin "32") (pinfunction "SENSE2_32") (pintype "passive"))
    )
    (net (code "193") (name "Net-(U6-VCP)") (class "Default")
      (node (ref "C32") (pin "2") (pinfunction "2_2") (pintype "passive"))
      (node (ref "U6") (pin "9") (pinfunction "VCP_9") (pintype "passive"))
    )
    (net (code "194") (name "Net-(U6-VREG)") (class "Default")
      (node (ref "C36") (pin "2") (pinfunction "2_2") (pintype "passive"))
      (node (ref "U6") (pin "10") (pinfunction "VREG_10") (pintype "passive"))
    )
    (net (code "195") (name "Net-(U7-CP1)") (class "Default")
      (node (ref "C38") (pin "1") (pinfunction "1_1") (pintype "passive"))
      (node (ref "U7") (pin "7") (pinfunction "CP1_7") (pintype "passive"))
    )
    (net (code "196") (name "Net-(U7-CP2)") (class "Default")
      (node (ref "C38") (pin "2") (pinfunction "2_2") (pintype "passive"))
      (node (ref "U7") (pin "8") (pinfunction "CP2_8") (pintype "passive"))
    )
    (net (code "197") (name "Net-(U7-OUT1A)") (class "Default")
      (node (ref "CF11") (pin "1") (pinfunction "1_1") (pintype "passive"))
      (node (ref "D28") (pin "K") (pinfunction "K_K") (pintype "passive"))
      (node (ref "U7") (pin "27") (pinfunction "OUT1A_27") (pintype "output"))
    )
    (net (code "198") (name "Net-(U7-OUT1B)") (class "Default")
      (node (ref "CF12") (pin "1") (pinfunction "1_1") (pintype "passive"))
      (node (ref "D29") (pin "K") (pinfunction "K_K") (pintype "passive"))
      (node (ref "U7") (pin "24") (pinfunction "OUT1B_24") (pintype "output"))
    )
    (net (code "199") (name "Net-(U7-OUT2A)") (class "Default")
      (node (ref "CF10") (pin "1") (pinfunction "1_1") (pintype "passive"))
      (node (ref "D30") (pin "K") (pinfunction "K_K") (pintype "passive"))
      (node (ref "U7") (pin "30") (pinfunction "OUT2A_30") (pintype "output"))
    )
    (net (code "200") (name "Net-(U7-OUT2B)") (class "Default")
      (node (ref "CF9") (pin "1") (pinfunction "1_1") (pintype "passive"))
      (node (ref "D31") (pin "K") (pinfunction "K_K") (pintype "passive"))
      (node (ref "U7") (pin "1") (pinfunction "OUT2B_1") (pintype "output"))
    )
    (net (code "201") (name "Net-(U7-RESET)") (class "Default")
      (node (ref "C18") (pin "1") (pinfunction "1_1") (pintype "passive"))
      (node (ref "R66") (pin "1") (pinfunction "1_1") (pintype "passive"))
      (node (ref "U7") (pin "13") (pinfunction "RESET_13") (pintype "passive"))
      (node (ref "U7") (pin "15") (pinfunction "SLEEP_15") (pintype "passive"))
      (node (ref "U7") (pin "16") (pinfunction "VDD_16") (pintype "power_in"))
    )
    (net (code "202") (name "Net-(U7-ROSC)") (class "Default")
      (node (ref "R17") (pin "2") (pinfunction "2_2") (pintype "passive"))
      (node (ref "U7") (pin "14") (pinfunction "ROSC_14") (pintype "passive"))
    )
    (net (code "203") (name "Net-(U7-SENSE1)") (class "Default")
      (node (ref "R15") (pin "1") (pinfunction "1_1") (pintype "passive"))
      (node (ref "U7") (pin "25") (pinfunction "SENSE1_25") (pintype "passive"))
    )
    (net (code "204") (name "Net-(U7-SENSE2)") (class "Default")
      (node (ref "R14") (pin "1") (pinfunction "1_1") (pintype "passive"))
      (node (ref "U7") (pin "32") (pinfunction "SENSE2_32") (pintype "passive"))
    )
    (net (code "205") (name "Net-(U7-VCP)") (class "Default")
      (node (ref "C37") (pin "2") (pinfunction "2_2") (pintype "passive"))
      (node (ref "U7") (pin "9") (pinfunction "VCP_9") (pintype "passive"))
    )
    (net (code "206") (name "Net-(U7-VREG)") (class "Default")
      (node (ref "C41") (pin "2") (pinfunction "2_2") (pintype "passive"))
      (node (ref "U7") (pin "10") (pinfunction "VREG_10") (pintype "passive"))
    )
    (net (code "207") (name "Net-(U8-CP1)") (class "Default")
      (node (ref "C43") (pin "1") (pinfunction "1_1") (pintype "passive"))
      (node (ref "U8") (pin "7") (pinfunction "CP1_7") (pintype "passive"))
    )
    (net (code "208") (name "Net-(U8-CP2)") (class "Default")
      (node (ref "C43") (pin "2") (pinfunction "2_2") (pintype "passive"))
      (node (ref "U8") (pin "8") (pinfunction "CP2_8") (pintype "passive"))
    )
    (net (code "209") (name "Net-(U8-OUT1A)") (class "Default")
      (node (ref "CF15") (pin "1") (pinfunction "1_1") (pintype "passive"))
      (node (ref "D32") (pin "K") (pinfunction "K_K") (pintype "passive"))
      (node (ref "U8") (pin "27") (pinfunction "OUT1A_27") (pintype "output"))
    )
    (net (code "210") (name "Net-(U8-OUT1B)") (class "Default")
      (node (ref "CF16") (pin "1") (pinfunction "1_1") (pintype "passive"))
      (node (ref "D33") (pin "K") (pinfunction "K_K") (pintype "passive"))
      (node (ref "U8") (pin "24") (pinfunction "OUT1B_24") (pintype "output"))
    )
    (net (code "211") (name "Net-(U8-OUT2A)") (class "Default")
      (node (ref "CF14") (pin "1") (pinfunction "1_1") (pintype "passive"))
      (node (ref "D35") (pin "K") (pinfunction "K_K") (pintype "passive"))
      (node (ref "U8") (pin "30") (pinfunction "OUT2A_30") (pintype "output"))
    )
    (net (code "212") (name "Net-(U8-OUT2B)") (class "Default")
      (node (ref "CF13") (pin "1") (pinfunction "1_1") (pintype "passive"))
      (node (ref "D34") (pin "K") (pinfunction "K_K") (pintype "passive"))
      (node (ref "U8") (pin "1") (pinfunction "OUT2B_1") (pintype "output"))
    )
    (net (code "213") (name "Net-(U8-RESET)") (class "Default")
      (node (ref "C17") (pin "1") (pinfunction "1_1") (pintype "passive"))
      (node (ref "R67") (pin "1") (pinfunction "1_1") (pintype "passive"))
      (node (ref "U8") (pin "13") (pinfunction "RESET_13") (pintype "passive"))
      (node (ref "U8") (pin "15") (pinfunction "SLEEP_15") (pintype "passive"))
      (node (ref "U8") (pin "16") (pinfunction "VDD_16") (pintype "power_in"))
    )
    (net (code "214") (name "Net-(U8-ROSC)") (class "Default")
      (node (ref "R22") (pin "2") (pinfunction "2_2") (pintype "passive"))
      (node (ref "U8") (pin "14") (pinfunction "ROSC_14") (pintype "passive"))
    )
    (net (code "215") (name "Net-(U8-SENSE1)") (class "Default")
      (node (ref "R20") (pin "1") (pinfunction "1_1") (pintype "passive"))
      (node (ref "U8") (pin "25") (pinfunction "SENSE1_25") (pintype "passive"))
    )
    (net (code "216") (name "Net-(U8-SENSE2)") (class "Default")
      (node (ref "R19") (pin "1") (pinfunction "1_1") (pintype "passive"))
      (node (ref "U8") (pin "32") (pinfunction "SENSE2_32") (pintype "passive"))
    )
    (net (code "217") (name "Net-(U8-VCP)") (class "Default")
      (node (ref "C42") (pin "2") (pinfunction "2_2") (pintype "passive"))
      (node (ref "U8") (pin "9") (pinfunction "VCP_9") (pintype "passive"))
    )
    (net (code "218") (name "Net-(U8-VREG)") (class "Default")
      (node (ref "C46") (pin "2") (pinfunction "2_2") (pintype "passive"))
      (node (ref "U8") (pin "10") (pinfunction "VREG_10") (pintype "passive"))
    )
    (net (code "219") (name "Net-(U9-CP1)") (class "Default")
      (node (ref "C48") (pin "1") (pinfunction "1_1") (pintype "passive"))
      (node (ref "U9") (pin "7") (pinfunction "CP1_7") (pintype "passive"))
    )
    (net (code "220") (name "Net-(U9-CP2)") (class "Default")
      (node (ref "C48") (pin "2") (pinfunction "2_2") (pintype "passive"))
      (node (ref "U9") (pin "8") (pinfunction "CP2_8") (pintype "passive"))
    )
    (net (code "221") (name "Net-(U9-OUT1A)") (class "Default")
      (node (ref "CF19") (pin "1") (pinfunction "1_1") (pintype "passive"))
      (node (ref "D38") (pin "K") (pinfunction "K_K") (pintype "passive"))
      (node (ref "U9") (pin "27") (pinfunction "OUT1A_27") (pintype "output"))
    )
    (net (code "222") (name "Net-(U9-OUT1B)") (class "Default")
      (node (ref "CF20") (pin "1") (pinfunction "1_1") (pintype "passive"))
      (node (ref "D39") (pin "K") (pinfunction "K_K") (pintype "passive"))
      (node (ref "U9") (pin "24") (pinfunction "OUT1B_24") (pintype "output"))
    )
    (net (code "223") (name "Net-(U9-OUT2A)") (class "Default")
      (node (ref "CF18") (pin "1") (pinfunction "1_1") (pintype "passive"))
      (node (ref "D37") (pin "K") (pinfunction "K_K") (pintype "passive"))
      (node (ref "U9") (pin "30") (pinfunction "OUT2A_30") (pintype "output"))
    )
    (net (code "224") (name "Net-(U9-OUT2B)") (class "Default")
      (node (ref "CF17") (pin "1") (pinfunction "1_1") (pintype "passive"))
      (node (ref "D36") (pin "K") (pinfunction "K_K") (pintype "passive"))
      (node (ref "U9") (pin "1") (pinfunction "OUT2B_1") (pintype "output"))
    )
    (net (code "225") (name "Net-(U9-RESET)") (class "Default")
      (node (ref "C4") (pin "1") (pinfunction "1_1") (pintype "passive"))
      (node (ref "R68") (pin "1") (pinfunction "1_1") (pintype "passive"))
      (node (ref "U9") (pin "13") (pinfunction "RESET_13") (pintype "passive"))
      (node (ref "U9") (pin "15") (pinfunction "SLEEP_15") (pintype "passive"))
      (node (ref "U9") (pin "16") (pinfunction "VDD_16") (pintype "power_in"))
    )
    (net (code "226") (name "Net-(U9-ROSC)") (class "Default")
      (node (ref "R26") (pin "2") (pinfunction "2_2") (pintype "passive"))
      (node (ref "U9") (pin "14") (pinfunction "ROSC_14") (pintype "passive"))
    )
    (net (code "227") (name "Net-(U9-SENSE1)") (class "Default")
      (node (ref "R24") (pin "1") (pinfunction "1_1") (pintype "passive"))
      (node (ref "U9") (pin "25") (pinfunction "SENSE1_25") (pintype "passive"))
    )
    (net (code "228") (name "Net-(U9-SENSE2)") (class "Default")
      (node (ref "R23") (pin "1") (pinfunction "1_1") (pintype "passive"))
      (node (ref "U9") (pin "32") (pinfunction "SENSE2_32") (pintype "passive"))
    )
    (net (code "229") (name "Net-(U9-VCP)") (class "Default")
      (node (ref "C47") (pin "2") (pinfunction "2_2") (pintype "passive"))
      (node (ref "U9") (pin "9") (pinfunction "VCP_9") (pintype "passive"))
    )
    (net (code "230") (name "Net-(U9-VREG)") (class "Default")
      (node (ref "C51") (pin "2") (pinfunction "2_2") (pintype "passive"))
      (node (ref "U9") (pin "10") (pinfunction "VREG_10") (pintype "passive"))
    )
    (net (code "231") (name "Net-(U10-VOC)") (class "Default")
      (node (ref "R34") (pin "1") (pinfunction "1_1") (pintype "passive"))
      (node (ref "U10") (pin "12") (pinfunction "VOC_12") (pintype "passive"))
    )
    (net (code "232") (name "Net-(X3A-S)") (class "Default")
      (node (ref "R78") (pin "1") (pinfunction "1_1") (pintype "passive"))
      (node (ref "R79") (pin "1") (pinfunction "1_1") (pintype "passive"))
      (node (ref "TP23") (pin "TP") (pinfunction "TP_TP") (pintype "passive"))
      (node (ref "X3") (pin "2") (pinfunction "S_2") (pintype "passive"))
    )
    (net (code "233") (name "Net-(X4B-1)") (class "Default")
      (node (ref "CF6") (pin "3") (pinfunction "3_3") (pintype "passive"))
      (node (ref "X4") (pin "2") (pinfunction "1_2") (pintype "passive"))
    )
    (net (code "234") (name "Net-(X4C-1)") (class "Default")
      (node (ref "CF7") (pin "3") (pinfunction "3_3") (pintype "passive"))
      (node (ref "X4") (pin "3") (pinfunction "1_3") (pintype "passive"))
    )
    (net (code "235") (name "Net-(X4D-1)") (class "Default")
      (node (ref "CF8") (pin "3") (pinfunction "3_3") (pintype "passive"))
      (node (ref "X4") (pin "4") (pinfunction "1_4") (pintype "passive"))
    )
    (net (code "236") (name "Net-(X6B-1)") (class "Default")
      (node (ref "CF14") (pin "3") (pinfunction "3_3") (pintype "passive"))
      (node (ref "X6") (pin "2") (pinfunction "1_2") (pintype "passive"))
    )
    (net (code "237") (name "Net-(X6C-1)") (class "Default")
      (node (ref "CF15") (pin "3") (pinfunction "3_3") (pintype "passive"))
      (node (ref "X6") (pin "3") (pinfunction "1_3") (pintype "passive"))
    )
    (net (code "238") (name "Net-(X6D-1)") (class "Default")
      (node (ref "CF16") (pin "3") (pinfunction "3_3") (pintype "passive"))
      (node (ref "X6") (pin "4") (pinfunction "1_4") (pintype "passive"))
    )
    (net (code "239") (name "Net-(X7B-1)") (class "Default")
      (node (ref "CF18") (pin "3") (pinfunction "3_3") (pintype "passive"))
      (node (ref "X7") (pin "2") (pinfunction "1_2") (pintype "passive"))
    )
    (net (code "240") (name "Net-(X7C-1)") (class "Default")
      (node (ref "CF19") (pin "3") (pinfunction "3_3") (pintype "passive"))
      (node (ref "X7") (pin "3") (pinfunction "1_3") (pintype "passive"))
    )
    (net (code "241") (name "Net-(X7D-1)") (class "Default")
      (node (ref "CF20") (pin "3") (pinfunction "3_3") (pintype "passive"))
      (node (ref "X7") (pin "4") (pinfunction "1_4") (pintype "passive"))
    )
    (net (code "242") (name "Net-(X8B-1)") (class "Default")
      (node (ref "CF2") (pin "3") (pinfunction "3_3") (pintype "passive"))
      (node (ref "X8") (pin "2") (pinfunction "1_2") (pintype "passive"))
    )
    (net (code "243") (name "Net-(X8C-1)") (class "Default")
      (node (ref "CF3") (pin "3") (pinfunction "3_3") (pintype "passive"))
      (node (ref "X8") (pin "3") (pinfunction "1_3") (pintype "passive"))
    )
    (net (code "244") (name "Net-(X8D-1)") (class "Default")
      (node (ref "CF4") (pin "3") (pinfunction "3_3") (pintype "passive"))
      (node (ref "X8") (pin "4") (pinfunction "1_4") (pintype "passive"))
    )
    (net (code "245") (name "Net-(X14B-1)") (class "Default")
      (node (ref "CF10") (pin "3") (pinfunction "3_3") (pintype "passive"))
      (node (ref "X14") (pin "2") (pinfunction "1_2") (pintype "passive"))
      (node (ref "X15") (pin "2") (pinfunction "1_2") (pintype "passive"))
    )
    (net (code "246") (name "Net-(X14C-1)") (class "Default")
      (node (ref "CF11") (pin "3") (pinfunction "3_3") (pintype "passive"))
      (node (ref "X14") (pin "3") (pinfunction "1_3") (pintype "passive"))
      (node (ref "X15") (pin "3") (pinfunction "1_3") (pintype "passive"))
    )
    (net (code "247") (name "Net-(X14D-1)") (class "Default")
      (node (ref "CF12") (pin "3") (pinfunction "3_3") (pintype "passive"))
      (node (ref "X14") (pin "4") (pinfunction "1_4") (pintype "passive"))
      (node (ref "X15") (pin "4") (pinfunction "1_4") (pintype "passive"))
    )
    (net (code "248") (name "Net-(X27A-S)") (class "Default")
      (node (ref "R28") (pin "1") (pinfunction "1_1") (pintype "passive"))
      (node (ref "R31") (pin "1") (pinfunction "1_1") (pintype "passive"))
      (node (ref "TP20") (pin "TP") (pinfunction "TP_TP") (pintype "passive"))
      (node (ref "X27") (pin "2") (pinfunction "S_2") (pintype "passive"))
    )
    (net (code "249") (name "Net-(X28A-S)") (class "Default")
      (node (ref "R36") (pin "1") (pinfunction "1_1") (pintype "passive"))
      (node (ref "R37") (pin "1") (pinfunction "1_1") (pintype "passive"))
      (node (ref "TP21") (pin "TP") (pinfunction "TP_TP") (pintype "passive"))
      (node (ref "X28") (pin "2") (pinfunction "S_2") (pintype "passive"))
    )
    (net (code "250") (name "Net-(X29A-S)") (class "Default")
      (node (ref "R39") (pin "1") (pinfunction "1_1") (pintype "passive"))
      (node (ref "R73") (pin "1") (pinfunction "1_1") (pintype "passive"))
      (node (ref "TP22") (pin "TP") (pinfunction "TP_TP") (pintype "passive"))
      (node (ref "X29") (pin "2") (pinfunction "S_2") (pintype "passive"))
    )
    (net (code "251") (name "VBED") (class "Default")
      (node (ref "D10") (pin "C") (pinfunction "C_C") (pintype "passive"))
      (node (ref "R58") (pin "2") (pinfunction "2_2") (pintype "passive"))
      (node (ref "X11") (pin "10") (pinfunction "1_10") (pintype "passive"))
      (node (ref "X38") (pin "2") (pinfunction "2_2") (pintype "passive"))
    )
    (net (code "252") (name "VCC") (class "Default")
      (node (ref "C20") (pin "1") (pinfunction "1_1") (pintype "passive"))
      (node (ref "C21") (pin "2") (pinfunction "2_2") (pintype "passive"))
      (node (ref "C25") (pin "2") (pinfunction "2_2") (pintype "passive"))
      (node (ref "C30") (pin "2") (pinfunction "2_2") (pintype "passive"))
      (node (ref "C52") (pin "1") (pinfunction "1_1") (pintype "passive"))
      (node (ref "C53") (pin "1") (pinfunction "1_1") (pintype "passive"))
      (node (ref "C55") (pin "1") (pinfunction "1_1") (pintype "passive"))
      (node (ref "C7") (pin "1") (pinfunction "1_1") (pintype "passive"))
      (node (ref "C8") (pin "1") (pinfunction "1_1") (pintype "passive"))
      (node (ref "C9") (pin "1") (pinfunction "1_1") (pintype "passive"))
      (node (ref "C96") (pin "2") (pinfunction "2_2") (pintype "passive"))
      (node (ref "D11") (pin "K") (pinfunction "K_K") (pintype "passive"))
      (node (ref "D13") (pin "K") (pinfunction "K_K") (pintype "passive"))
      (node (ref "D15") (pin "K") (pinfunction "K_K") (pintype "passive"))
      (node (ref "D17") (pin "K") (pinfunction "K_K") (pintype "passive"))
      (node (ref "D5") (pin "C") (pinfunction "C_C") (pintype "passive"))
      (node (ref "L2") (pin "1") (pinfunction "1_1") (pintype "passive"))
      (node (ref "L3") (pin "2") (pinfunction "2_2") (pintype "passive"))
      (node (ref "R11") (pin "1") (pinfunction "1_1") (pintype "passive"))
      (node (ref "R13") (pin "1") (pinfunction "1_1") (pintype "passive"))
      (node (ref "R13") (pin "2") (pinfunction "2_2") (pintype "passive"))
      (node (ref "R29") (pin "2") (pinfunction "2_2") (pintype "passive"))
      (node (ref "R30") (pin "1") (pinfunction "1_1") (pintype "passive"))
      (node (ref "R31") (pin "2") (pinfunction "2_2") (pintype "passive"))
      (node (ref "R35") (pin "1") (pinfunction "1_1") (pintype "passive"))
      (node (ref "R37") (pin "2") (pinfunction "2_2") (pintype "passive"))
      (node (ref "R46") (pin "2") (pinfunction "2_2") (pintype "passive"))
      (node (ref "R59") (pin "1") (pinfunction "1_1") (pintype "passive"))
      (node (ref "R60") (pin "1") (pinfunction "1_1") (pintype "passive"))
      (node (ref "R61") (pin "1") (pinfunction "1_1") (pintype "passive"))
      (node (ref "R62") (pin "1") (pinfunction "1_1") (pintype "passive"))
      (node (ref "R63") (pin "1") (pinfunction "1_1") (pintype "passive"))
      (node (ref "R65") (pin "2") (pinfunction "2_2") (pintype "passive"))
      (node (ref "R66") (pin "2") (pinfunction "2_2") (pintype "passive"))
      (node (ref "R67") (pin "2") (pinfunction "2_2") (pintype "passive"))
      (node (ref "R68") (pin "2") (pinfunction "2_2") (pintype "passive"))
      (node (ref "R73") (pin "2") (pinfunction "2_2") (pintype "passive"))
      (node (ref "R79") (pin "2") (pinfunction "2_2") (pintype "passive"))
      (node (ref "U10") (pin "10") (pinfunction "VDD2B_10") (pintype "passive"))
      (node (ref "U10") (pin "16") (pinfunction "VDD2A_16") (pintype "passive"))
      (node (ref "U2") (pin "10") (pinfunction "VCC_10") (pintype "power_in"))
      (node (ref "U2") (pin "31") (pinfunction "VCC1_31") (pintype "power_in"))
      (node (ref "U2") (pin "61") (pinfunction "VCC2_61") (pintype "power_in"))
      (node (ref "U2") (pin "80") (pinfunction "VCC3_80") (pintype "power_in"))
      (node (ref "U3") (pin "4") (pinfunction "FEEDBACK_4") (pintype "passive"))
      (node (ref "U4") (pin "P06") (pinfunction "VDD_P06") (pintype "passive"))
      (node (ref "X40") (pin "1") (pinfunction "1_1") (pintype "passive"))
    )
    (net (code "253") (name "VHEAT") (class "Default")
      (node (ref "C40") (pin "1") (pinfunction "1_1") (pintype "passive"))
      (node (ref "C45") (pin "2") (pinfunction "2_2") (pintype "passive"))
      (node (ref "D1") (pin "C") (pinfunction "C_C") (pintype "passive"))
      (node (ref "D3") (pin "C") (pinfunction "C_C") (pintype "passive"))
      (node (ref "D6") (pin "C") (pinfunction "C_C") (pintype "passive"))
      (node (ref "R3") (pin "2") (pinfunction "2_2") (pintype "passive"))
      (node (ref "R40") (pin "2") (pinfunction "2_2") (pintype "passive"))
      (node (ref "R41") (pin "2") (pinfunction "2_2") (pintype "passive"))
      (node (ref "R50") (pin "2") (pinfunction "2_2") (pintype "passive"))
      (node (ref "R55") (pin "2") (pinfunction "2_2") (pintype "passive"))
      (node (ref "R69") (pin "2") (pinfunction "2_2") (pintype "passive"))
      (node (ref "U3") (pin "7") (pinfunction "VIN_7") (pintype "power_in"))
      (node (ref "X11") (pin "2") (pinfunction "1_2") (pintype "passive"))
      (node (ref "X11") (pin "4") (pinfunction "1_4") (pintype "passive"))
      (node (ref "X11") (pin "6") (pinfunction "1_6") (pintype "passive"))
      (node (ref "X11") (pin "8") (pinfunction "1_8") (pintype "passive"))
      (node (ref "X35") (pin "2") (pinfunction "2_2") (pintype "passive"))
      (node (ref "X36") (pin "2") (pinfunction "2_2") (pintype "passive"))
      (node (ref "X37") (pin "2") (pinfunction "2_2") (pintype "passive"))
      (node (ref "X9") (pin "2") (pinfunction "S_2") (pintype "passive"))
    )
    (net (code "254") (name "VMOT") (class "Default")
      (node (ref "C27") (pin "1") (pinfunction "1_1") (pintype "passive"))
      (node (ref "C29") (pin "1") (pinfunction "1_1") (pintype "passive"))
      (node (ref "C32") (pin "1") (pinfunction "1_1") (pintype "passive"))
      (node (ref "C34") (pin "1") (pinfunction "1_1") (pintype "passive"))
      (node (ref "C37") (pin "1") (pinfunction "1_1") (pintype "passive"))
      (node (ref "C39") (pin "1") (pinfunction "1_1") (pintype "passive"))
      (node (ref "C42") (pin "1") (pinfunction "1_1") (pintype "passive"))
      (node (ref "C44") (pin "1") (pinfunction "1_1") (pintype "passive"))
      (node (ref "C47") (pin "1") (pinfunction "1_1") (pintype "passive"))
      (node (ref "C49") (pin "1") (pinfunction "1_1") (pintype "passive"))
      (node (ref "C71") (pin "1") (pinfunction "1_1") (pintype "passive"))
      (node (ref "C72") (pin "1") (pinfunction "1_1") (pintype "passive"))
      (node (ref "C73") (pin "1") (pinfunction "1_1") (pintype "passive"))
      (node (ref "C74") (pin "1") (pinfunction "1_1") (pintype "passive"))
      (node (ref "C75") (pin "1") (pinfunction "1_1") (pintype "passive"))
      (node (ref "C76") (pin "+") (pinfunction "+_+") (pintype "passive"))
      (node (ref "U5") (pin "22") (pinfunction "VBB_22") (pintype "power_in"))
      (node (ref "U5") (pin "3") (pinfunction "VBB1_3") (pintype "power_in"))
      (node (ref "U6") (pin "22") (pinfunction "VBB_22") (pintype "power_in"))
      (node (ref "U6") (pin "3") (pinfunction "VBB1_3") (pintype "power_in"))
      (node (ref "U7") (pin "22") (pinfunction "VBB_22") (pintype "power_in"))
      (node (ref "U7") (pin "3") (pinfunction "VBB1_3") (pintype "power_in"))
      (node (ref "U8") (pin "22") (pinfunction "VBB_22") (pintype "power_in"))
      (node (ref "U8") (pin "3") (pinfunction "VBB1_3") (pintype "power_in"))
      (node (ref "U9") (pin "22") (pinfunction "VBB_22") (pintype "power_in"))
      (node (ref "U9") (pin "3") (pinfunction "VBB1_3") (pintype "power_in"))
    )
    (net (code "255") (name "unconnected-(RN5-Pad1)") (class "Default")
      (node (ref "RN5") (pin "1") (pinfunction "1_1") (pintype "passive"))
    )
    (net (code "256") (name "unconnected-(U1-(PCINT10)PC4-Pad26)") (class "Default")
      (node (ref "U1") (pin "26") (pinfunction "(PCINT10)PC4_26") (pintype "passive+no_connect"))
    )
    (net (code "257") (name "unconnected-(U3-NC-Pad2)") (class "Default")
      (node (ref "U3") (pin "2") (pinfunction "NC_2") (pintype "passive"))
    )
    (net (code "258") (name "unconnected-(U3-NC1-Pad3)") (class "Default")
      (node (ref "U3") (pin "3") (pinfunction "NC1_3") (pintype "passive"))
    )
    (net (code "259") (name "unconnected-(U4-W3-PadP14)") (class "Default")
      (node (ref "U4") (pin "P14") (pinfunction "W3_P14") (pintype "passive"))
    )
    (net (code "260") (name "unconnected-(U5-NC1-Pad2)") (class "Default")
      (node (ref "U5") (pin "2") (pinfunction "NC1_2") (pintype "output"))
    )
    (net (code "261") (name "unconnected-(U5-NC2-Pad4)") (class "Default")
      (node (ref "U5") (pin "4") (pinfunction "NC2_4") (pintype "output"))
    )
    (net (code "262") (name "unconnected-(U5-NC3-Pad21)") (class "Default")
      (node (ref "U5") (pin "21") (pinfunction "NC3_21") (pintype "output"))
    )
    (net (code "263") (name "unconnected-(U5-NC4-Pad23)") (class "Default")
      (node (ref "U5") (pin "23") (pinfunction "NC4_23") (pintype "output"))
    )
    (net (code "264") (name "unconnected-(U5-NC5-Pad26)") (class "Default")
      (node (ref "U5") (pin "26") (pinfunction "NC5_26") (pintype "output"))
    )
    (net (code "265") (name "unconnected-(U5-NC6-Pad28)") (class "Default")
      (node (ref "U5") (pin "28") (pinfunction "NC6_28") (pintype "output"))
    )
    (net (code "266") (name "unconnected-(U5-NC7-Pad29)") (class "Default")
      (node (ref "U5") (pin "29") (pinfunction "NC7_29") (pintype "output"))
    )
    (net (code "267") (name "unconnected-(U5-NC8-Pad31)") (class "Default")
      (node (ref "U5") (pin "31") (pinfunction "NC8_31") (pintype "output"))
    )
    (net (code "268") (name "unconnected-(U6-NC1-Pad2)") (class "Default")
      (node (ref "U6") (pin "2") (pinfunction "NC1_2") (pintype "output"))
    )
    (net (code "269") (name "unconnected-(U6-NC2-Pad4)") (class "Default")
      (node (ref "U6") (pin "4") (pinfunction "NC2_4") (pintype "output"))
    )
    (net (code "270") (name "unconnected-(U6-NC3-Pad21)") (class "Default")
      (node (ref "U6") (pin "21") (pinfunction "NC3_21") (pintype "output"))
    )
    (net (code "271") (name "unconnected-(U6-NC4-Pad23)") (class "Default")
      (node (ref "U6") (pin "23") (pinfunction "NC4_23") (pintype "output"))
    )
    (net (code "272") (name "unconnected-(U6-NC5-Pad26)") (class "Default")
      (node (ref "U6") (pin "26") (pinfunction "NC5_26") (pintype "output"))
    )
    (net (code "273") (name "unconnected-(U6-NC6-Pad28)") (class "Default")
      (node (ref "U6") (pin "28") (pinfunction "NC6_28") (pintype "output"))
    )
    (net (code "274") (name "unconnected-(U6-NC7-Pad29)") (class "Default")
      (node (ref "U6") (pin "29") (pinfunction "NC7_29") (pintype "output"))
    )
    (net (code "275") (name "unconnected-(U6-NC8-Pad31)") (class "Default")
      (node (ref "U6") (pin "31") (pinfunction "NC8_31") (pintype "output"))
    )
    (net (code "276") (name "unconnected-(U7-NC1-Pad2)") (class "Default")
      (node (ref "U7") (pin "2") (pinfunction "NC1_2") (pintype "output"))
    )
    (net (code "277") (name "unconnected-(U7-NC2-Pad4)") (class "Default")
      (node (ref "U7") (pin "4") (pinfunction "NC2_4") (pintype "output"))
    )
    (net (code "278") (name "unconnected-(U7-NC3-Pad21)") (class "Default")
      (node (ref "U7") (pin "21") (pinfunction "NC3_21") (pintype "output"))
    )
    (net (code "279") (name "unconnected-(U7-NC4-Pad23)") (class "Default")
      (node (ref "U7") (pin "23") (pinfunction "NC4_23") (pintype "output"))
    )
    (net (code "280") (name "unconnected-(U7-NC5-Pad26)") (class "Default")
      (node (ref "U7") (pin "26") (pinfunction "NC5_26") (pintype "output"))
    )
    (net (code "281") (name "unconnected-(U7-NC6-Pad28)") (class "Default")
      (node (ref "U7") (pin "28") (pinfunction "NC6_28") (pintype "output"))
    )
    (net (code "282") (name "unconnected-(U7-NC7-Pad29)") (class "Default")
      (node (ref "U7") (pin "29") (pinfunction "NC7_29") (pintype "output"))
    )
    (net (code "283") (name "unconnected-(U7-NC8-Pad31)") (class "Default")
      (node (ref "U7") (pin "31") (pinfunction "NC8_31") (pintype "output"))
    )
    (net (code "284") (name "unconnected-(U8-NC1-Pad2)") (class "Default")
      (node (ref "U8") (pin "2") (pinfunction "NC1_2") (pintype "output"))
    )
    (net (code "285") (name "unconnected-(U8-NC2-Pad4)") (class "Default")
      (node (ref "U8") (pin "4") (pinfunction "NC2_4") (pintype "output"))
    )
    (net (code "286") (name "unconnected-(U8-NC3-Pad21)") (class "Default")
      (node (ref "U8") (pin "21") (pinfunction "NC3_21") (pintype "output"))
    )
    (net (code "287") (name "unconnected-(U8-NC4-Pad23)") (class "Default")
      (node (ref "U8") (pin "23") (pinfunction "NC4_23") (pintype "output"))
    )
    (net (code "288") (name "unconnected-(U8-NC5-Pad26)") (class "Default")
      (node (ref "U8") (pin "26") (pinfunction "NC5_26") (pintype "output"))
    )
    (net (code "289") (name "unconnected-(U8-NC6-Pad28)") (class "Default")
      (node (ref "U8") (pin "28") (pinfunction "NC6_28") (pintype "output"))
    )
    (net (code "290") (name "unconnected-(U8-NC7-Pad29)") (class "Default")
      (node (ref "U8") (pin "29") (pinfunction "NC7_29") (pintype "output"))
    )
    (net (code "291") (name "unconnected-(U8-NC8-Pad31)") (class "Default")
      (node (ref "U8") (pin "31") (pinfunction "NC8_31") (pintype "output"))
    )
    (net (code "292") (name "unconnected-(U9-NC1-Pad2)") (class "Default")
      (node (ref "U9") (pin "2") (pinfunction "NC1_2") (pintype "output"))
    )
    (net (code "293") (name "unconnected-(U9-NC2-Pad4)") (class "Default")
      (node (ref "U9") (pin "4") (pinfunction "NC2_4") (pintype "output"))
    )
    (net (code "294") (name "unconnected-(U9-NC3-Pad21)") (class "Default")
      (node (ref "U9") (pin "21") (pinfunction "NC3_21") (pintype "output"))
    )
    (net (code "295") (name "unconnected-(U9-NC4-Pad23)") (class "Default")
      (node (ref "U9") (pin "23") (pinfunction "NC4_23") (pintype "output"))
    )
    (net (code "296") (name "unconnected-(U9-NC5-Pad26)") (class "Default")
      (node (ref "U9") (pin "26") (pinfunction "NC5_26") (pintype "output"))
    )
    (net (code "297") (name "unconnected-(U9-NC6-Pad28)") (class "Default")
      (node (ref "U9") (pin "28") (pinfunction "NC6_28") (pintype "output"))
    )
    (net (code "298") (name "unconnected-(U9-NC7-Pad29)") (class "Default")
      (node (ref "U9") (pin "29") (pinfunction "NC7_29") (pintype "output"))
    )
    (net (code "299") (name "unconnected-(U9-NC8-Pad31)") (class "Default")
      (node (ref "U9") (pin "31") (pinfunction "NC8_31") (pintype "output"))
    )
    (net (code "300") (name "unconnected-(U10-VOB-Pad13)") (class "Default")
      (node (ref "U10") (pin "13") (pinfunction "VOB_13") (pintype "passive"))
    )
  )
)
